# PRESELECTOR_REV_B.net
KiCad netlist of a schematic drawn in EAGLE
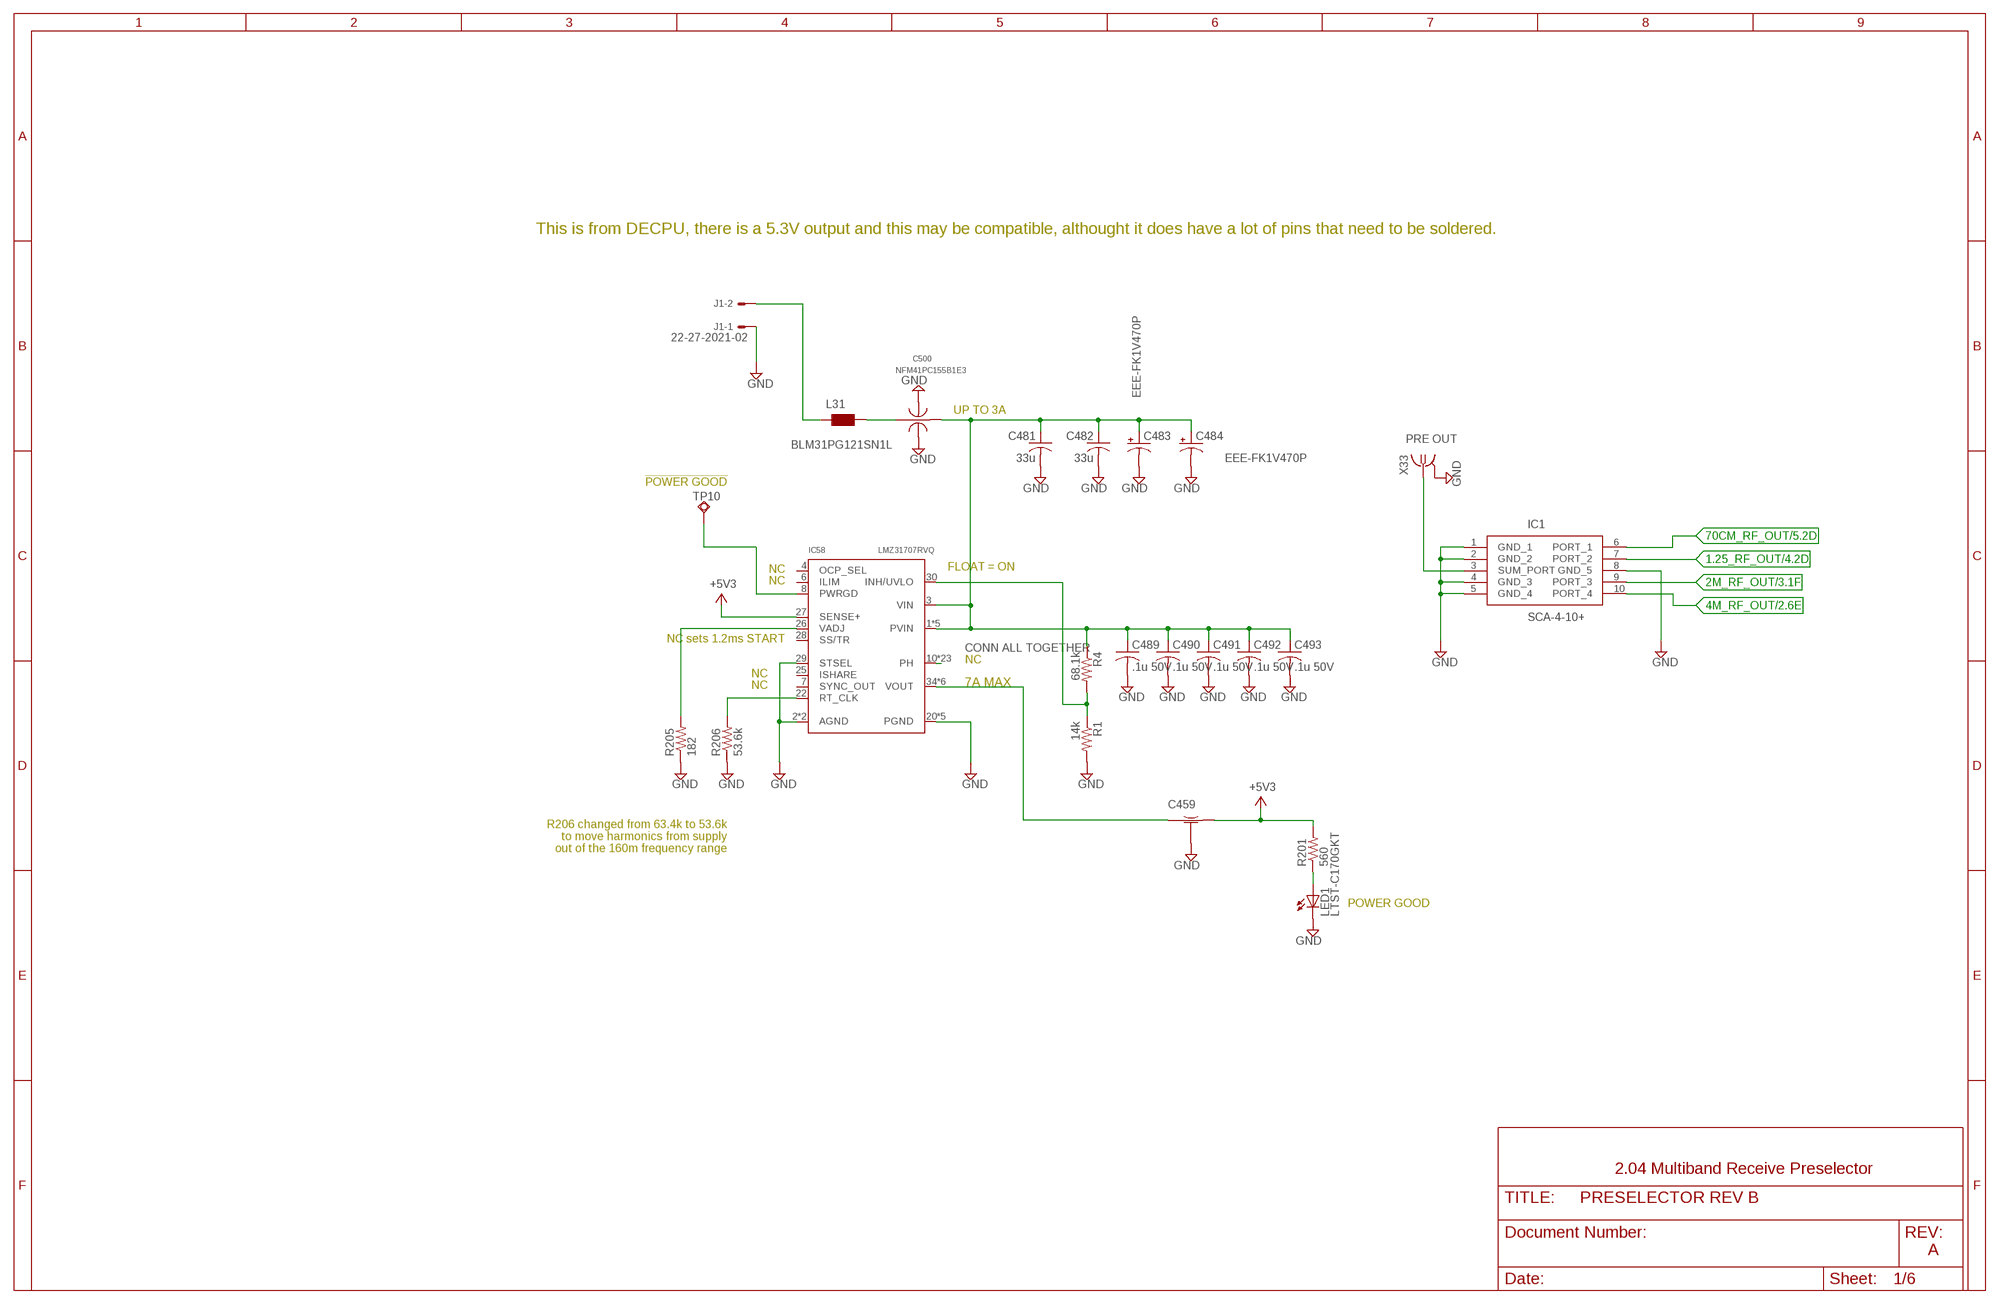
[diagram p0: schematic, sheet 1]
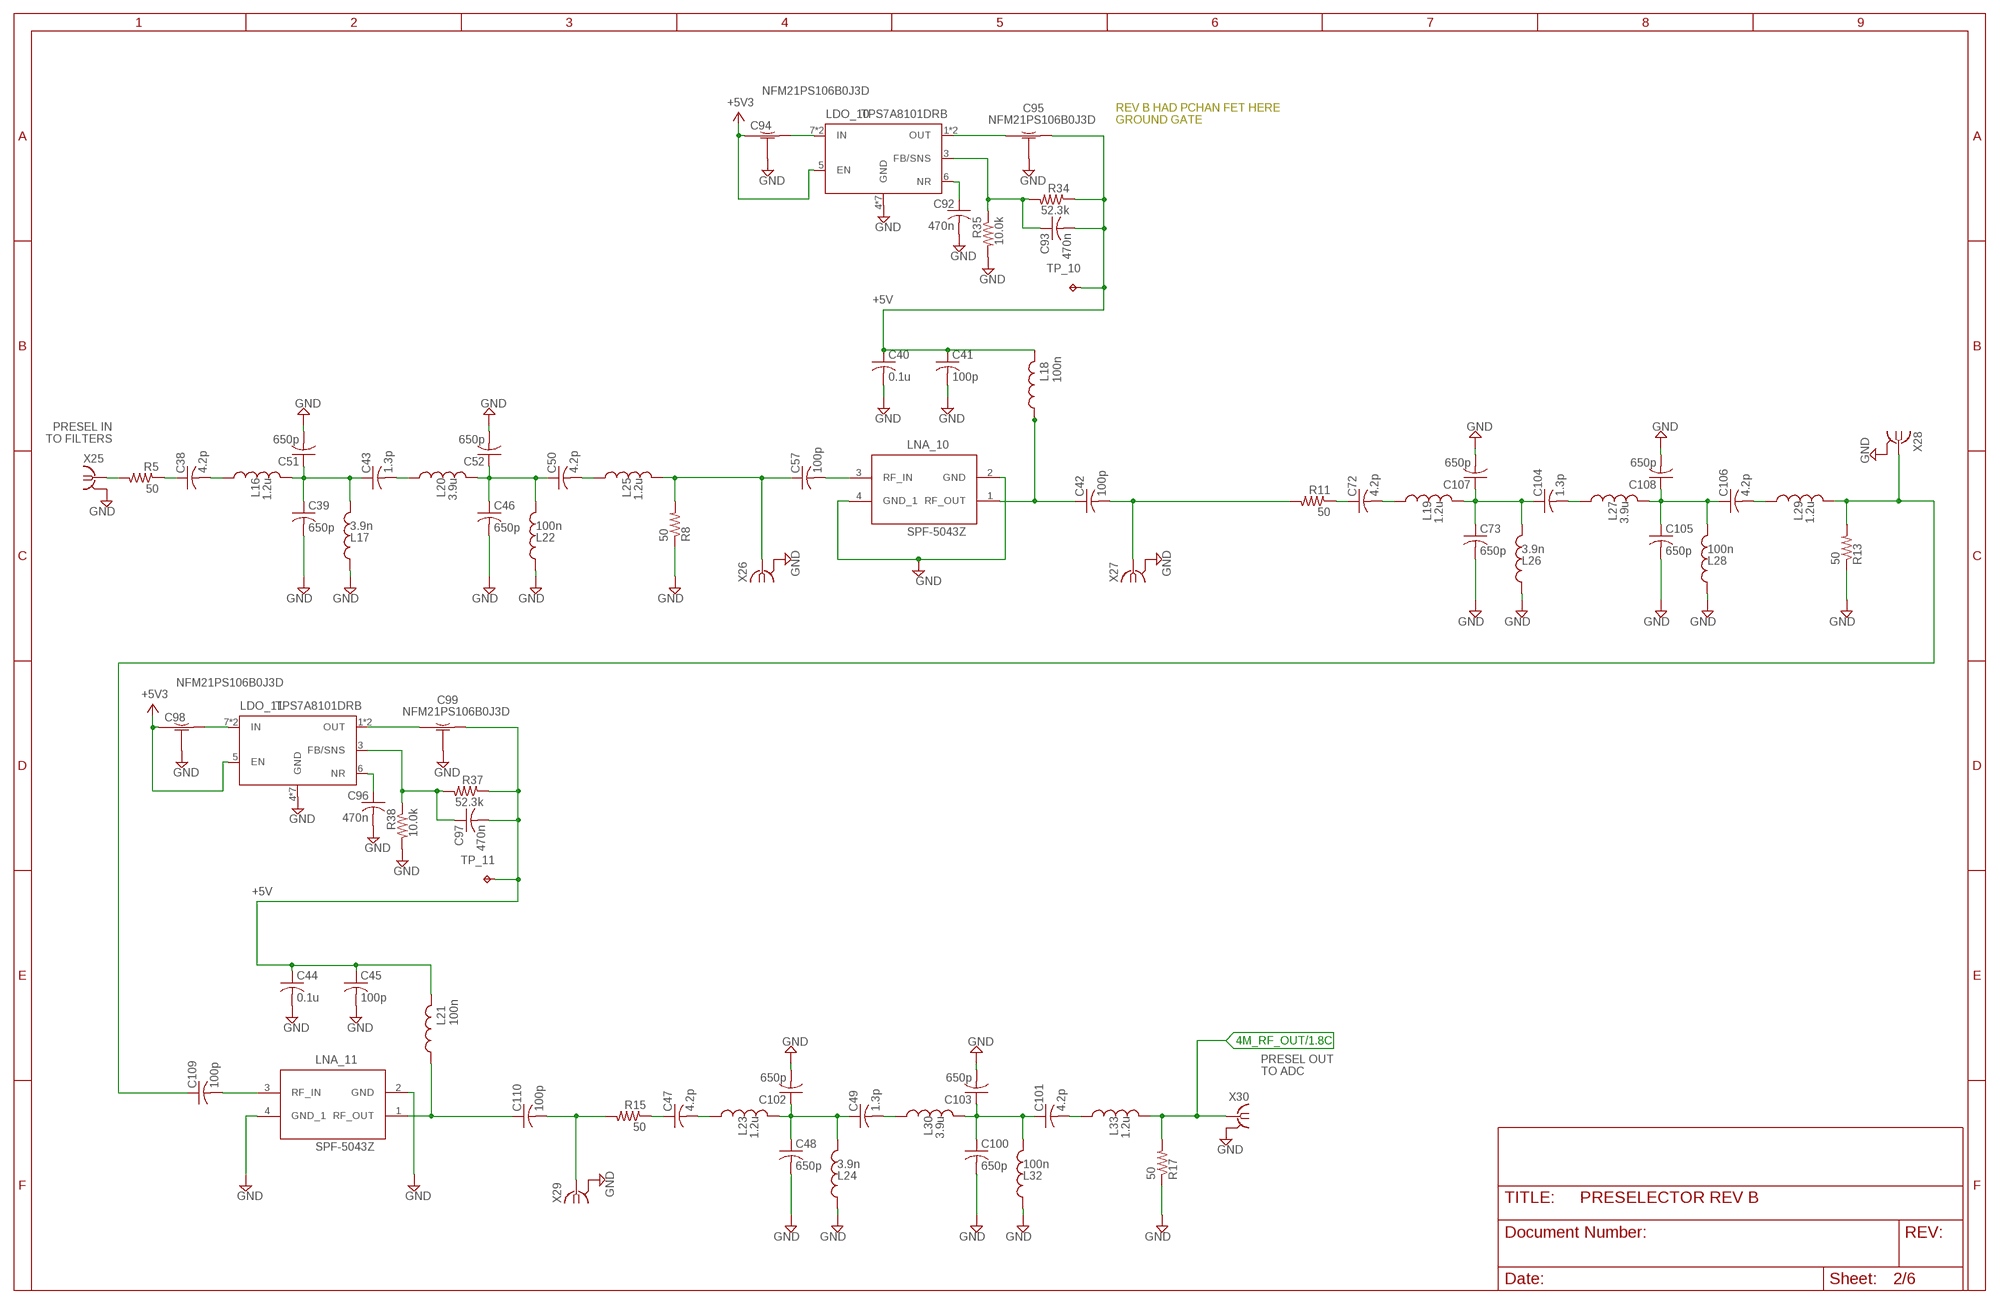
[diagram p1: schematic, sheet 2]
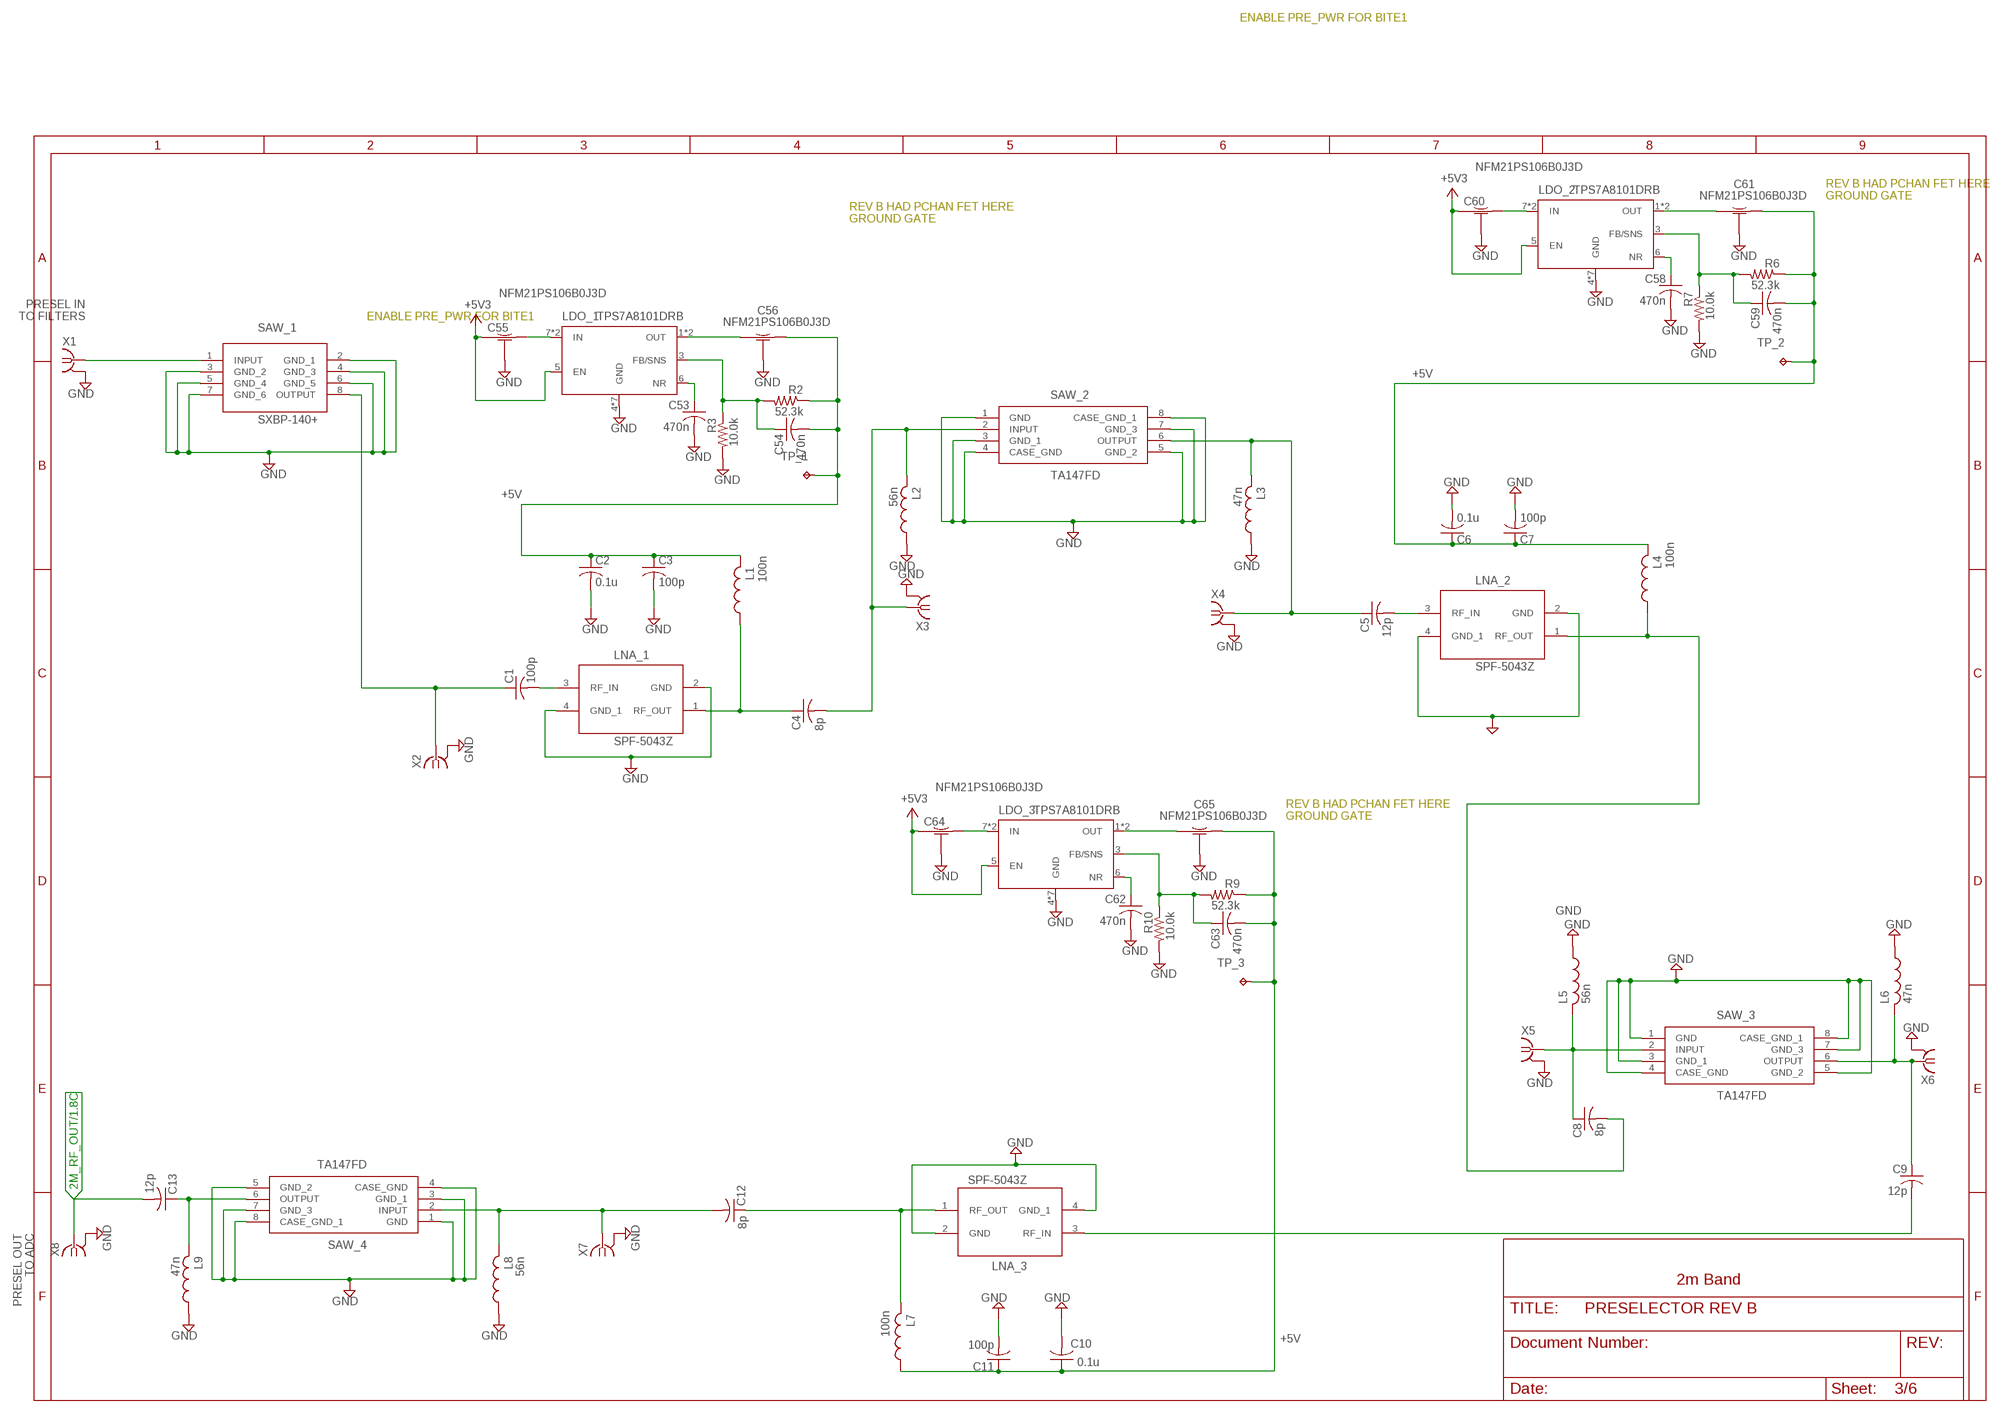
[diagram p2: schematic, sheet 3]
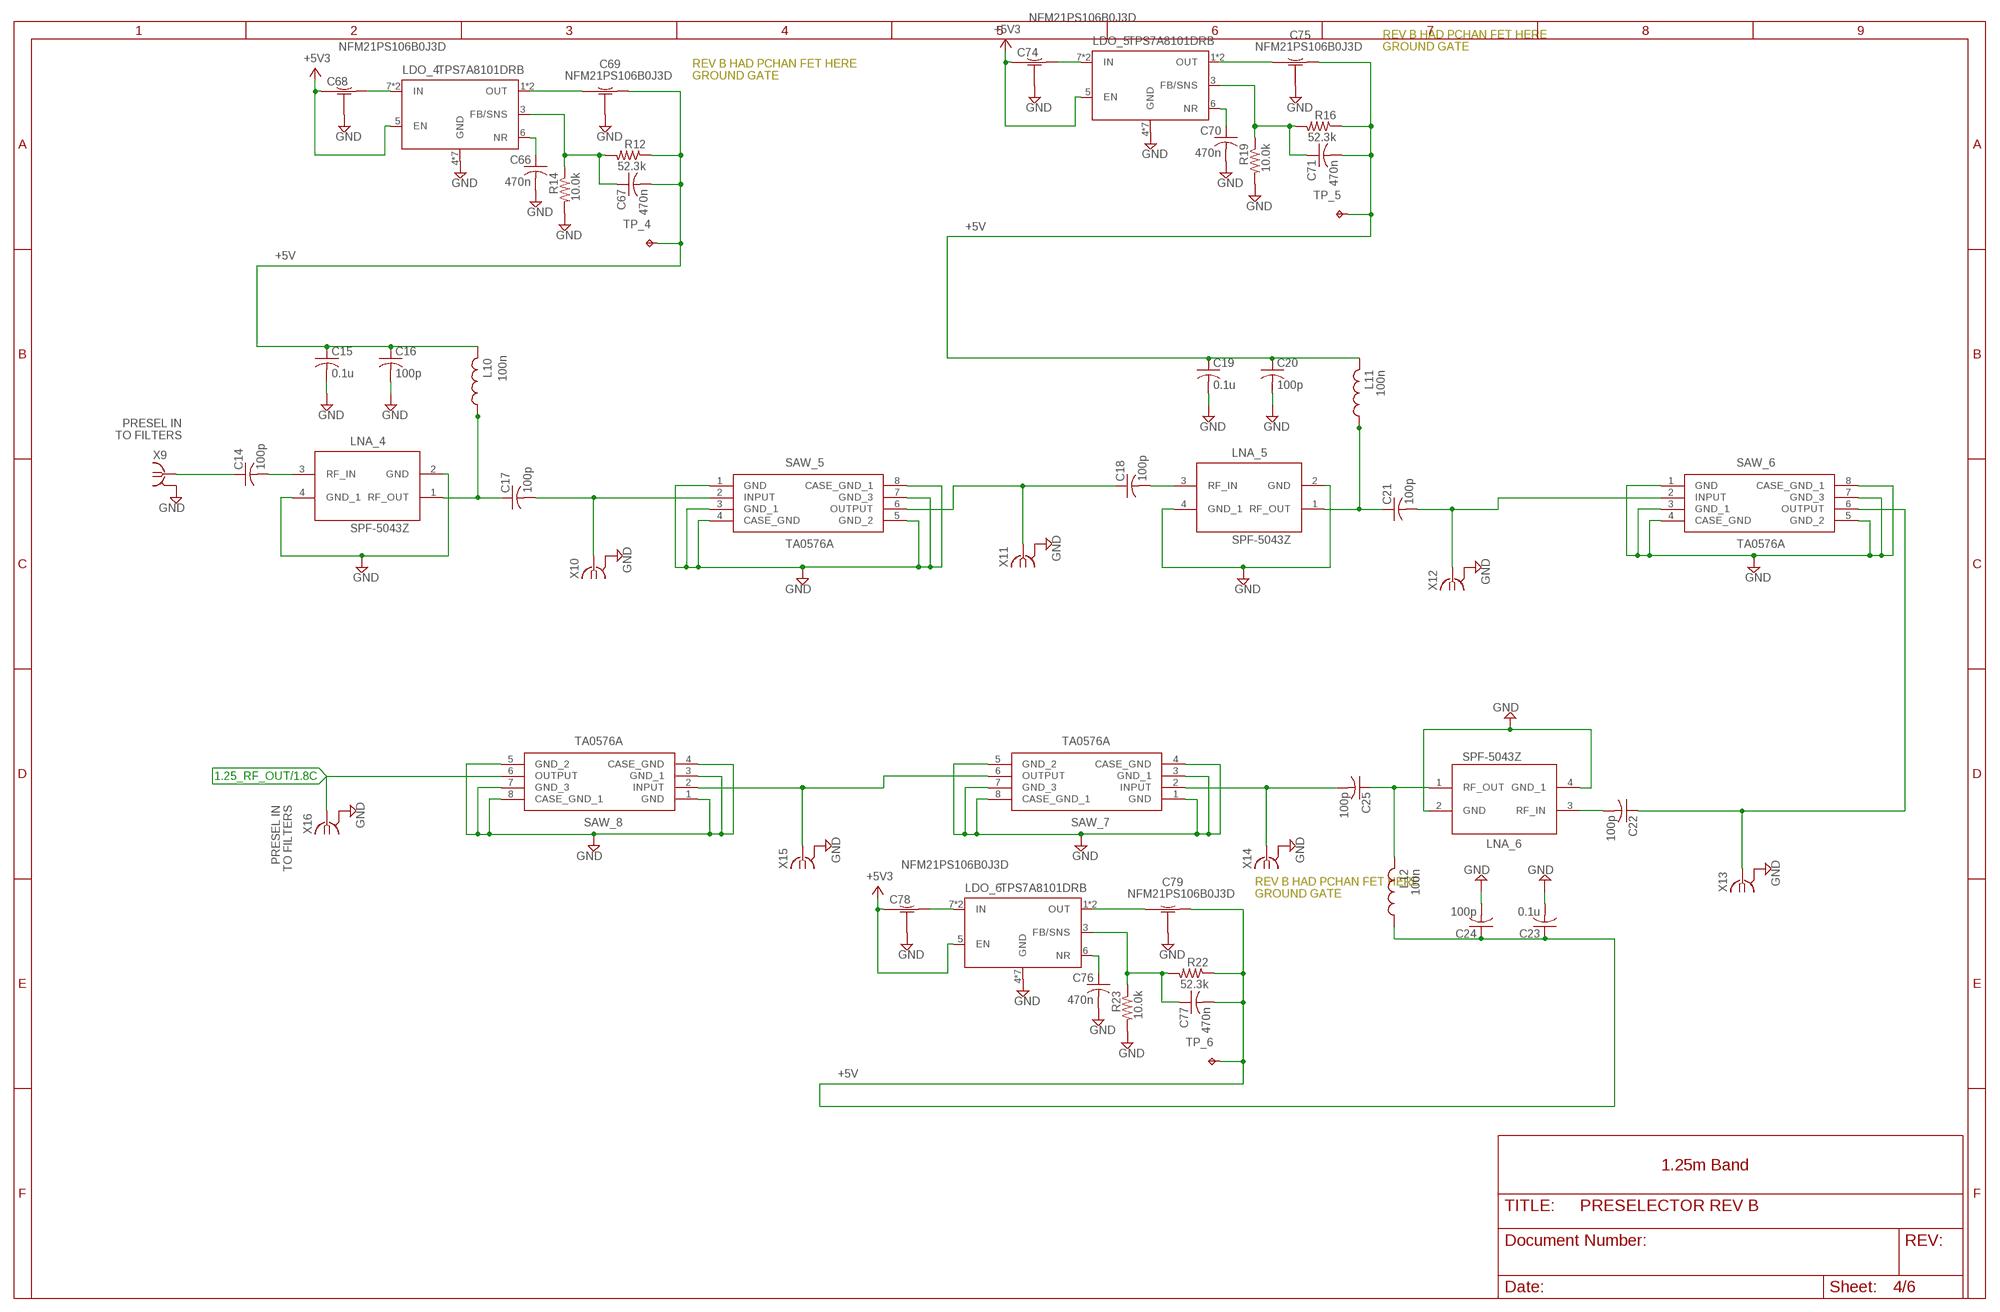
[diagram p3: schematic, sheet 4]
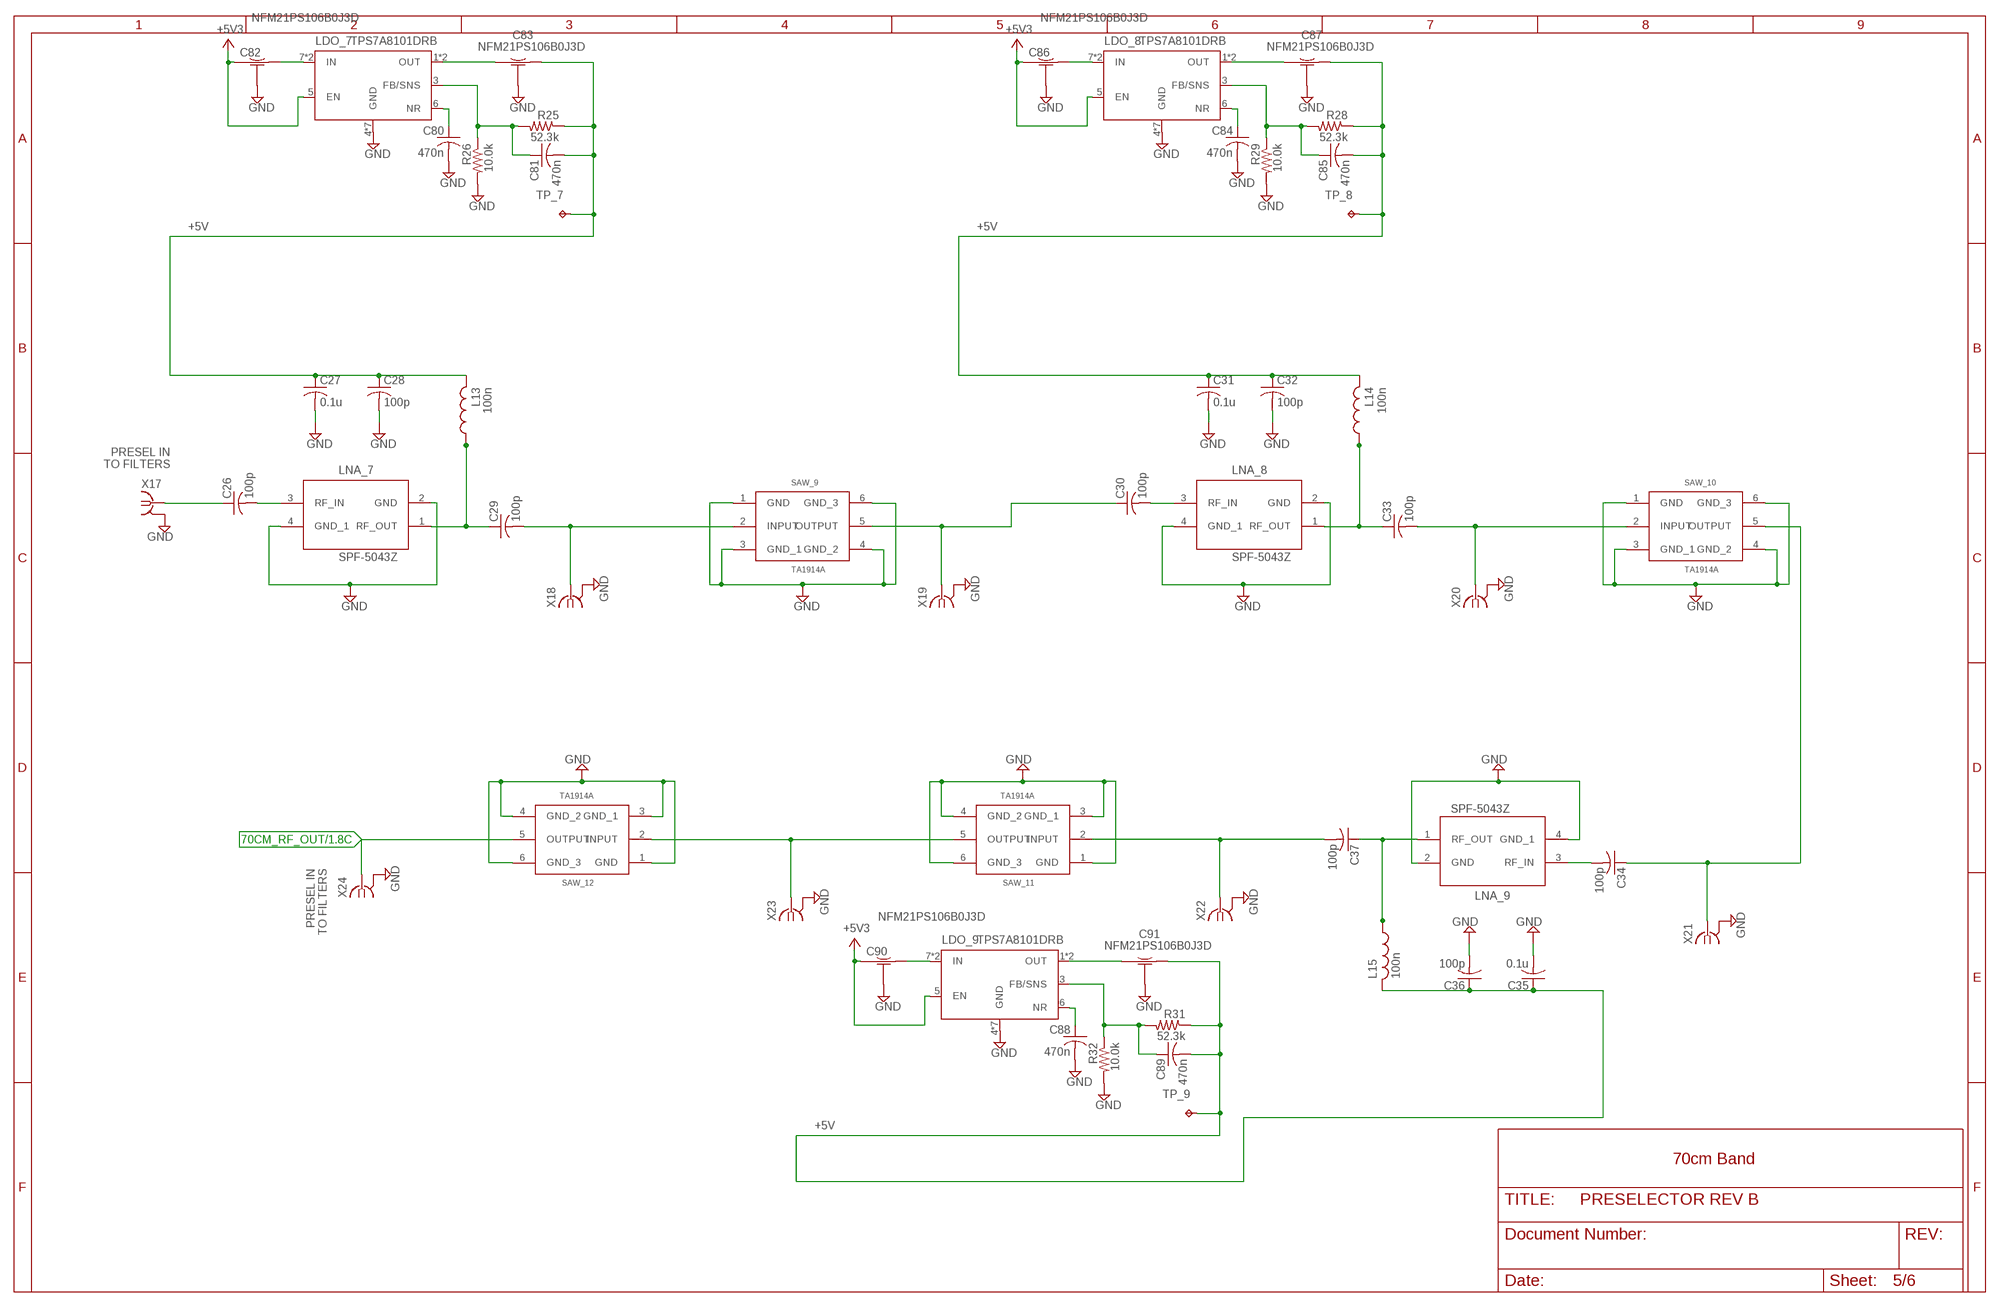
[diagram p4: schematic, sheet 5]
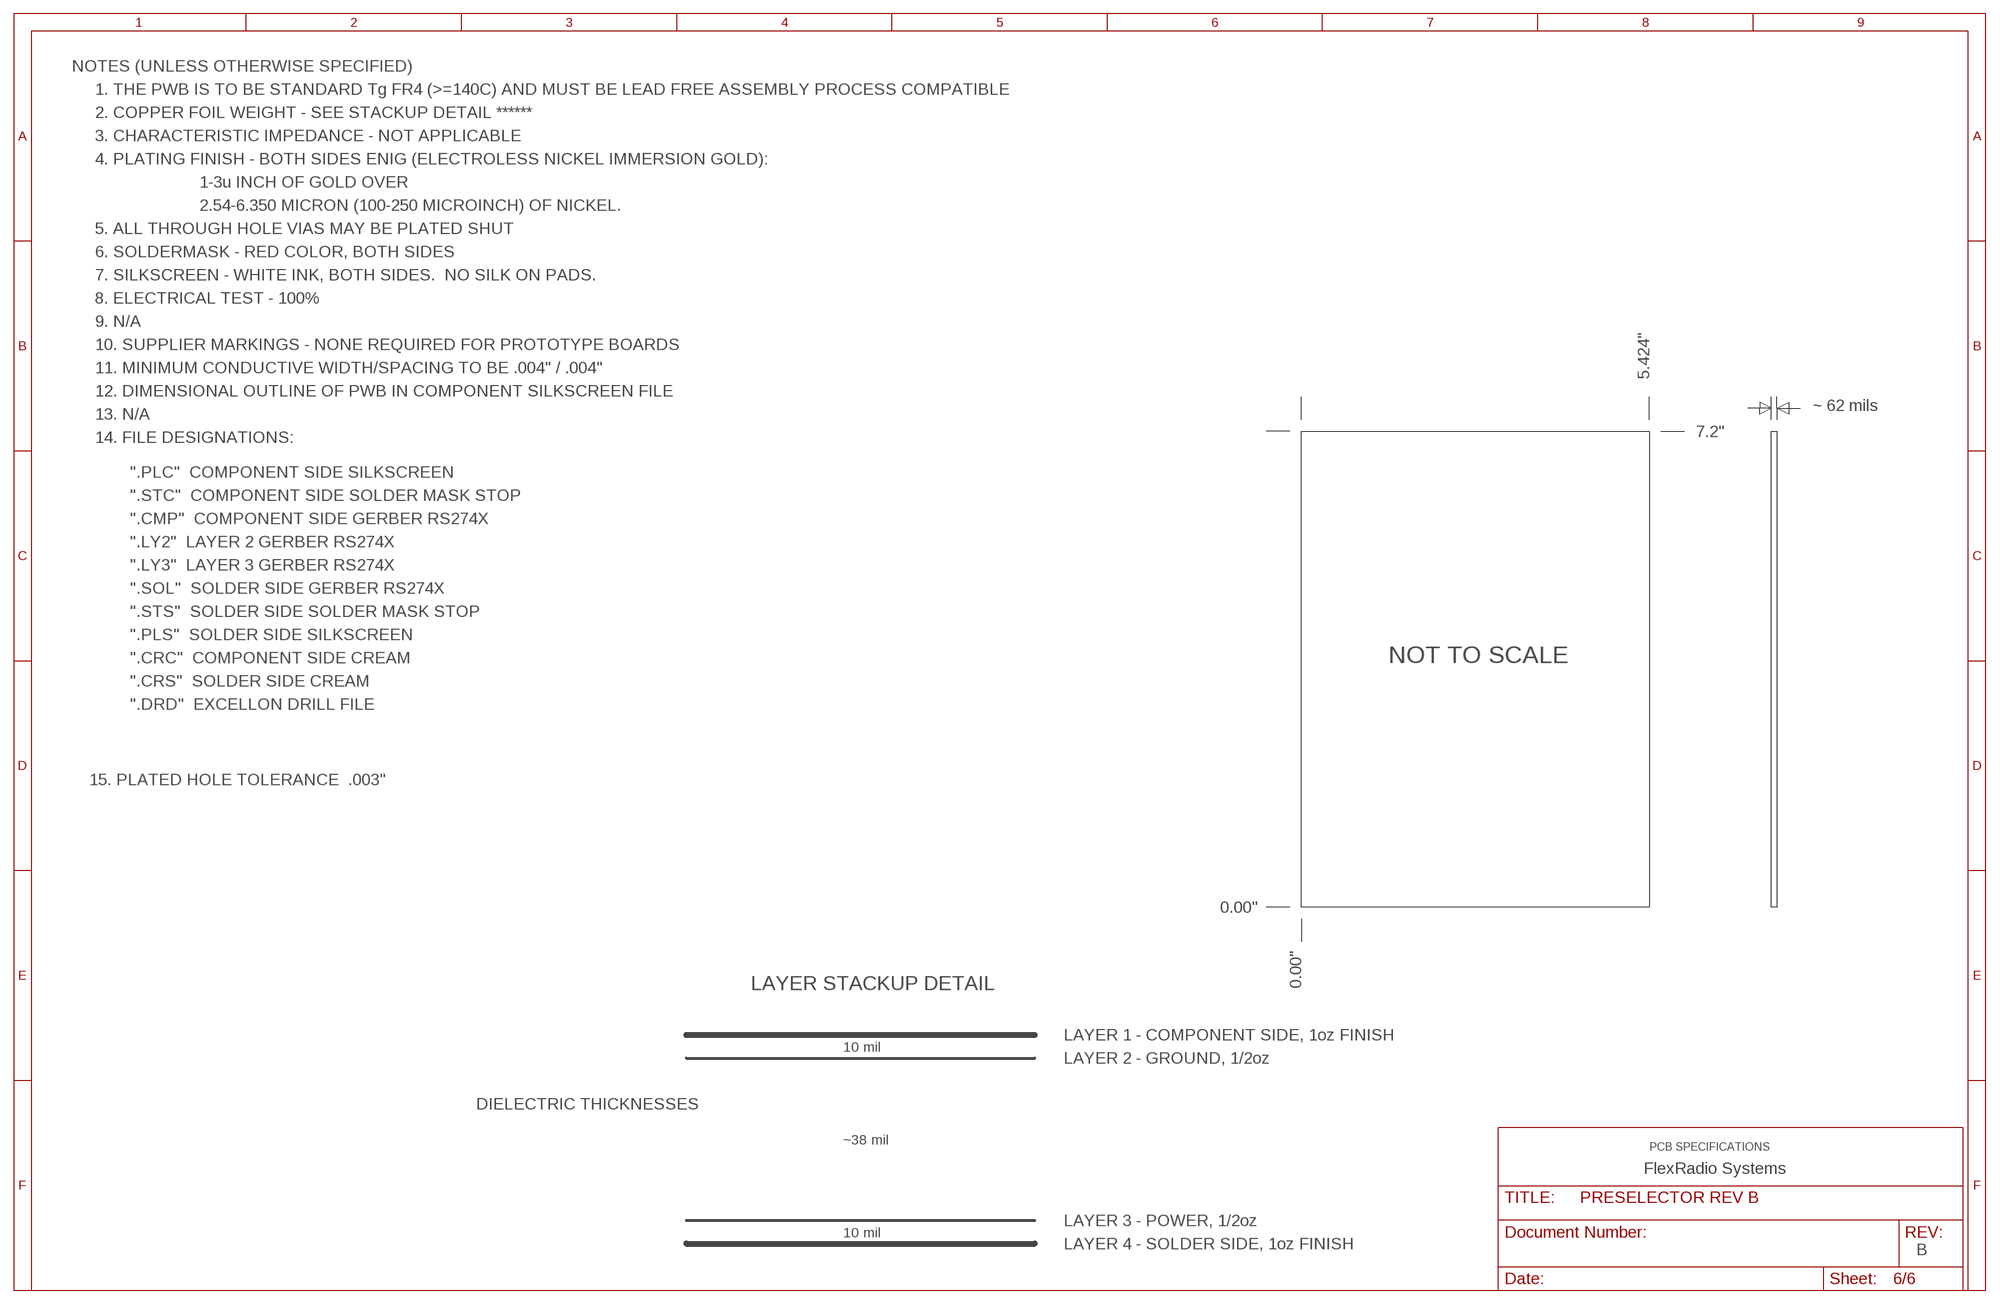
[diagram p5: schematic, sheet 6]

(export (version "E")
  (design (tool "Eeschema 10.0.6"))
  (components
    (comp (ref "C459")
      (value "NFM31PC276B0J3L")
      (footprint "eagle-import:NFM31PC276")
      (libsource (lib "eagle-import") (part "NFM31PC276B0J3L"))
    )
    (comp (ref "C481")
      (value "33u")
      (footprint "eagle-import:C1206K")
      (libsource (lib "eagle-import") (part "C-USC1206K"))
    )
    (comp (ref "C482")
      (value "33u")
      (footprint "eagle-import:C1206K")
      (libsource (lib "eagle-import") (part "C-USC1206K"))
    )
    (comp (ref "C483")
      (value "EEE-FK1V470P")
      (footprint "eagle-import:PANASONIC_D")
      (fields (field (name "PN") "EEE-FK1V470P"))
      (libsource (lib "eagle-import") (part "CPOL-USD"))
    )
    (comp (ref "C484")
      (value "EEE-FK1V470P")
      (footprint "eagle-import:PANASONIC_D")
      (fields (field (name "PN") "EEE-FK1V470P"))
      (libsource (lib "eagle-import") (part "CPOL-USD"))
    )
    (comp (ref "C489")
      (value ".1u 50V")
      (footprint "eagle-import:C0603K")
      (libsource (lib "eagle-import") (part "C-USC0603K"))
    )
    (comp (ref "C490")
      (value ".1u 50V")
      (footprint "eagle-import:C0603K")
      (libsource (lib "eagle-import") (part "C-USC0603K"))
    )
    (comp (ref "C491")
      (value ".1u 50V")
      (footprint "eagle-import:C0603K")
      (libsource (lib "eagle-import") (part "C-USC0603K"))
    )
    (comp (ref "C492")
      (value ".1u 50V")
      (footprint "eagle-import:C0603K")
      (libsource (lib "eagle-import") (part "C-USC0603K"))
    )
    (comp (ref "C493")
      (value ".1u 50V")
      (footprint "eagle-import:C0603K")
      (libsource (lib "eagle-import") (part "C-USC0603K"))
    )
    (comp (ref "C500")
      (value "NFM41PC155B1E3")
      (footprint "eagle-import:NFM1806")
      (libsource (lib "eagle-import") (part "NFM41PC155B1E3"))
    )
    (comp (ref "IC1")
      (value "SCA-4-10+")
      (footprint "eagle-import:SCA-4-10+")
      (libsource (lib "eagle-import") (part "SCA-4-10+"))
    )
    (comp (ref "IC58")
      (value "LMZ31707RVQ")
      (footprint "eagle-import:RVQ")
      (libsource (lib "eagle-import") (part "LMZ31707RVQ"))
    )
    (comp (ref "J1")
      (value "22-27-2021-02")
      (footprint "eagle-import:6410-02")
      (libsource (lib "eagle-import") (part "22-?-0227-2021"))
    )
    (comp (ref "L31")
      (value "BLM31PG121SN1L")
      (footprint "eagle-import:1206")
      (libsource (lib "eagle-import") (part "WE-CBF_1206"))
    )
    (comp (ref "LED1")
      (value "LTST-C170GKT")
      (footprint "eagle-import:CHIPLED_0805")
      (libsource (lib "eagle-import") (part "LEDCHIPLED_0805"))
    )
    (comp (ref "R1")
      (value "14k")
      (footprint "eagle-import:R0603")
      (libsource (lib "eagle-import") (part "R-US_R0603"))
    )
    (comp (ref "R4")
      (value "68.1k")
      (footprint "eagle-import:R0603")
      (libsource (lib "eagle-import") (part "R-US_R0603"))
    )
    (comp (ref "R201")
      (value "560")
      (footprint "eagle-import:R0603")
      (libsource (lib "eagle-import") (part "R-US_R0603"))
    )
    (comp (ref "R205")
      (value "182")
      (footprint "eagle-import:R0603")
      (libsource (lib "eagle-import") (part "R-US_R0603"))
    )
    (comp (ref "R206")
      (value "53.6k")
      (footprint "eagle-import:R0603")
      (libsource (lib "eagle-import") (part "R-US_R0603"))
    )
    (comp (ref "TP10")
      (value "TPSQB1,27")
      (footprint "eagle-import:B1,27")
      (libsource (lib "eagle-import") (part "TPSQB1,27"))
    )
    (comp (ref "X33")
      (value "0733660061")
      (footprint "eagle-import:BU-SMA-V")
      (libsource (lib "eagle-import") (part "BU-SMA-V"))
    )
    (comp (ref "C26")
      (value "100p")
      (footprint "eagle-import:C0603K")
      (libsource (lib "eagle-import") (part "C-USC0603K"))
    )
    (comp (ref "C27")
      (value "0.1u")
      (footprint "eagle-import:C0603K")
      (libsource (lib "eagle-import") (part "C-USC0603K"))
    )
    (comp (ref "C28")
      (value "100p")
      (footprint "eagle-import:C0603K")
      (libsource (lib "eagle-import") (part "C-USC0603K"))
    )
    (comp (ref "C29")
      (value "100p")
      (footprint "eagle-import:C0603K")
      (libsource (lib "eagle-import") (part "C-USC0603K"))
    )
    (comp (ref "C30")
      (value "100p")
      (footprint "eagle-import:C0603K")
      (libsource (lib "eagle-import") (part "C-USC0603K"))
    )
    (comp (ref "C31")
      (value "0.1u")
      (footprint "eagle-import:C0603K")
      (libsource (lib "eagle-import") (part "C-USC0603K"))
    )
    (comp (ref "C32")
      (value "100p")
      (footprint "eagle-import:C0603K")
      (libsource (lib "eagle-import") (part "C-USC0603K"))
    )
    (comp (ref "C33")
      (value "100p")
      (footprint "eagle-import:C0603K")
      (libsource (lib "eagle-import") (part "C-USC0603K"))
    )
    (comp (ref "C34")
      (value "100p")
      (footprint "eagle-import:C0603K")
      (libsource (lib "eagle-import") (part "C-USC0603K"))
    )
    (comp (ref "C35")
      (value "0.1u")
      (footprint "eagle-import:C0603K")
      (libsource (lib "eagle-import") (part "C-USC0603K"))
    )
    (comp (ref "C36")
      (value "100p")
      (footprint "eagle-import:C0603K")
      (libsource (lib "eagle-import") (part "C-USC0603K"))
    )
    (comp (ref "C37")
      (value "100p")
      (footprint "eagle-import:C0603K")
      (libsource (lib "eagle-import") (part "C-USC0603K"))
    )
    (comp (ref "C80")
      (value "470n")
      (footprint "eagle-import:C0603K")
      (libsource (lib "eagle-import") (part "C-USC0603K"))
    )
    (comp (ref "C81")
      (value "470n")
      (footprint "eagle-import:C0603K")
      (libsource (lib "eagle-import") (part "C-USC0603K"))
    )
    (comp (ref "C82")
      (value "NFM21PS106B0J3D")
      (footprint "eagle-import:NFM21PS")
      (libsource (lib "eagle-import") (part "NFM21PS"))
    )
    (comp (ref "C83")
      (value "NFM21PS106B0J3D")
      (footprint "eagle-import:NFM21PS")
      (libsource (lib "eagle-import") (part "NFM21PS"))
    )
    (comp (ref "C84")
      (value "470n")
      (footprint "eagle-import:C0603K")
      (libsource (lib "eagle-import") (part "C-USC0603K"))
    )
    (comp (ref "C85")
      (value "470n")
      (footprint "eagle-import:C0603K")
      (libsource (lib "eagle-import") (part "C-USC0603K"))
    )
    (comp (ref "C86")
      (value "NFM21PS106B0J3D")
      (footprint "eagle-import:NFM21PS")
      (libsource (lib "eagle-import") (part "NFM21PS"))
    )
    (comp (ref "C87")
      (value "NFM21PS106B0J3D")
      (footprint "eagle-import:NFM21PS")
      (libsource (lib "eagle-import") (part "NFM21PS"))
    )
    (comp (ref "C88")
      (value "470n")
      (footprint "eagle-import:C0603K")
      (libsource (lib "eagle-import") (part "C-USC0603K"))
    )
    (comp (ref "C89")
      (value "470n")
      (footprint "eagle-import:C0603K")
      (libsource (lib "eagle-import") (part "C-USC0603K"))
    )
    (comp (ref "C90")
      (value "NFM21PS106B0J3D")
      (footprint "eagle-import:NFM21PS")
      (libsource (lib "eagle-import") (part "NFM21PS"))
    )
    (comp (ref "C91")
      (value "NFM21PS106B0J3D")
      (footprint "eagle-import:NFM21PS")
      (libsource (lib "eagle-import") (part "NFM21PS"))
    )
    (comp (ref "L13")
      (value "100n")
      (footprint "eagle-import:C1206")
      (libsource (lib "eagle-import") (part "L-US1206"))
    )
    (comp (ref "L14")
      (value "100n")
      (footprint "eagle-import:C1206")
      (libsource (lib "eagle-import") (part "L-US1206"))
    )
    (comp (ref "L15")
      (value "100n")
      (footprint "eagle-import:C1206")
      (libsource (lib "eagle-import") (part "L-US1206"))
    )
    (comp (ref "LDO_7")
      (value "TPS7A8101DRB")
      (footprint "eagle-import:DRB")
      (libsource (lib "eagle-import") (part "TPS7A8101DRB"))
    )
    (comp (ref "LDO_8")
      (value "TPS7A8101DRB")
      (footprint "eagle-import:DRB")
      (libsource (lib "eagle-import") (part "TPS7A8101DRB"))
    )
    (comp (ref "LDO_9")
      (value "TPS7A8101DRB")
      (footprint "eagle-import:DRB")
      (libsource (lib "eagle-import") (part "TPS7A8101DRB"))
    )
    (comp (ref "LNA_7")
      (value "SPF-5043Z")
      (footprint "eagle-import:SPF-5043Z")
      (libsource (lib "eagle-import") (part "SPF-5043Z"))
    )
    (comp (ref "LNA_8")
      (value "SPF-5043Z")
      (footprint "eagle-import:SPF-5043Z")
      (libsource (lib "eagle-import") (part "SPF-5043Z"))
    )
    (comp (ref "LNA_9")
      (value "SPF-5043Z")
      (footprint "eagle-import:SPF-5043Z")
      (libsource (lib "eagle-import") (part "SPF-5043Z"))
    )
    (comp (ref "R25")
      (value "52.3k")
      (footprint "eagle-import:R0603")
      (libsource (lib "eagle-import") (part "R-US_R0603"))
    )
    (comp (ref "R26")
      (value "10.0k")
      (footprint "eagle-import:R0603")
      (libsource (lib "eagle-import") (part "R-US_R0603"))
    )
    (comp (ref "R28")
      (value "52.3k")
      (footprint "eagle-import:R0603")
      (libsource (lib "eagle-import") (part "R-US_R0603"))
    )
    (comp (ref "R29")
      (value "10.0k")
      (footprint "eagle-import:R0603")
      (libsource (lib "eagle-import") (part "R-US_R0603"))
    )
    (comp (ref "R31")
      (value "52.3k")
      (footprint "eagle-import:R0603")
      (libsource (lib "eagle-import") (part "R-US_R0603"))
    )
    (comp (ref "R32")
      (value "10.0k")
      (footprint "eagle-import:R0603")
      (libsource (lib "eagle-import") (part "R-US_R0603"))
    )
    (comp (ref "SAW_9")
      (value "TA1914A")
      (footprint "eagle-import:TA1914A")
      (libsource (lib "eagle-import") (part "TA1914A"))
    )
    (comp (ref "SAW_10")
      (value "TA1914A")
      (footprint "eagle-import:TA1914A")
      (libsource (lib "eagle-import") (part "TA1914A"))
    )
    (comp (ref "SAW_11")
      (value "TA1914A")
      (footprint "eagle-import:TA1914A")
      (libsource (lib "eagle-import") (part "TA1914A"))
    )
    (comp (ref "SAW_12")
      (value "TA1914A")
      (footprint "eagle-import:TA1914A")
      (libsource (lib "eagle-import") (part "TA1914A"))
    )
    (comp (ref "TP_7")
      (value "TPTP20SQ")
      (footprint "eagle-import:TP20SQ")
      (libsource (lib "eagle-import") (part "TPTP20SQ"))
    )
    (comp (ref "TP_8")
      (value "TPTP20SQ")
      (footprint "eagle-import:TP20SQ")
      (libsource (lib "eagle-import") (part "TPTP20SQ"))
    )
    (comp (ref "TP_9")
      (value "TPTP20SQ")
      (footprint "eagle-import:TP20SQ")
      (libsource (lib "eagle-import") (part "TPTP20SQ"))
    )
    (comp (ref "X17")
      (value "0733660061")
      (footprint "eagle-import:BU-SMA-V")
      (libsource (lib "eagle-import") (part "BU-SMA-V"))
    )
    (comp (ref "X18")
      (value "0733660061")
      (footprint "eagle-import:BU-SMA-V")
      (libsource (lib "eagle-import") (part "BU-SMA-V"))
    )
    (comp (ref "X19")
      (value "0733660061")
      (footprint "eagle-import:BU-SMA-V")
      (libsource (lib "eagle-import") (part "BU-SMA-V"))
    )
    (comp (ref "X20")
      (value "0733660061")
      (footprint "eagle-import:BU-SMA-V")
      (libsource (lib "eagle-import") (part "BU-SMA-V"))
    )
    (comp (ref "X21")
      (value "0733660061")
      (footprint "eagle-import:BU-SMA-V")
      (libsource (lib "eagle-import") (part "BU-SMA-V"))
    )
    (comp (ref "X22")
      (value "0733660061")
      (footprint "eagle-import:BU-SMA-V")
      (libsource (lib "eagle-import") (part "BU-SMA-V"))
    )
    (comp (ref "X23")
      (value "0733660061")
      (footprint "eagle-import:BU-SMA-V")
      (libsource (lib "eagle-import") (part "BU-SMA-V"))
    )
    (comp (ref "X24")
      (value "0733660061")
      (footprint "eagle-import:BU-SMA-V")
      (libsource (lib "eagle-import") (part "BU-SMA-V"))
    )
    (comp (ref "C1")
      (value "100p")
      (footprint "eagle-import:C0603K")
      (libsource (lib "eagle-import") (part "C-USC0603K"))
    )
    (comp (ref "C2")
      (value "0.1u")
      (footprint "eagle-import:C0603K")
      (libsource (lib "eagle-import") (part "C-USC0603K"))
    )
    (comp (ref "C3")
      (value "100p")
      (footprint "eagle-import:C0603K")
      (libsource (lib "eagle-import") (part "C-USC0603K"))
    )
    (comp (ref "C4")
      (value "8p")
      (footprint "eagle-import:C0603K")
      (libsource (lib "eagle-import") (part "C-USC0603K"))
    )
    (comp (ref "C5")
      (value "12p")
      (footprint "eagle-import:C0603K")
      (libsource (lib "eagle-import") (part "C-USC0603K"))
    )
    (comp (ref "C6")
      (value "0.1u")
      (footprint "eagle-import:C0603K")
      (libsource (lib "eagle-import") (part "C-USC0603K"))
    )
    (comp (ref "C7")
      (value "100p")
      (footprint "eagle-import:C0603K")
      (libsource (lib "eagle-import") (part "C-USC0603K"))
    )
    (comp (ref "C8")
      (value "8p")
      (footprint "eagle-import:C0603K")
      (libsource (lib "eagle-import") (part "C-USC0603K"))
    )
    (comp (ref "C9")
      (value "12p")
      (footprint "eagle-import:C0603K")
      (libsource (lib "eagle-import") (part "C-USC0603K"))
    )
    (comp (ref "C10")
      (value "0.1u")
      (footprint "eagle-import:C0603K")
      (libsource (lib "eagle-import") (part "C-USC0603K"))
    )
    (comp (ref "C11")
      (value "100p")
      (footprint "eagle-import:C0603K")
      (libsource (lib "eagle-import") (part "C-USC0603K"))
    )
    (comp (ref "C12")
      (value "8p")
      (footprint "eagle-import:C0603K")
      (libsource (lib "eagle-import") (part "C-USC0603K"))
    )
    (comp (ref "C13")
      (value "12p")
      (footprint "eagle-import:C0603K")
      (libsource (lib "eagle-import") (part "C-USC0603K"))
    )
    (comp (ref "C53")
      (value "470n")
      (footprint "eagle-import:C0603K")
      (libsource (lib "eagle-import") (part "C-USC0603K"))
    )
    (comp (ref "C54")
      (value "470n")
      (footprint "eagle-import:C0603K")
      (libsource (lib "eagle-import") (part "C-USC0603K"))
    )
    (comp (ref "C55")
      (value "NFM21PS106B0J3D")
      (footprint "eagle-import:NFM21PS")
      (libsource (lib "eagle-import") (part "NFM21PS"))
    )
    (comp (ref "C56")
      (value "NFM21PS106B0J3D")
      (footprint "eagle-import:NFM21PS")
      (libsource (lib "eagle-import") (part "NFM21PS"))
    )
    (comp (ref "C58")
      (value "470n")
      (footprint "eagle-import:C0603K")
      (libsource (lib "eagle-import") (part "C-USC0603K"))
    )
    (comp (ref "C59")
      (value "470n")
      (footprint "eagle-import:C0603K")
      (libsource (lib "eagle-import") (part "C-USC0603K"))
    )
    (comp (ref "C60")
      (value "NFM21PS106B0J3D")
      (footprint "eagle-import:NFM21PS")
      (libsource (lib "eagle-import") (part "NFM21PS"))
    )
    (comp (ref "C61")
      (value "NFM21PS106B0J3D")
      (footprint "eagle-import:NFM21PS")
      (libsource (lib "eagle-import") (part "NFM21PS"))
    )
    (comp (ref "C62")
      (value "470n")
      (footprint "eagle-import:C0603K")
      (libsource (lib "eagle-import") (part "C-USC0603K"))
    )
    (comp (ref "C63")
      (value "470n")
      (footprint "eagle-import:C0603K")
      (libsource (lib "eagle-import") (part "C-USC0603K"))
    )
    (comp (ref "C64")
      (value "NFM21PS106B0J3D")
      (footprint "eagle-import:NFM21PS")
      (libsource (lib "eagle-import") (part "NFM21PS"))
    )
    (comp (ref "C65")
      (value "NFM21PS106B0J3D")
      (footprint "eagle-import:NFM21PS")
      (libsource (lib "eagle-import") (part "NFM21PS"))
    )
    (comp (ref "L1")
      (value "100n")
      (footprint "eagle-import:C1206")
      (libsource (lib "eagle-import") (part "L-US1206"))
    )
    (comp (ref "L2")
      (value "56n")
      (footprint "eagle-import:C1206")
      (libsource (lib "eagle-import") (part "L-US1206"))
    )
    (comp (ref "L3")
      (value "47n")
      (footprint "eagle-import:C1206")
      (libsource (lib "eagle-import") (part "L-US1206"))
    )
    (comp (ref "L4")
      (value "100n")
      (footprint "eagle-import:C1206")
      (libsource (lib "eagle-import") (part "L-US1206"))
    )
    (comp (ref "L5")
      (value "56n")
      (footprint "eagle-import:C1206")
      (libsource (lib "eagle-import") (part "L-US1206"))
    )
    (comp (ref "L6")
      (value "47n")
      (footprint "eagle-import:C1206")
      (libsource (lib "eagle-import") (part "L-US1206"))
    )
    (comp (ref "L7")
      (value "100n")
      (footprint "eagle-import:C1206")
      (libsource (lib "eagle-import") (part "L-US1206"))
    )
    (comp (ref "L8")
      (value "56n")
      (footprint "eagle-import:C1206")
      (libsource (lib "eagle-import") (part "L-US1206"))
    )
    (comp (ref "L9")
      (value "47n")
      (footprint "eagle-import:C1206")
      (libsource (lib "eagle-import") (part "L-US1206"))
    )
    (comp (ref "LDO_1")
      (value "TPS7A8101DRB")
      (footprint "eagle-import:DRB")
      (libsource (lib "eagle-import") (part "TPS7A8101DRB"))
    )
    (comp (ref "LDO_2")
      (value "TPS7A8101DRB")
      (footprint "eagle-import:DRB")
      (libsource (lib "eagle-import") (part "TPS7A8101DRB"))
    )
    (comp (ref "LDO_3")
      (value "TPS7A8101DRB")
      (footprint "eagle-import:DRB")
      (libsource (lib "eagle-import") (part "TPS7A8101DRB"))
    )
    (comp (ref "LNA_1")
      (value "SPF-5043Z")
      (footprint "eagle-import:SPF-5043Z")
      (libsource (lib "eagle-import") (part "SPF-5043Z"))
    )
    (comp (ref "LNA_2")
      (value "SPF-5043Z")
      (footprint "eagle-import:SPF-5043Z")
      (libsource (lib "eagle-import") (part "SPF-5043Z"))
    )
    (comp (ref "LNA_3")
      (value "SPF-5043Z")
      (footprint "eagle-import:SPF-5043Z")
      (libsource (lib "eagle-import") (part "SPF-5043Z"))
    )
    (comp (ref "R2")
      (value "52.3k")
      (footprint "eagle-import:R0603")
      (libsource (lib "eagle-import") (part "R-US_R0603"))
    )
    (comp (ref "R3")
      (value "10.0k")
      (footprint "eagle-import:R0603")
      (libsource (lib "eagle-import") (part "R-US_R0603"))
    )
    (comp (ref "R6")
      (value "52.3k")
      (footprint "eagle-import:R0603")
      (libsource (lib "eagle-import") (part "R-US_R0603"))
    )
    (comp (ref "R7")
      (value "10.0k")
      (footprint "eagle-import:R0603")
      (libsource (lib "eagle-import") (part "R-US_R0603"))
    )
    (comp (ref "R9")
      (value "52.3k")
      (footprint "eagle-import:R0603")
      (libsource (lib "eagle-import") (part "R-US_R0603"))
    )
    (comp (ref "R10")
      (value "10.0k")
      (footprint "eagle-import:R0603")
      (libsource (lib "eagle-import") (part "R-US_R0603"))
    )
    (comp (ref "SAW_1")
      (value "SXBP-140+")
      (footprint "eagle-import:SXBP-140+")
      (libsource (lib "eagle-import") (part "SXBP-140+"))
    )
    (comp (ref "SAW_2")
      (value "TA147FD")
      (footprint "eagle-import:TA147FD")
      (libsource (lib "eagle-import") (part "TA147FD"))
    )
    (comp (ref "SAW_3")
      (value "TA147FD")
      (footprint "eagle-import:TA147FD")
      (libsource (lib "eagle-import") (part "TA147FD"))
    )
    (comp (ref "SAW_4")
      (value "TA147FD")
      (footprint "eagle-import:TA147FD")
      (libsource (lib "eagle-import") (part "TA147FD"))
    )
    (comp (ref "TP_1")
      (value "TPTP20SQ")
      (footprint "eagle-import:TP20SQ")
      (libsource (lib "eagle-import") (part "TPTP20SQ"))
    )
    (comp (ref "TP_2")
      (value "TPTP20SQ")
      (footprint "eagle-import:TP20SQ")
      (libsource (lib "eagle-import") (part "TPTP20SQ"))
    )
    (comp (ref "TP_3")
      (value "TPTP20SQ")
      (footprint "eagle-import:TP20SQ")
      (libsource (lib "eagle-import") (part "TPTP20SQ"))
    )
    (comp (ref "X1")
      (value "0733660061")
      (footprint "eagle-import:BU-SMA-V")
      (libsource (lib "eagle-import") (part "BU-SMA-V"))
    )
    (comp (ref "X2")
      (value "0733660061")
      (footprint "eagle-import:BU-SMA-V")
      (libsource (lib "eagle-import") (part "BU-SMA-V"))
    )
    (comp (ref "X3")
      (value "0733660061")
      (footprint "eagle-import:BU-SMA-V")
      (libsource (lib "eagle-import") (part "BU-SMA-V"))
    )
    (comp (ref "X4")
      (value "0733660061")
      (footprint "eagle-import:BU-SMA-V")
      (libsource (lib "eagle-import") (part "BU-SMA-V"))
    )
    (comp (ref "X5")
      (value "0733660061")
      (footprint "eagle-import:BU-SMA-V")
      (libsource (lib "eagle-import") (part "BU-SMA-V"))
    )
    (comp (ref "X6")
      (value "0733660061")
      (footprint "eagle-import:BU-SMA-V")
      (libsource (lib "eagle-import") (part "BU-SMA-V"))
    )
    (comp (ref "X7")
      (value "0733660061")
      (footprint "eagle-import:BU-SMA-V")
      (libsource (lib "eagle-import") (part "BU-SMA-V"))
    )
    (comp (ref "X8")
      (value "0733660061")
      (footprint "eagle-import:BU-SMA-V")
      (libsource (lib "eagle-import") (part "BU-SMA-V"))
    )
    (comp (ref "C14")
      (value "100p")
      (footprint "eagle-import:C0603K")
      (libsource (lib "eagle-import") (part "C-USC0603K"))
    )
    (comp (ref "C15")
      (value "0.1u")
      (footprint "eagle-import:C0603K")
      (libsource (lib "eagle-import") (part "C-USC0603K"))
    )
    (comp (ref "C16")
      (value "100p")
      (footprint "eagle-import:C0603K")
      (libsource (lib "eagle-import") (part "C-USC0603K"))
    )
    (comp (ref "C17")
      (value "100p")
      (footprint "eagle-import:C0603K")
      (libsource (lib "eagle-import") (part "C-USC0603K"))
    )
    (comp (ref "C18")
      (value "100p")
      (footprint "eagle-import:C0603K")
      (libsource (lib "eagle-import") (part "C-USC0603K"))
    )
    (comp (ref "C19")
      (value "0.1u")
      (footprint "eagle-import:C0603K")
      (libsource (lib "eagle-import") (part "C-USC0603K"))
    )
    (comp (ref "C20")
      (value "100p")
      (footprint "eagle-import:C0603K")
      (libsource (lib "eagle-import") (part "C-USC0603K"))
    )
    (comp (ref "C21")
      (value "100p")
      (footprint "eagle-import:C0603K")
      (libsource (lib "eagle-import") (part "C-USC0603K"))
    )
    (comp (ref "C22")
      (value "100p")
      (footprint "eagle-import:C0603K")
      (libsource (lib "eagle-import") (part "C-USC0603K"))
    )
    (comp (ref "C23")
      (value "0.1u")
      (footprint "eagle-import:C0603K")
      (libsource (lib "eagle-import") (part "C-USC0603K"))
    )
    (comp (ref "C24")
      (value "100p")
      (footprint "eagle-import:C0603K")
      (libsource (lib "eagle-import") (part "C-USC0603K"))
    )
    (comp (ref "C25")
      (value "100p")
      (footprint "eagle-import:C0603K")
      (libsource (lib "eagle-import") (part "C-USC0603K"))
    )
    (comp (ref "C66")
      (value "470n")
      (footprint "eagle-import:C0603K")
      (libsource (lib "eagle-import") (part "C-USC0603K"))
    )
    (comp (ref "C67")
      (value "470n")
      (footprint "eagle-import:C0603K")
      (libsource (lib "eagle-import") (part "C-USC0603K"))
    )
    (comp (ref "C68")
      (value "NFM21PS106B0J3D")
      (footprint "eagle-import:NFM21PS")
      (libsource (lib "eagle-import") (part "NFM21PS"))
    )
    (comp (ref "C69")
      (value "NFM21PS106B0J3D")
      (footprint "eagle-import:NFM21PS")
      (libsource (lib "eagle-import") (part "NFM21PS"))
    )
    (comp (ref "C70")
      (value "470n")
      (footprint "eagle-import:C0603K")
      (libsource (lib "eagle-import") (part "C-USC0603K"))
    )
    (comp (ref "C71")
      (value "470n")
      (footprint "eagle-import:C0603K")
      (libsource (lib "eagle-import") (part "C-USC0603K"))
    )
    (comp (ref "C74")
      (value "NFM21PS106B0J3D")
      (footprint "eagle-import:NFM21PS")
      (libsource (lib "eagle-import") (part "NFM21PS"))
    )
    (comp (ref "C75")
      (value "NFM21PS106B0J3D")
      (footprint "eagle-import:NFM21PS")
      (libsource (lib "eagle-import") (part "NFM21PS"))
    )
    (comp (ref "C76")
      (value "470n")
      (footprint "eagle-import:C0603K")
      (libsource (lib "eagle-import") (part "C-USC0603K"))
    )
    (comp (ref "C77")
      (value "470n")
      (footprint "eagle-import:C0603K")
      (libsource (lib "eagle-import") (part "C-USC0603K"))
    )
    (comp (ref "C78")
      (value "NFM21PS106B0J3D")
      (footprint "eagle-import:NFM21PS")
      (libsource (lib "eagle-import") (part "NFM21PS"))
    )
    (comp (ref "C79")
      (value "NFM21PS106B0J3D")
      (footprint "eagle-import:NFM21PS")
      (libsource (lib "eagle-import") (part "NFM21PS"))
    )
    (comp (ref "L10")
      (value "100n")
      (footprint "eagle-import:C1206")
      (libsource (lib "eagle-import") (part "L-US1206"))
    )
    (comp (ref "L11")
      (value "100n")
      (footprint "eagle-import:C1206")
      (libsource (lib "eagle-import") (part "L-US1206"))
    )
    (comp (ref "L12")
      (value "100n")
      (footprint "eagle-import:C1206")
      (libsource (lib "eagle-import") (part "L-US1206"))
    )
    (comp (ref "LDO_4")
      (value "TPS7A8101DRB")
      (footprint "eagle-import:DRB")
      (libsource (lib "eagle-import") (part "TPS7A8101DRB"))
    )
    (comp (ref "LDO_5")
      (value "TPS7A8101DRB")
      (footprint "eagle-import:DRB")
      (libsource (lib "eagle-import") (part "TPS7A8101DRB"))
    )
    (comp (ref "LDO_6")
      (value "TPS7A8101DRB")
      (footprint "eagle-import:DRB")
      (libsource (lib "eagle-import") (part "TPS7A8101DRB"))
    )
    (comp (ref "LNA_4")
      (value "SPF-5043Z")
      (footprint "eagle-import:SPF-5043Z")
      (libsource (lib "eagle-import") (part "SPF-5043Z"))
    )
    (comp (ref "LNA_5")
      (value "SPF-5043Z")
      (footprint "eagle-import:SPF-5043Z")
      (libsource (lib "eagle-import") (part "SPF-5043Z"))
    )
    (comp (ref "LNA_6")
      (value "SPF-5043Z")
      (footprint "eagle-import:SPF-5043Z")
      (libsource (lib "eagle-import") (part "SPF-5043Z"))
    )
    (comp (ref "R12")
      (value "52.3k")
      (footprint "eagle-import:R0603")
      (libsource (lib "eagle-import") (part "R-US_R0603"))
    )
    (comp (ref "R14")
      (value "10.0k")
      (footprint "eagle-import:R0603")
      (libsource (lib "eagle-import") (part "R-US_R0603"))
    )
    (comp (ref "R16")
      (value "52.3k")
      (footprint "eagle-import:R0603")
      (libsource (lib "eagle-import") (part "R-US_R0603"))
    )
    (comp (ref "R19")
      (value "10.0k")
      (footprint "eagle-import:R0603")
      (libsource (lib "eagle-import") (part "R-US_R0603"))
    )
    (comp (ref "R22")
      (value "52.3k")
      (footprint "eagle-import:R0603")
      (libsource (lib "eagle-import") (part "R-US_R0603"))
    )
    (comp (ref "R23")
      (value "10.0k")
      (footprint "eagle-import:R0603")
      (libsource (lib "eagle-import") (part "R-US_R0603"))
    )
    (comp (ref "SAW_5")
      (value "TA0576A")
      (footprint "eagle-import:TA0576A")
      (libsource (lib "eagle-import") (part "TA0576A"))
    )
    (comp (ref "SAW_6")
      (value "TA0576A")
      (footprint "eagle-import:TA0576A")
      (libsource (lib "eagle-import") (part "TA0576A"))
    )
    (comp (ref "SAW_7")
      (value "TA0576A")
      (footprint "eagle-import:TA0576A")
      (libsource (lib "eagle-import") (part "TA0576A"))
    )
    (comp (ref "SAW_8")
      (value "TA0576A")
      (footprint "eagle-import:TA0576A")
      (libsource (lib "eagle-import") (part "TA0576A"))
    )
    (comp (ref "TP_4")
      (value "TPTP20SQ")
      (footprint "eagle-import:TP20SQ")
      (libsource (lib "eagle-import") (part "TPTP20SQ"))
    )
    (comp (ref "TP_5")
      (value "TPTP20SQ")
      (footprint "eagle-import:TP20SQ")
      (libsource (lib "eagle-import") (part "TPTP20SQ"))
    )
    (comp (ref "TP_6")
      (value "TPTP20SQ")
      (footprint "eagle-import:TP20SQ")
      (libsource (lib "eagle-import") (part "TPTP20SQ"))
    )
    (comp (ref "X9")
      (value "0733660061")
      (footprint "eagle-import:BU-SMA-V")
      (libsource (lib "eagle-import") (part "BU-SMA-V"))
    )
    (comp (ref "X10")
      (value "0733660061")
      (footprint "eagle-import:BU-SMA-V")
      (libsource (lib "eagle-import") (part "BU-SMA-V"))
    )
    (comp (ref "X11")
      (value "0733660061")
      (footprint "eagle-import:BU-SMA-V")
      (libsource (lib "eagle-import") (part "BU-SMA-V"))
    )
    (comp (ref "X12")
      (value "0733660061")
      (footprint "eagle-import:BU-SMA-V")
      (libsource (lib "eagle-import") (part "BU-SMA-V"))
    )
    (comp (ref "X13")
      (value "0733660061")
      (footprint "eagle-import:BU-SMA-V")
      (libsource (lib "eagle-import") (part "BU-SMA-V"))
    )
    (comp (ref "X14")
      (value "0733660061")
      (footprint "eagle-import:BU-SMA-V")
      (libsource (lib "eagle-import") (part "BU-SMA-V"))
    )
    (comp (ref "X15")
      (value "0733660061")
      (footprint "eagle-import:BU-SMA-V")
      (libsource (lib "eagle-import") (part "BU-SMA-V"))
    )
    (comp (ref "X16")
      (value "0733660061")
      (footprint "eagle-import:BU-SMA-V")
      (libsource (lib "eagle-import") (part "BU-SMA-V"))
    )
    (comp (ref "C38")
      (value "4.2p")
      (footprint "eagle-import:C0603K")
      (libsource (lib "eagle-import") (part "C-USC0603K"))
    )
    (comp (ref "C39")
      (value "650p")
      (footprint "eagle-import:C0603K")
      (libsource (lib "eagle-import") (part "C-USC0603K"))
    )
    (comp (ref "C40")
      (value "0.1u")
      (footprint "eagle-import:C0603K")
      (libsource (lib "eagle-import") (part "C-USC0603K"))
    )
    (comp (ref "C41")
      (value "100p")
      (footprint "eagle-import:C0603K")
      (libsource (lib "eagle-import") (part "C-USC0603K"))
    )
    (comp (ref "C42")
      (value "100p")
      (footprint "eagle-import:C0603K")
      (libsource (lib "eagle-import") (part "C-USC0603K"))
    )
    (comp (ref "C43")
      (value "1.3p")
      (footprint "eagle-import:C0603K")
      (libsource (lib "eagle-import") (part "C-USC0603K"))
    )
    (comp (ref "C44")
      (value "0.1u")
      (footprint "eagle-import:C0603K")
      (libsource (lib "eagle-import") (part "C-USC0603K"))
    )
    (comp (ref "C45")
      (value "100p")
      (footprint "eagle-import:C0603K")
      (libsource (lib "eagle-import") (part "C-USC0603K"))
    )
    (comp (ref "C46")
      (value "650p")
      (footprint "eagle-import:C0603K")
      (libsource (lib "eagle-import") (part "C-USC0603K"))
    )
    (comp (ref "C47")
      (value "4.2p")
      (footprint "eagle-import:C0603K")
      (libsource (lib "eagle-import") (part "C-USC0603K"))
    )
    (comp (ref "C48")
      (value "650p")
      (footprint "eagle-import:C0603K")
      (libsource (lib "eagle-import") (part "C-USC0603K"))
    )
    (comp (ref "C49")
      (value "1.3p")
      (footprint "eagle-import:C0603K")
      (libsource (lib "eagle-import") (part "C-USC0603K"))
    )
    (comp (ref "C50")
      (value "4.2p")
      (footprint "eagle-import:C0603K")
      (libsource (lib "eagle-import") (part "C-USC0603K"))
    )
    (comp (ref "C51")
      (value "650p")
      (footprint "eagle-import:C0603K")
      (libsource (lib "eagle-import") (part "C-USC0603K"))
    )
    (comp (ref "C52")
      (value "650p")
      (footprint "eagle-import:C0603K")
      (libsource (lib "eagle-import") (part "C-USC0603K"))
    )
    (comp (ref "C57")
      (value "100p")
      (footprint "eagle-import:C0603K")
      (libsource (lib "eagle-import") (part "C-USC0603K"))
    )
    (comp (ref "C72")
      (value "4.2p")
      (footprint "eagle-import:C0603K")
      (libsource (lib "eagle-import") (part "C-USC0603K"))
    )
    (comp (ref "C73")
      (value "650p")
      (footprint "eagle-import:C0603K")
      (libsource (lib "eagle-import") (part "C-USC0603K"))
    )
    (comp (ref "C92")
      (value "470n")
      (footprint "eagle-import:C0603K")
      (libsource (lib "eagle-import") (part "C-USC0603K"))
    )
    (comp (ref "C93")
      (value "470n")
      (footprint "eagle-import:C0603K")
      (libsource (lib "eagle-import") (part "C-USC0603K"))
    )
    (comp (ref "C94")
      (value "NFM21PS106B0J3D")
      (footprint "eagle-import:NFM21PS")
      (libsource (lib "eagle-import") (part "NFM21PS"))
    )
    (comp (ref "C95")
      (value "NFM21PS106B0J3D")
      (footprint "eagle-import:NFM21PS")
      (libsource (lib "eagle-import") (part "NFM21PS"))
    )
    (comp (ref "C96")
      (value "470n")
      (footprint "eagle-import:C0603K")
      (libsource (lib "eagle-import") (part "C-USC0603K"))
    )
    (comp (ref "C97")
      (value "470n")
      (footprint "eagle-import:C0603K")
      (libsource (lib "eagle-import") (part "C-USC0603K"))
    )
    (comp (ref "C98")
      (value "NFM21PS106B0J3D")
      (footprint "eagle-import:NFM21PS")
      (libsource (lib "eagle-import") (part "NFM21PS"))
    )
    (comp (ref "C99")
      (value "NFM21PS106B0J3D")
      (footprint "eagle-import:NFM21PS")
      (libsource (lib "eagle-import") (part "NFM21PS"))
    )
    (comp (ref "C100")
      (value "650p")
      (footprint "eagle-import:C0603K")
      (libsource (lib "eagle-import") (part "C-USC0603K"))
    )
    (comp (ref "C101")
      (value "4.2p")
      (footprint "eagle-import:C0603K")
      (libsource (lib "eagle-import") (part "C-USC0603K"))
    )
    (comp (ref "C102")
      (value "650p")
      (footprint "eagle-import:C0603K")
      (libsource (lib "eagle-import") (part "C-USC0603K"))
    )
    (comp (ref "C103")
      (value "650p")
      (footprint "eagle-import:C0603K")
      (libsource (lib "eagle-import") (part "C-USC0603K"))
    )
    (comp (ref "C104")
      (value "1.3p")
      (footprint "eagle-import:C0603K")
      (libsource (lib "eagle-import") (part "C-USC0603K"))
    )
    (comp (ref "C105")
      (value "650p")
      (footprint "eagle-import:C0603K")
      (libsource (lib "eagle-import") (part "C-USC0603K"))
    )
    (comp (ref "C106")
      (value "4.2p")
      (footprint "eagle-import:C0603K")
      (libsource (lib "eagle-import") (part "C-USC0603K"))
    )
    (comp (ref "C107")
      (value "650p")
      (footprint "eagle-import:C0603K")
      (libsource (lib "eagle-import") (part "C-USC0603K"))
    )
    (comp (ref "C108")
      (value "650p")
      (footprint "eagle-import:C0603K")
      (libsource (lib "eagle-import") (part "C-USC0603K"))
    )
    (comp (ref "C109")
      (value "100p")
      (footprint "eagle-import:C0603K")
      (libsource (lib "eagle-import") (part "C-USC0603K"))
    )
    (comp (ref "C110")
      (value "100p")
      (footprint "eagle-import:C0603K")
      (libsource (lib "eagle-import") (part "C-USC0603K"))
    )
    (comp (ref "L16")
      (value "1.2u")
      (footprint "eagle-import:C0603K")
      (libsource (lib "eagle-import") (part "L-US0603"))
    )
    (comp (ref "L17")
      (value "3.9n")
      (footprint "eagle-import:C0603K")
      (libsource (lib "eagle-import") (part "L-US0603"))
    )
    (comp (ref "L18")
      (value "100n")
      (footprint "eagle-import:C1206")
      (libsource (lib "eagle-import") (part "L-US1206"))
    )
    (comp (ref "L19")
      (value "1.2u")
      (footprint "eagle-import:C0603K")
      (libsource (lib "eagle-import") (part "L-US0603"))
    )
    (comp (ref "L20")
      (value "3.9u")
      (footprint "eagle-import:C0603K")
      (libsource (lib "eagle-import") (part "L-US0603"))
    )
    (comp (ref "L21")
      (value "100n")
      (footprint "eagle-import:C1206")
      (libsource (lib "eagle-import") (part "L-US1206"))
    )
    (comp (ref "L22")
      (value "100n")
      (footprint "eagle-import:C0603K")
      (libsource (lib "eagle-import") (part "L-US0603"))
    )
    (comp (ref "L23")
      (value "1.2u")
      (footprint "eagle-import:C0603K")
      (libsource (lib "eagle-import") (part "L-US0603"))
    )
    (comp (ref "L24")
      (value "3.9n")
      (footprint "eagle-import:C0603K")
      (libsource (lib "eagle-import") (part "L-US0603"))
    )
    (comp (ref "L25")
      (value "1.2u")
      (footprint "eagle-import:C0603K")
      (libsource (lib "eagle-import") (part "L-US0603"))
    )
    (comp (ref "L26")
      (value "3.9n")
      (footprint "eagle-import:C0603K")
      (libsource (lib "eagle-import") (part "L-US0603"))
    )
    (comp (ref "L27")
      (value "3.9u")
      (footprint "eagle-import:C0603K")
      (libsource (lib "eagle-import") (part "L-US0603"))
    )
    (comp (ref "L28")
      (value "100n")
      (footprint "eagle-import:C0603K")
      (libsource (lib "eagle-import") (part "L-US0603"))
    )
    (comp (ref "L29")
      (value "1.2u")
      (footprint "eagle-import:C0603K")
      (libsource (lib "eagle-import") (part "L-US0603"))
    )
    (comp (ref "L30")
      (value "3.9u")
      (footprint "eagle-import:C0603K")
      (libsource (lib "eagle-import") (part "L-US0603"))
    )
    (comp (ref "L32")
      (value "100n")
      (footprint "eagle-import:C0603K")
      (libsource (lib "eagle-import") (part "L-US0603"))
    )
    (comp (ref "L33")
      (value "1.2u")
      (footprint "eagle-import:C0603K")
      (libsource (lib "eagle-import") (part "L-US0603"))
    )
    (comp (ref "LDO_10")
      (value "TPS7A8101DRB")
      (footprint "eagle-import:DRB")
      (libsource (lib "eagle-import") (part "TPS7A8101DRB"))
    )
    (comp (ref "LDO_11")
      (value "TPS7A8101DRB")
      (footprint "eagle-import:DRB")
      (libsource (lib "eagle-import") (part "TPS7A8101DRB"))
    )
    (comp (ref "LNA_10")
      (value "SPF-5043Z")
      (footprint "eagle-import:SPF-5043Z")
      (libsource (lib "eagle-import") (part "SPF-5043Z"))
    )
    (comp (ref "LNA_11")
      (value "SPF-5043Z")
      (footprint "eagle-import:SPF-5043Z")
      (libsource (lib "eagle-import") (part "SPF-5043Z"))
    )
    (comp (ref "R5")
      (value "50")
      (footprint "eagle-import:R0603")
      (libsource (lib "eagle-import") (part "R-US_R0603"))
    )
    (comp (ref "R8")
      (value "50")
      (footprint "eagle-import:R0603")
      (libsource (lib "eagle-import") (part "R-US_R0603"))
    )
    (comp (ref "R11")
      (value "50")
      (footprint "eagle-import:R0603")
      (libsource (lib "eagle-import") (part "R-US_R0603"))
    )
    (comp (ref "R13")
      (value "50")
      (footprint "eagle-import:R0603")
      (libsource (lib "eagle-import") (part "R-US_R0603"))
    )
    (comp (ref "R15")
      (value "50")
      (footprint "eagle-import:R0603")
      (libsource (lib "eagle-import") (part "R-US_R0603"))
    )
    (comp (ref "R17")
      (value "50")
      (footprint "eagle-import:R0603")
      (libsource (lib "eagle-import") (part "R-US_R0603"))
    )
    (comp (ref "R34")
      (value "52.3k")
      (footprint "eagle-import:R0603")
      (libsource (lib "eagle-import") (part "R-US_R0603"))
    )
    (comp (ref "R35")
      (value "10.0k")
      (footprint "eagle-import:R0603")
      (libsource (lib "eagle-import") (part "R-US_R0603"))
    )
    (comp (ref "R37")
      (value "52.3k")
      (footprint "eagle-import:R0603")
      (libsource (lib "eagle-import") (part "R-US_R0603"))
    )
    (comp (ref "R38")
      (value "10.0k")
      (footprint "eagle-import:R0603")
      (libsource (lib "eagle-import") (part "R-US_R0603"))
    )
    (comp (ref "TP_10")
      (value "TPTP20SQ")
      (footprint "eagle-import:TP20SQ")
      (libsource (lib "eagle-import") (part "TPTP20SQ"))
    )
    (comp (ref "TP_11")
      (value "TPTP20SQ")
      (footprint "eagle-import:TP20SQ")
      (libsource (lib "eagle-import") (part "TPTP20SQ"))
    )
    (comp (ref "X25")
      (value "0733660061")
      (footprint "eagle-import:BU-SMA-V")
      (libsource (lib "eagle-import") (part "BU-SMA-V"))
    )
    (comp (ref "X26")
      (value "0733660061")
      (footprint "eagle-import:BU-SMA-V")
      (libsource (lib "eagle-import") (part "BU-SMA-V"))
    )
    (comp (ref "X27")
      (value "0733660061")
      (footprint "eagle-import:BU-SMA-V")
      (libsource (lib "eagle-import") (part "BU-SMA-V"))
    )
    (comp (ref "X28")
      (value "0733660061")
      (footprint "eagle-import:BU-SMA-V")
      (libsource (lib "eagle-import") (part "BU-SMA-V"))
    )
    (comp (ref "X29")
      (value "0733660061")
      (footprint "eagle-import:BU-SMA-V")
      (libsource (lib "eagle-import") (part "BU-SMA-V"))
    )
    (comp (ref "X30")
      (value "0733660061")
      (footprint "eagle-import:BU-SMA-V")
      (libsource (lib "eagle-import") (part "BU-SMA-V"))
    )
  )
  (nets
    (net (code "1") (name "+5V3") (class "Default")
      (node (ref "C459") (pin "OUT") (pinfunction "OUT_OUT") (pintype "bidirectional"))
      (node (ref "C55") (pin "IN") (pinfunction "IN_IN") (pintype "bidirectional"))
      (node (ref "C60") (pin "IN") (pinfunction "IN_IN") (pintype "bidirectional"))
      (node (ref "C64") (pin "IN") (pinfunction "IN_IN") (pintype "bidirectional"))
      (node (ref "C68") (pin "IN") (pinfunction "IN_IN") (pintype "bidirectional"))
      (node (ref "C74") (pin "IN") (pinfunction "IN_IN") (pintype "bidirectional"))
      (node (ref "C78") (pin "IN") (pinfunction "IN_IN") (pintype "bidirectional"))
      (node (ref "C82") (pin "IN") (pinfunction "IN_IN") (pintype "bidirectional"))
      (node (ref "C86") (pin "IN") (pinfunction "IN_IN") (pintype "bidirectional"))
      (node (ref "C90") (pin "IN") (pinfunction "IN_IN") (pintype "bidirectional"))
      (node (ref "C94") (pin "IN") (pinfunction "IN_IN") (pintype "bidirectional"))
      (node (ref "C98") (pin "IN") (pinfunction "IN_IN") (pintype "bidirectional"))
      (node (ref "IC58") (pin "27") (pinfunction "SENSE+_27") (pintype "bidirectional"))
      (node (ref "LDO_1") (pin "5") (pinfunction "EN_5") (pintype "bidirectional"))
      (node (ref "LDO_10") (pin "5") (pinfunction "EN_5") (pintype "bidirectional"))
      (node (ref "LDO_11") (pin "5") (pinfunction "EN_5") (pintype "bidirectional"))
      (node (ref "LDO_2") (pin "5") (pinfunction "EN_5") (pintype "bidirectional"))
      (node (ref "LDO_3") (pin "5") (pinfunction "EN_5") (pintype "bidirectional"))
      (node (ref "LDO_4") (pin "5") (pinfunction "EN_5") (pintype "bidirectional"))
      (node (ref "LDO_5") (pin "5") (pinfunction "EN_5") (pintype "bidirectional"))
      (node (ref "LDO_6") (pin "5") (pinfunction "EN_5") (pintype "bidirectional"))
      (node (ref "LDO_7") (pin "5") (pinfunction "EN_5") (pintype "bidirectional"))
      (node (ref "LDO_8") (pin "5") (pinfunction "EN_5") (pintype "bidirectional"))
      (node (ref "LDO_9") (pin "5") (pinfunction "EN_5") (pintype "bidirectional"))
      (node (ref "R201") (pin "2") (pinfunction "2_2") (pintype "passive"))
    )
    (net (code "2") (name "1.25_RF_OUT") (class "Default")
      (node (ref "IC1") (pin "7") (pinfunction "PORT_2_7") (pintype "bidirectional"))
      (node (ref "SAW_8") (pin "6") (pinfunction "OUTPUT_6") (pintype "bidirectional"))
      (node (ref "X16") (pin "1") (pinfunction "1_1") (pintype "passive"))
    )
    (net (code "3") (name "2M_RF_OUT") (class "Default")
      (node (ref "C13") (pin "2") (pinfunction "2_2") (pintype "passive"))
      (node (ref "IC1") (pin "9") (pinfunction "PORT_3_9") (pintype "bidirectional"))
      (node (ref "X8") (pin "1") (pinfunction "1_1") (pintype "passive"))
    )
    (net (code "4") (name "4M_RF_OUT") (class "Default")
      (node (ref "IC1") (pin "10") (pinfunction "PORT_4_10") (pintype "bidirectional"))
      (node (ref "L33") (pin "2") (pinfunction "2_2") (pintype "passive"))
      (node (ref "R17") (pin "2") (pinfunction "2_2") (pintype "passive"))
      (node (ref "X30") (pin "1") (pinfunction "1_1") (pintype "passive"))
    )
    (net (code "5") (name "70CM_RF_OUT") (class "Default")
      (node (ref "IC1") (pin "6") (pinfunction "PORT_1_6") (pintype "bidirectional"))
      (node (ref "SAW_12") (pin "5") (pinfunction "OUTPUT_5") (pintype "bidirectional"))
      (node (ref "X24") (pin "1") (pinfunction "1_1") (pintype "passive"))
    )
    (net (code "6") (name "GND") (class "Default")
      (node (ref "C10") (pin "2") (pinfunction "2_2") (pintype "passive"))
      (node (ref "C100") (pin "2") (pinfunction "2_2") (pintype "passive"))
      (node (ref "C102") (pin "2") (pinfunction "2_2") (pintype "passive"))
      (node (ref "C103") (pin "2") (pinfunction "2_2") (pintype "passive"))
      (node (ref "C105") (pin "2") (pinfunction "2_2") (pintype "passive"))
      (node (ref "C107") (pin "2") (pinfunction "2_2") (pintype "passive"))
      (node (ref "C108") (pin "2") (pinfunction "2_2") (pintype "passive"))
      (node (ref "C11") (pin "2") (pinfunction "2_2") (pintype "passive"))
      (node (ref "C15") (pin "2") (pinfunction "2_2") (pintype "passive"))
      (node (ref "C16") (pin "2") (pinfunction "2_2") (pintype "passive"))
      (node (ref "C19") (pin "2") (pinfunction "2_2") (pintype "passive"))
      (node (ref "C2") (pin "2") (pinfunction "2_2") (pintype "passive"))
      (node (ref "C20") (pin "2") (pinfunction "2_2") (pintype "passive"))
      (node (ref "C23") (pin "2") (pinfunction "2_2") (pintype "passive"))
      (node (ref "C24") (pin "2") (pinfunction "2_2") (pintype "passive"))
      (node (ref "C27") (pin "2") (pinfunction "2_2") (pintype "passive"))
      (node (ref "C28") (pin "2") (pinfunction "2_2") (pintype "passive"))
      (node (ref "C3") (pin "2") (pinfunction "2_2") (pintype "passive"))
      (node (ref "C31") (pin "2") (pinfunction "2_2") (pintype "passive"))
      (node (ref "C32") (pin "2") (pinfunction "2_2") (pintype "passive"))
      (node (ref "C35") (pin "2") (pinfunction "2_2") (pintype "passive"))
      (node (ref "C36") (pin "2") (pinfunction "2_2") (pintype "passive"))
      (node (ref "C39") (pin "2") (pinfunction "2_2") (pintype "passive"))
      (node (ref "C40") (pin "2") (pinfunction "2_2") (pintype "passive"))
      (node (ref "C41") (pin "2") (pinfunction "2_2") (pintype "passive"))
      (node (ref "C44") (pin "2") (pinfunction "2_2") (pintype "passive"))
      (node (ref "C45") (pin "2") (pinfunction "2_2") (pintype "passive"))
      (node (ref "C459") (pin "GND1") (pinfunction "GND_GND1") (pintype "bidirectional"))
      (node (ref "C459") (pin "GND2") (pinfunction "GND_GND2") (pintype "bidirectional"))
      (node (ref "C459") (pin "GND3") (pinfunction "GND_GND3") (pintype "bidirectional"))
      (node (ref "C459") (pin "GND4") (pinfunction "GND_GND4") (pintype "bidirectional"))
      (node (ref "C459") (pin "GND5") (pinfunction "GND_GND5") (pintype "bidirectional"))
      (node (ref "C46") (pin "2") (pinfunction "2_2") (pintype "passive"))
      (node (ref "C48") (pin "2") (pinfunction "2_2") (pintype "passive"))
      (node (ref "C481") (pin "2") (pinfunction "2_2") (pintype "passive"))
      (node (ref "C482") (pin "2") (pinfunction "2_2") (pintype "passive"))
      (node (ref "C483") (pin "-") (pinfunction "-_-") (pintype "passive"))
      (node (ref "C484") (pin "-") (pinfunction "-_-") (pintype "passive"))
      (node (ref "C489") (pin "2") (pinfunction "2_2") (pintype "passive"))
      (node (ref "C490") (pin "2") (pinfunction "2_2") (pintype "passive"))
      (node (ref "C491") (pin "2") (pinfunction "2_2") (pintype "passive"))
      (node (ref "C492") (pin "2") (pinfunction "2_2") (pintype "passive"))
      (node (ref "C493") (pin "2") (pinfunction "2_2") (pintype "passive"))
      (node (ref "C500") (pin "GND@1") (pinfunction "GND_GND@1") (pintype "power_in"))
      (node (ref "C500") (pin "GND@2") (pinfunction "GND_GND@2") (pintype "power_in"))
      (node (ref "C51") (pin "2") (pinfunction "2_2") (pintype "passive"))
      (node (ref "C52") (pin "2") (pinfunction "2_2") (pintype "passive"))
      (node (ref "C53") (pin "2") (pinfunction "2_2") (pintype "passive"))
      (node (ref "C55") (pin "GND1") (pinfunction "GND_GND1") (pintype "bidirectional"))
      (node (ref "C55") (pin "GND2") (pinfunction "GND_GND2") (pintype "bidirectional"))
      (node (ref "C55") (pin "GND3") (pinfunction "GND_GND3") (pintype "bidirectional"))
      (node (ref "C55") (pin "GND4") (pinfunction "GND_GND4") (pintype "bidirectional"))
      (node (ref "C55") (pin "GND5") (pinfunction "GND_GND5") (pintype "bidirectional"))
      (node (ref "C55") (pin "GND6") (pinfunction "GND_GND6") (pintype "bidirectional"))
      (node (ref "C55") (pin "GND7") (pinfunction "GND_GND7") (pintype "bidirectional"))
      (node (ref "C55") (pin "GND8") (pinfunction "GND_GND8") (pintype "bidirectional"))
      (node (ref "C56") (pin "GND1") (pinfunction "GND_GND1") (pintype "bidirectional"))
      (node (ref "C56") (pin "GND2") (pinfunction "GND_GND2") (pintype "bidirectional"))
      (node (ref "C56") (pin "GND3") (pinfunction "GND_GND3") (pintype "bidirectional"))
      (node (ref "C56") (pin "GND4") (pinfunction "GND_GND4") (pintype "bidirectional"))
      (node (ref "C56") (pin "GND5") (pinfunction "GND_GND5") (pintype "bidirectional"))
      (node (ref "C56") (pin "GND6") (pinfunction "GND_GND6") (pintype "bidirectional"))
      (node (ref "C56") (pin "GND7") (pinfunction "GND_GND7") (pintype "bidirectional"))
      (node (ref "C56") (pin "GND8") (pinfunction "GND_GND8") (pintype "bidirectional"))
      (node (ref "C58") (pin "2") (pinfunction "2_2") (pintype "passive"))
      (node (ref "C6") (pin "2") (pinfunction "2_2") (pintype "passive"))
      (node (ref "C60") (pin "GND1") (pinfunction "GND_GND1") (pintype "bidirectional"))
      (node (ref "C60") (pin "GND2") (pinfunction "GND_GND2") (pintype "bidirectional"))
      (node (ref "C60") (pin "GND3") (pinfunction "GND_GND3") (pintype "bidirectional"))
      (node (ref "C60") (pin "GND4") (pinfunction "GND_GND4") (pintype "bidirectional"))
      (node (ref "C60") (pin "GND5") (pinfunction "GND_GND5") (pintype "bidirectional"))
      (node (ref "C60") (pin "GND6") (pinfunction "GND_GND6") (pintype "bidirectional"))
      (node (ref "C60") (pin "GND7") (pinfunction "GND_GND7") (pintype "bidirectional"))
      (node (ref "C60") (pin "GND8") (pinfunction "GND_GND8") (pintype "bidirectional"))
      (node (ref "C61") (pin "GND1") (pinfunction "GND_GND1") (pintype "bidirectional"))
      (node (ref "C61") (pin "GND2") (pinfunction "GND_GND2") (pintype "bidirectional"))
      (node (ref "C61") (pin "GND3") (pinfunction "GND_GND3") (pintype "bidirectional"))
      (node (ref "C61") (pin "GND4") (pinfunction "GND_GND4") (pintype "bidirectional"))
      (node (ref "C61") (pin "GND5") (pinfunction "GND_GND5") (pintype "bidirectional"))
      (node (ref "C61") (pin "GND6") (pinfunction "GND_GND6") (pintype "bidirectional"))
      (node (ref "C61") (pin "GND7") (pinfunction "GND_GND7") (pintype "bidirectional"))
      (node (ref "C61") (pin "GND8") (pinfunction "GND_GND8") (pintype "bidirectional"))
      (node (ref "C62") (pin "2") (pinfunction "2_2") (pintype "passive"))
      (node (ref "C64") (pin "GND1") (pinfunction "GND_GND1") (pintype "bidirectional"))
      (node (ref "C64") (pin "GND2") (pinfunction "GND_GND2") (pintype "bidirectional"))
      (node (ref "C64") (pin "GND3") (pinfunction "GND_GND3") (pintype "bidirectional"))
      (node (ref "C64") (pin "GND4") (pinfunction "GND_GND4") (pintype "bidirectional"))
      (node (ref "C64") (pin "GND5") (pinfunction "GND_GND5") (pintype "bidirectional"))
      (node (ref "C64") (pin "GND6") (pinfunction "GND_GND6") (pintype "bidirectional"))
      (node (ref "C64") (pin "GND7") (pinfunction "GND_GND7") (pintype "bidirectional"))
      (node (ref "C64") (pin "GND8") (pinfunction "GND_GND8") (pintype "bidirectional"))
      (node (ref "C65") (pin "GND1") (pinfunction "GND_GND1") (pintype "bidirectional"))
      (node (ref "C65") (pin "GND2") (pinfunction "GND_GND2") (pintype "bidirectional"))
      (node (ref "C65") (pin "GND3") (pinfunction "GND_GND3") (pintype "bidirectional"))
      (node (ref "C65") (pin "GND4") (pinfunction "GND_GND4") (pintype "bidirectional"))
      (node (ref "C65") (pin "GND5") (pinfunction "GND_GND5") (pintype "bidirectional"))
      (node (ref "C65") (pin "GND6") (pinfunction "GND_GND6") (pintype "bidirectional"))
      (node (ref "C65") (pin "GND7") (pinfunction "GND_GND7") (pintype "bidirectional"))
      (node (ref "C65") (pin "GND8") (pinfunction "GND_GND8") (pintype "bidirectional"))
      (node (ref "C66") (pin "2") (pinfunction "2_2") (pintype "passive"))
      (node (ref "C68") (pin "GND1") (pinfunction "GND_GND1") (pintype "bidirectional"))
      (node (ref "C68") (pin "GND2") (pinfunction "GND_GND2") (pintype "bidirectional"))
      (node (ref "C68") (pin "GND3") (pinfunction "GND_GND3") (pintype "bidirectional"))
      (node (ref "C68") (pin "GND4") (pinfunction "GND_GND4") (pintype "bidirectional"))
      (node (ref "C68") (pin "GND5") (pinfunction "GND_GND5") (pintype "bidirectional"))
      (node (ref "C68") (pin "GND6") (pinfunction "GND_GND6") (pintype "bidirectional"))
      (node (ref "C68") (pin "GND7") (pinfunction "GND_GND7") (pintype "bidirectional"))
      (node (ref "C68") (pin "GND8") (pinfunction "GND_GND8") (pintype "bidirectional"))
      (node (ref "C69") (pin "GND1") (pinfunction "GND_GND1") (pintype "bidirectional"))
      (node (ref "C69") (pin "GND2") (pinfunction "GND_GND2") (pintype "bidirectional"))
      (node (ref "C69") (pin "GND3") (pinfunction "GND_GND3") (pintype "bidirectional"))
      (node (ref "C69") (pin "GND4") (pinfunction "GND_GND4") (pintype "bidirectional"))
      (node (ref "C69") (pin "GND5") (pinfunction "GND_GND5") (pintype "bidirectional"))
      (node (ref "C69") (pin "GND6") (pinfunction "GND_GND6") (pintype "bidirectional"))
      (node (ref "C69") (pin "GND7") (pinfunction "GND_GND7") (pintype "bidirectional"))
      (node (ref "C69") (pin "GND8") (pinfunction "GND_GND8") (pintype "bidirectional"))
      (node (ref "C7") (pin "2") (pinfunction "2_2") (pintype "passive"))
      (node (ref "C70") (pin "2") (pinfunction "2_2") (pintype "passive"))
      (node (ref "C73") (pin "2") (pinfunction "2_2") (pintype "passive"))
      (node (ref "C74") (pin "GND1") (pinfunction "GND_GND1") (pintype "bidirectional"))
      (node (ref "C74") (pin "GND2") (pinfunction "GND_GND2") (pintype "bidirectional"))
      (node (ref "C74") (pin "GND3") (pinfunction "GND_GND3") (pintype "bidirectional"))
      (node (ref "C74") (pin "GND4") (pinfunction "GND_GND4") (pintype "bidirectional"))
      (node (ref "C74") (pin "GND5") (pinfunction "GND_GND5") (pintype "bidirectional"))
      (node (ref "C74") (pin "GND6") (pinfunction "GND_GND6") (pintype "bidirectional"))
      (node (ref "C74") (pin "GND7") (pinfunction "GND_GND7") (pintype "bidirectional"))
      (node (ref "C74") (pin "GND8") (pinfunction "GND_GND8") (pintype "bidirectional"))
      (node (ref "C75") (pin "GND1") (pinfunction "GND_GND1") (pintype "bidirectional"))
      (node (ref "C75") (pin "GND2") (pinfunction "GND_GND2") (pintype "bidirectional"))
      (node (ref "C75") (pin "GND3") (pinfunction "GND_GND3") (pintype "bidirectional"))
      (node (ref "C75") (pin "GND4") (pinfunction "GND_GND4") (pintype "bidirectional"))
      (node (ref "C75") (pin "GND5") (pinfunction "GND_GND5") (pintype "bidirectional"))
      (node (ref "C75") (pin "GND6") (pinfunction "GND_GND6") (pintype "bidirectional"))
      (node (ref "C75") (pin "GND7") (pinfunction "GND_GND7") (pintype "bidirectional"))
      (node (ref "C75") (pin "GND8") (pinfunction "GND_GND8") (pintype "bidirectional"))
      (node (ref "C76") (pin "2") (pinfunction "2_2") (pintype "passive"))
      (node (ref "C78") (pin "GND1") (pinfunction "GND_GND1") (pintype "bidirectional"))
      (node (ref "C78") (pin "GND2") (pinfunction "GND_GND2") (pintype "bidirectional"))
      (node (ref "C78") (pin "GND3") (pinfunction "GND_GND3") (pintype "bidirectional"))
      (node (ref "C78") (pin "GND4") (pinfunction "GND_GND4") (pintype "bidirectional"))
      (node (ref "C78") (pin "GND5") (pinfunction "GND_GND5") (pintype "bidirectional"))
      (node (ref "C78") (pin "GND6") (pinfunction "GND_GND6") (pintype "bidirectional"))
      (node (ref "C78") (pin "GND7") (pinfunction "GND_GND7") (pintype "bidirectional"))
      (node (ref "C78") (pin "GND8") (pinfunction "GND_GND8") (pintype "bidirectional"))
      (node (ref "C79") (pin "GND1") (pinfunction "GND_GND1") (pintype "bidirectional"))
      (node (ref "C79") (pin "GND2") (pinfunction "GND_GND2") (pintype "bidirectional"))
      (node (ref "C79") (pin "GND3") (pinfunction "GND_GND3") (pintype "bidirectional"))
      (node (ref "C79") (pin "GND4") (pinfunction "GND_GND4") (pintype "bidirectional"))
      (node (ref "C79") (pin "GND5") (pinfunction "GND_GND5") (pintype "bidirectional"))
      (node (ref "C79") (pin "GND6") (pinfunction "GND_GND6") (pintype "bidirectional"))
      (node (ref "C79") (pin "GND7") (pinfunction "GND_GND7") (pintype "bidirectional"))
      (node (ref "C79") (pin "GND8") (pinfunction "GND_GND8") (pintype "bidirectional"))
      (node (ref "C80") (pin "2") (pinfunction "2_2") (pintype "passive"))
      (node (ref "C82") (pin "GND1") (pinfunction "GND_GND1") (pintype "bidirectional"))
      (node (ref "C82") (pin "GND2") (pinfunction "GND_GND2") (pintype "bidirectional"))
      (node (ref "C82") (pin "GND3") (pinfunction "GND_GND3") (pintype "bidirectional"))
      (node (ref "C82") (pin "GND4") (pinfunction "GND_GND4") (pintype "bidirectional"))
      (node (ref "C82") (pin "GND5") (pinfunction "GND_GND5") (pintype "bidirectional"))
      (node (ref "C82") (pin "GND6") (pinfunction "GND_GND6") (pintype "bidirectional"))
      (node (ref "C82") (pin "GND7") (pinfunction "GND_GND7") (pintype "bidirectional"))
      (node (ref "C82") (pin "GND8") (pinfunction "GND_GND8") (pintype "bidirectional"))
      (node (ref "C83") (pin "GND1") (pinfunction "GND_GND1") (pintype "bidirectional"))
      (node (ref "C83") (pin "GND2") (pinfunction "GND_GND2") (pintype "bidirectional"))
      (node (ref "C83") (pin "GND3") (pinfunction "GND_GND3") (pintype "bidirectional"))
      (node (ref "C83") (pin "GND4") (pinfunction "GND_GND4") (pintype "bidirectional"))
      (node (ref "C83") (pin "GND5") (pinfunction "GND_GND5") (pintype "bidirectional"))
      (node (ref "C83") (pin "GND6") (pinfunction "GND_GND6") (pintype "bidirectional"))
      (node (ref "C83") (pin "GND7") (pinfunction "GND_GND7") (pintype "bidirectional"))
      (node (ref "C83") (pin "GND8") (pinfunction "GND_GND8") (pintype "bidirectional"))
      (node (ref "C84") (pin "2") (pinfunction "2_2") (pintype "passive"))
      (node (ref "C86") (pin "GND1") (pinfunction "GND_GND1") (pintype "bidirectional"))
      (node (ref "C86") (pin "GND2") (pinfunction "GND_GND2") (pintype "bidirectional"))
      (node (ref "C86") (pin "GND3") (pinfunction "GND_GND3") (pintype "bidirectional"))
      (node (ref "C86") (pin "GND4") (pinfunction "GND_GND4") (pintype "bidirectional"))
      (node (ref "C86") (pin "GND5") (pinfunction "GND_GND5") (pintype "bidirectional"))
      (node (ref "C86") (pin "GND6") (pinfunction "GND_GND6") (pintype "bidirectional"))
      (node (ref "C86") (pin "GND7") (pinfunction "GND_GND7") (pintype "bidirectional"))
      (node (ref "C86") (pin "GND8") (pinfunction "GND_GND8") (pintype "bidirectional"))
      (node (ref "C87") (pin "GND1") (pinfunction "GND_GND1") (pintype "bidirectional"))
      (node (ref "C87") (pin "GND2") (pinfunction "GND_GND2") (pintype "bidirectional"))
      (node (ref "C87") (pin "GND3") (pinfunction "GND_GND3") (pintype "bidirectional"))
      (node (ref "C87") (pin "GND4") (pinfunction "GND_GND4") (pintype "bidirectional"))
      (node (ref "C87") (pin "GND5") (pinfunction "GND_GND5") (pintype "bidirectional"))
      (node (ref "C87") (pin "GND6") (pinfunction "GND_GND6") (pintype "bidirectional"))
      (node (ref "C87") (pin "GND7") (pinfunction "GND_GND7") (pintype "bidirectional"))
      (node (ref "C87") (pin "GND8") (pinfunction "GND_GND8") (pintype "bidirectional"))
      (node (ref "C88") (pin "2") (pinfunction "2_2") (pintype "passive"))
      (node (ref "C90") (pin "GND1") (pinfunction "GND_GND1") (pintype "bidirectional"))
      (node (ref "C90") (pin "GND2") (pinfunction "GND_GND2") (pintype "bidirectional"))
      (node (ref "C90") (pin "GND3") (pinfunction "GND_GND3") (pintype "bidirectional"))
      (node (ref "C90") (pin "GND4") (pinfunction "GND_GND4") (pintype "bidirectional"))
      (node (ref "C90") (pin "GND5") (pinfunction "GND_GND5") (pintype "bidirectional"))
      (node (ref "C90") (pin "GND6") (pinfunction "GND_GND6") (pintype "bidirectional"))
      (node (ref "C90") (pin "GND7") (pinfunction "GND_GND7") (pintype "bidirectional"))
      (node (ref "C90") (pin "GND8") (pinfunction "GND_GND8") (pintype "bidirectional"))
      (node (ref "C91") (pin "GND1") (pinfunction "GND_GND1") (pintype "bidirectional"))
      (node (ref "C91") (pin "GND2") (pinfunction "GND_GND2") (pintype "bidirectional"))
      (node (ref "C91") (pin "GND3") (pinfunction "GND_GND3") (pintype "bidirectional"))
      (node (ref "C91") (pin "GND4") (pinfunction "GND_GND4") (pintype "bidirectional"))
      (node (ref "C91") (pin "GND5") (pinfunction "GND_GND5") (pintype "bidirectional"))
      (node (ref "C91") (pin "GND6") (pinfunction "GND_GND6") (pintype "bidirectional"))
      (node (ref "C91") (pin "GND7") (pinfunction "GND_GND7") (pintype "bidirectional"))
      (node (ref "C91") (pin "GND8") (pinfunction "GND_GND8") (pintype "bidirectional"))
      (node (ref "C92") (pin "2") (pinfunction "2_2") (pintype "passive"))
      (node (ref "C94") (pin "GND1") (pinfunction "GND_GND1") (pintype "bidirectional"))
      (node (ref "C94") (pin "GND2") (pinfunction "GND_GND2") (pintype "bidirectional"))
      (node (ref "C94") (pin "GND3") (pinfunction "GND_GND3") (pintype "bidirectional"))
      (node (ref "C94") (pin "GND4") (pinfunction "GND_GND4") (pintype "bidirectional"))
      (node (ref "C94") (pin "GND5") (pinfunction "GND_GND5") (pintype "bidirectional"))
      (node (ref "C94") (pin "GND6") (pinfunction "GND_GND6") (pintype "bidirectional"))
      (node (ref "C94") (pin "GND7") (pinfunction "GND_GND7") (pintype "bidirectional"))
      (node (ref "C94") (pin "GND8") (pinfunction "GND_GND8") (pintype "bidirectional"))
      (node (ref "C95") (pin "GND1") (pinfunction "GND_GND1") (pintype "bidirectional"))
      (node (ref "C95") (pin "GND2") (pinfunction "GND_GND2") (pintype "bidirectional"))
      (node (ref "C95") (pin "GND3") (pinfunction "GND_GND3") (pintype "bidirectional"))
      (node (ref "C95") (pin "GND4") (pinfunction "GND_GND4") (pintype "bidirectional"))
      (node (ref "C95") (pin "GND5") (pinfunction "GND_GND5") (pintype "bidirectional"))
      (node (ref "C95") (pin "GND6") (pinfunction "GND_GND6") (pintype "bidirectional"))
      (node (ref "C95") (pin "GND7") (pinfunction "GND_GND7") (pintype "bidirectional"))
      (node (ref "C95") (pin "GND8") (pinfunction "GND_GND8") (pintype "bidirectional"))
      (node (ref "C96") (pin "2") (pinfunction "2_2") (pintype "passive"))
      (node (ref "C98") (pin "GND1") (pinfunction "GND_GND1") (pintype "bidirectional"))
      (node (ref "C98") (pin "GND2") (pinfunction "GND_GND2") (pintype "bidirectional"))
      (node (ref "C98") (pin "GND3") (pinfunction "GND_GND3") (pintype "bidirectional"))
      (node (ref "C98") (pin "GND4") (pinfunction "GND_GND4") (pintype "bidirectional"))
      (node (ref "C98") (pin "GND5") (pinfunction "GND_GND5") (pintype "bidirectional"))
      (node (ref "C98") (pin "GND6") (pinfunction "GND_GND6") (pintype "bidirectional"))
      (node (ref "C98") (pin "GND7") (pinfunction "GND_GND7") (pintype "bidirectional"))
      (node (ref "C98") (pin "GND8") (pinfunction "GND_GND8") (pintype "bidirectional"))
      (node (ref "C99") (pin "GND1") (pinfunction "GND_GND1") (pintype "bidirectional"))
      (node (ref "C99") (pin "GND2") (pinfunction "GND_GND2") (pintype "bidirectional"))
      (node (ref "C99") (pin "GND3") (pinfunction "GND_GND3") (pintype "bidirectional"))
      (node (ref "C99") (pin "GND4") (pinfunction "GND_GND4") (pintype "bidirectional"))
      (node (ref "C99") (pin "GND5") (pinfunction "GND_GND5") (pintype "bidirectional"))
      (node (ref "C99") (pin "GND6") (pinfunction "GND_GND6") (pintype "bidirectional"))
      (node (ref "C99") (pin "GND7") (pinfunction "GND_GND7") (pintype "bidirectional"))
      (node (ref "C99") (pin "GND8") (pinfunction "GND_GND8") (pintype "bidirectional"))
      (node (ref "IC1") (pin "1") (pinfunction "GND_1_1") (pintype "bidirectional"))
      (node (ref "IC1") (pin "2") (pinfunction "GND_2_2") (pintype "bidirectional"))
      (node (ref "IC1") (pin "4") (pinfunction "GND_3_4") (pintype "bidirectional"))
      (node (ref "IC1") (pin "5") (pinfunction "GND_4_5") (pintype "bidirectional"))
      (node (ref "IC1") (pin "8") (pinfunction "GND_5_8") (pintype "bidirectional"))
      (node (ref "IC58") (pin "2") (pinfunction "AGND_2") (pintype "bidirectional"))
      (node (ref "IC58") (pin "20") (pinfunction "PGND_20") (pintype "bidirectional"))
      (node (ref "IC58") (pin "21") (pinfunction "PGND_21") (pintype "bidirectional"))
      (node (ref "IC58") (pin "23") (pinfunction "AGND_23") (pintype "bidirectional"))
      (node (ref "IC58") (pin "29") (pinfunction "STSEL_29") (pintype "bidirectional"))
      (node (ref "IC58") (pin "31") (pinfunction "PGND_31") (pintype "bidirectional"))
      (node (ref "IC58") (pin "32") (pinfunction "PGND_32") (pintype "bidirectional"))
      (node (ref "IC58") (pin "33") (pinfunction "PGND_33") (pintype "bidirectional"))
      (node (ref "J1") (pin "1") (pinfunction "S_1") (pintype "passive"))
      (node (ref "L17") (pin "1") (pinfunction "1_1") (pintype "passive"))
      (node (ref "L2") (pin "1") (pinfunction "1_1") (pintype "passive"))
      (node (ref "L22") (pin "1") (pinfunction "1_1") (pintype "passive"))
      (node (ref "L24") (pin "1") (pinfunction "1_1") (pintype "passive"))
      (node (ref "L26") (pin "1") (pinfunction "1_1") (pintype "passive"))
      (node (ref "L28") (pin "1") (pinfunction "1_1") (pintype "passive"))
      (node (ref "L3") (pin "1") (pinfunction "1_1") (pintype "passive"))
      (node (ref "L32") (pin "1") (pinfunction "1_1") (pintype "passive"))
      (node (ref "L5") (pin "1") (pinfunction "1_1") (pintype "passive"))
      (node (ref "L6") (pin "1") (pinfunction "1_1") (pintype "passive"))
      (node (ref "L8") (pin "1") (pinfunction "1_1") (pintype "passive"))
      (node (ref "L9") (pin "1") (pinfunction "1_1") (pintype "passive"))
      (node (ref "LDO_1") (pin "4") (pinfunction "GND_4") (pintype "bidirectional"))
      (node (ref "LDO_1") (pin "P1") (pinfunction "GND_P1") (pintype "bidirectional"))
      (node (ref "LDO_1") (pin "P2") (pinfunction "GND_P2") (pintype "bidirectional"))
      (node (ref "LDO_1") (pin "P3") (pinfunction "GND_P3") (pintype "bidirectional"))
      (node (ref "LDO_1") (pin "P4") (pinfunction "GND_P4") (pintype "bidirectional"))
      (node (ref "LDO_1") (pin "P5") (pinfunction "GND_P5") (pintype "bidirectional"))
      (node (ref "LDO_1") (pin "PAD") (pinfunction "GND_PAD") (pintype "bidirectional"))
      (node (ref "LDO_10") (pin "4") (pinfunction "GND_4") (pintype "bidirectional"))
      (node (ref "LDO_10") (pin "P1") (pinfunction "GND_P1") (pintype "bidirectional"))
      (node (ref "LDO_10") (pin "P2") (pinfunction "GND_P2") (pintype "bidirectional"))
      (node (ref "LDO_10") (pin "P3") (pinfunction "GND_P3") (pintype "bidirectional"))
      (node (ref "LDO_10") (pin "P4") (pinfunction "GND_P4") (pintype "bidirectional"))
      (node (ref "LDO_10") (pin "P5") (pinfunction "GND_P5") (pintype "bidirectional"))
      (node (ref "LDO_10") (pin "PAD") (pinfunction "GND_PAD") (pintype "bidirectional"))
      (node (ref "LDO_11") (pin "4") (pinfunction "GND_4") (pintype "bidirectional"))
      (node (ref "LDO_11") (pin "P1") (pinfunction "GND_P1") (pintype "bidirectional"))
      (node (ref "LDO_11") (pin "P2") (pinfunction "GND_P2") (pintype "bidirectional"))
      (node (ref "LDO_11") (pin "P3") (pinfunction "GND_P3") (pintype "bidirectional"))
      (node (ref "LDO_11") (pin "P4") (pinfunction "GND_P4") (pintype "bidirectional"))
      (node (ref "LDO_11") (pin "P5") (pinfunction "GND_P5") (pintype "bidirectional"))
      (node (ref "LDO_11") (pin "PAD") (pinfunction "GND_PAD") (pintype "bidirectional"))
      (node (ref "LDO_2") (pin "4") (pinfunction "GND_4") (pintype "bidirectional"))
      (node (ref "LDO_2") (pin "P1") (pinfunction "GND_P1") (pintype "bidirectional"))
      (node (ref "LDO_2") (pin "P2") (pinfunction "GND_P2") (pintype "bidirectional"))
      (node (ref "LDO_2") (pin "P3") (pinfunction "GND_P3") (pintype "bidirectional"))
      (node (ref "LDO_2") (pin "P4") (pinfunction "GND_P4") (pintype "bidirectional"))
      (node (ref "LDO_2") (pin "P5") (pinfunction "GND_P5") (pintype "bidirectional"))
      (node (ref "LDO_2") (pin "PAD") (pinfunction "GND_PAD") (pintype "bidirectional"))
      (node (ref "LDO_3") (pin "4") (pinfunction "GND_4") (pintype "bidirectional"))
      (node (ref "LDO_3") (pin "P1") (pinfunction "GND_P1") (pintype "bidirectional"))
      (node (ref "LDO_3") (pin "P2") (pinfunction "GND_P2") (pintype "bidirectional"))
      (node (ref "LDO_3") (pin "P3") (pinfunction "GND_P3") (pintype "bidirectional"))
      (node (ref "LDO_3") (pin "P4") (pinfunction "GND_P4") (pintype "bidirectional"))
      (node (ref "LDO_3") (pin "P5") (pinfunction "GND_P5") (pintype "bidirectional"))
      (node (ref "LDO_3") (pin "PAD") (pinfunction "GND_PAD") (pintype "bidirectional"))
      (node (ref "LDO_4") (pin "4") (pinfunction "GND_4") (pintype "bidirectional"))
      (node (ref "LDO_4") (pin "P1") (pinfunction "GND_P1") (pintype "bidirectional"))
      (node (ref "LDO_4") (pin "P2") (pinfunction "GND_P2") (pintype "bidirectional"))
      (node (ref "LDO_4") (pin "P3") (pinfunction "GND_P3") (pintype "bidirectional"))
      (node (ref "LDO_4") (pin "P4") (pinfunction "GND_P4") (pintype "bidirectional"))
      (node (ref "LDO_4") (pin "P5") (pinfunction "GND_P5") (pintype "bidirectional"))
      (node (ref "LDO_4") (pin "PAD") (pinfunction "GND_PAD") (pintype "bidirectional"))
      (node (ref "LDO_5") (pin "4") (pinfunction "GND_4") (pintype "bidirectional"))
      (node (ref "LDO_5") (pin "P1") (pinfunction "GND_P1") (pintype "bidirectional"))
      (node (ref "LDO_5") (pin "P2") (pinfunction "GND_P2") (pintype "bidirectional"))
      (node (ref "LDO_5") (pin "P3") (pinfunction "GND_P3") (pintype "bidirectional"))
      (node (ref "LDO_5") (pin "P4") (pinfunction "GND_P4") (pintype "bidirectional"))
      (node (ref "LDO_5") (pin "P5") (pinfunction "GND_P5") (pintype "bidirectional"))
      (node (ref "LDO_5") (pin "PAD") (pinfunction "GND_PAD") (pintype "bidirectional"))
      (node (ref "LDO_6") (pin "4") (pinfunction "GND_4") (pintype "bidirectional"))
      (node (ref "LDO_6") (pin "P1") (pinfunction "GND_P1") (pintype "bidirectional"))
      (node (ref "LDO_6") (pin "P2") (pinfunction "GND_P2") (pintype "bidirectional"))
      (node (ref "LDO_6") (pin "P3") (pinfunction "GND_P3") (pintype "bidirectional"))
      (node (ref "LDO_6") (pin "P4") (pinfunction "GND_P4") (pintype "bidirectional"))
      (node (ref "LDO_6") (pin "P5") (pinfunction "GND_P5") (pintype "bidirectional"))
      (node (ref "LDO_6") (pin "PAD") (pinfunction "GND_PAD") (pintype "bidirectional"))
      (node (ref "LDO_7") (pin "4") (pinfunction "GND_4") (pintype "bidirectional"))
      (node (ref "LDO_7") (pin "P1") (pinfunction "GND_P1") (pintype "bidirectional"))
      (node (ref "LDO_7") (pin "P2") (pinfunction "GND_P2") (pintype "bidirectional"))
      (node (ref "LDO_7") (pin "P3") (pinfunction "GND_P3") (pintype "bidirectional"))
      (node (ref "LDO_7") (pin "P4") (pinfunction "GND_P4") (pintype "bidirectional"))
      (node (ref "LDO_7") (pin "P5") (pinfunction "GND_P5") (pintype "bidirectional"))
      (node (ref "LDO_7") (pin "PAD") (pinfunction "GND_PAD") (pintype "bidirectional"))
      (node (ref "LDO_8") (pin "4") (pinfunction "GND_4") (pintype "bidirectional"))
      (node (ref "LDO_8") (pin "P1") (pinfunction "GND_P1") (pintype "bidirectional"))
      (node (ref "LDO_8") (pin "P2") (pinfunction "GND_P2") (pintype "bidirectional"))
      (node (ref "LDO_8") (pin "P3") (pinfunction "GND_P3") (pintype "bidirectional"))
      (node (ref "LDO_8") (pin "P4") (pinfunction "GND_P4") (pintype "bidirectional"))
      (node (ref "LDO_8") (pin "P5") (pinfunction "GND_P5") (pintype "bidirectional"))
      (node (ref "LDO_8") (pin "PAD") (pinfunction "GND_PAD") (pintype "bidirectional"))
      (node (ref "LDO_9") (pin "4") (pinfunction "GND_4") (pintype "bidirectional"))
      (node (ref "LDO_9") (pin "P1") (pinfunction "GND_P1") (pintype "bidirectional"))
      (node (ref "LDO_9") (pin "P2") (pinfunction "GND_P2") (pintype "bidirectional"))
      (node (ref "LDO_9") (pin "P3") (pinfunction "GND_P3") (pintype "bidirectional"))
      (node (ref "LDO_9") (pin "P4") (pinfunction "GND_P4") (pintype "bidirectional"))
      (node (ref "LDO_9") (pin "P5") (pinfunction "GND_P5") (pintype "bidirectional"))
      (node (ref "LDO_9") (pin "PAD") (pinfunction "GND_PAD") (pintype "bidirectional"))
      (node (ref "LED1") (pin "C") (pinfunction "C_C") (pintype "passive"))
      (node (ref "LNA_1") (pin "2") (pinfunction "GND_2") (pintype "bidirectional"))
      (node (ref "LNA_1") (pin "4") (pinfunction "GND_1_4") (pintype "bidirectional"))
      (node (ref "LNA_10") (pin "2") (pinfunction "GND_2") (pintype "bidirectional"))
      (node (ref "LNA_10") (pin "4") (pinfunction "GND_1_4") (pintype "bidirectional"))
      (node (ref "LNA_11") (pin "2") (pinfunction "GND_2") (pintype "bidirectional"))
      (node (ref "LNA_11") (pin "4") (pinfunction "GND_1_4") (pintype "bidirectional"))
      (node (ref "LNA_2") (pin "2") (pinfunction "GND_2") (pintype "bidirectional"))
      (node (ref "LNA_2") (pin "4") (pinfunction "GND_1_4") (pintype "bidirectional"))
      (node (ref "LNA_3") (pin "2") (pinfunction "GND_2") (pintype "bidirectional"))
      (node (ref "LNA_3") (pin "4") (pinfunction "GND_1_4") (pintype "bidirectional"))
      (node (ref "LNA_4") (pin "2") (pinfunction "GND_2") (pintype "bidirectional"))
      (node (ref "LNA_4") (pin "4") (pinfunction "GND_1_4") (pintype "bidirectional"))
      (node (ref "LNA_5") (pin "2") (pinfunction "GND_2") (pintype "bidirectional"))
      (node (ref "LNA_5") (pin "4") (pinfunction "GND_1_4") (pintype "bidirectional"))
      (node (ref "LNA_6") (pin "2") (pinfunction "GND_2") (pintype "bidirectional"))
      (node (ref "LNA_6") (pin "4") (pinfunction "GND_1_4") (pintype "bidirectional"))
      (node (ref "LNA_7") (pin "2") (pinfunction "GND_2") (pintype "bidirectional"))
      (node (ref "LNA_7") (pin "4") (pinfunction "GND_1_4") (pintype "bidirectional"))
      (node (ref "LNA_8") (pin "2") (pinfunction "GND_2") (pintype "bidirectional"))
      (node (ref "LNA_8") (pin "4") (pinfunction "GND_1_4") (pintype "bidirectional"))
      (node (ref "LNA_9") (pin "2") (pinfunction "GND_2") (pintype "bidirectional"))
      (node (ref "LNA_9") (pin "4") (pinfunction "GND_1_4") (pintype "bidirectional"))
      (node (ref "R1") (pin "2") (pinfunction "2_2") (pintype "passive"))
      (node (ref "R10") (pin "2") (pinfunction "2_2") (pintype "passive"))
      (node (ref "R13") (pin "1") (pinfunction "1_1") (pintype "passive"))
      (node (ref "R14") (pin "2") (pinfunction "2_2") (pintype "passive"))
      (node (ref "R17") (pin "1") (pinfunction "1_1") (pintype "passive"))
      (node (ref "R19") (pin "2") (pinfunction "2_2") (pintype "passive"))
      (node (ref "R205") (pin "1") (pinfunction "1_1") (pintype "passive"))
      (node (ref "R206") (pin "1") (pinfunction "1_1") (pintype "passive"))
      (node (ref "R23") (pin "2") (pinfunction "2_2") (pintype "passive"))
      (node (ref "R26") (pin "2") (pinfunction "2_2") (pintype "passive"))
      (node (ref "R29") (pin "2") (pinfunction "2_2") (pintype "passive"))
      (node (ref "R3") (pin "2") (pinfunction "2_2") (pintype "passive"))
      (node (ref "R32") (pin "2") (pinfunction "2_2") (pintype "passive"))
      (node (ref "R35") (pin "2") (pinfunction "2_2") (pintype "passive"))
      (node (ref "R38") (pin "2") (pinfunction "2_2") (pintype "passive"))
      (node (ref "R7") (pin "2") (pinfunction "2_2") (pintype "passive"))
      (node (ref "R8") (pin "1") (pinfunction "1_1") (pintype "passive"))
      (node (ref "SAW_1") (pin "2") (pinfunction "GND_1_2") (pintype "bidirectional"))
      (node (ref "SAW_1") (pin "3") (pinfunction "GND_2_3") (pintype "bidirectional"))
      (node (ref "SAW_1") (pin "4") (pinfunction "GND_3_4") (pintype "bidirectional"))
      (node (ref "SAW_1") (pin "5") (pinfunction "GND_4_5") (pintype "bidirectional"))
      (node (ref "SAW_1") (pin "6") (pinfunction "GND_5_6") (pintype "bidirectional"))
      (node (ref "SAW_1") (pin "7") (pinfunction "GND_6_7") (pintype "bidirectional"))
      (node (ref "SAW_10") (pin "1") (pinfunction "GND_1") (pintype "bidirectional"))
      (node (ref "SAW_10") (pin "3") (pinfunction "GND_1_3") (pintype "bidirectional"))
      (node (ref "SAW_10") (pin "4") (pinfunction "GND_2_4") (pintype "bidirectional"))
      (node (ref "SAW_10") (pin "6") (pinfunction "GND_3_6") (pintype "bidirectional"))
      (node (ref "SAW_11") (pin "1") (pinfunction "GND_1") (pintype "bidirectional"))
      (node (ref "SAW_11") (pin "3") (pinfunction "GND_1_3") (pintype "bidirectional"))
      (node (ref "SAW_11") (pin "4") (pinfunction "GND_2_4") (pintype "bidirectional"))
      (node (ref "SAW_11") (pin "6") (pinfunction "GND_3_6") (pintype "bidirectional"))
      (node (ref "SAW_12") (pin "1") (pinfunction "GND_1") (pintype "bidirectional"))
      (node (ref "SAW_12") (pin "3") (pinfunction "GND_1_3") (pintype "bidirectional"))
      (node (ref "SAW_12") (pin "4") (pinfunction "GND_2_4") (pintype "bidirectional"))
      (node (ref "SAW_12") (pin "6") (pinfunction "GND_3_6") (pintype "bidirectional"))
      (node (ref "SAW_2") (pin "1") (pinfunction "GND_1") (pintype "bidirectional"))
      (node (ref "SAW_2") (pin "3") (pinfunction "GND_1_3") (pintype "bidirectional"))
      (node (ref "SAW_2") (pin "4") (pinfunction "CASE_GND_4") (pintype "bidirectional"))
      (node (ref "SAW_2") (pin "5") (pinfunction "GND_2_5") (pintype "bidirectional"))
      (node (ref "SAW_2") (pin "7") (pinfunction "GND_3_7") (pintype "bidirectional"))
      (node (ref "SAW_2") (pin "8") (pinfunction "CASE_GND_1_8") (pintype "bidirectional"))
      (node (ref "SAW_3") (pin "1") (pinfunction "GND_1") (pintype "bidirectional"))
      (node (ref "SAW_3") (pin "3") (pinfunction "GND_1_3") (pintype "bidirectional"))
      (node (ref "SAW_3") (pin "4") (pinfunction "CASE_GND_4") (pintype "bidirectional"))
      (node (ref "SAW_3") (pin "5") (pinfunction "GND_2_5") (pintype "bidirectional"))
      (node (ref "SAW_3") (pin "7") (pinfunction "GND_3_7") (pintype "bidirectional"))
      (node (ref "SAW_3") (pin "8") (pinfunction "CASE_GND_1_8") (pintype "bidirectional"))
      (node (ref "SAW_4") (pin "1") (pinfunction "GND_1") (pintype "bidirectional"))
      (node (ref "SAW_4") (pin "3") (pinfunction "GND_1_3") (pintype "bidirectional"))
      (node (ref "SAW_4") (pin "4") (pinfunction "CASE_GND_4") (pintype "bidirectional"))
      (node (ref "SAW_4") (pin "5") (pinfunction "GND_2_5") (pintype "bidirectional"))
      (node (ref "SAW_4") (pin "7") (pinfunction "GND_3_7") (pintype "bidirectional"))
      (node (ref "SAW_4") (pin "8") (pinfunction "CASE_GND_1_8") (pintype "bidirectional"))
      (node (ref "SAW_5") (pin "1") (pinfunction "GND_1") (pintype "bidirectional"))
      (node (ref "SAW_5") (pin "3") (pinfunction "GND_1_3") (pintype "bidirectional"))
      (node (ref "SAW_5") (pin "4") (pinfunction "CASE_GND_4") (pintype "bidirectional"))
      (node (ref "SAW_5") (pin "5") (pinfunction "GND_2_5") (pintype "bidirectional"))
      (node (ref "SAW_5") (pin "7") (pinfunction "GND_3_7") (pintype "bidirectional"))
      (node (ref "SAW_5") (pin "8") (pinfunction "CASE_GND_1_8") (pintype "bidirectional"))
      (node (ref "SAW_6") (pin "1") (pinfunction "GND_1") (pintype "bidirectional"))
      (node (ref "SAW_6") (pin "3") (pinfunction "GND_1_3") (pintype "bidirectional"))
      (node (ref "SAW_6") (pin "4") (pinfunction "CASE_GND_4") (pintype "bidirectional"))
      (node (ref "SAW_6") (pin "5") (pinfunction "GND_2_5") (pintype "bidirectional"))
      (node (ref "SAW_6") (pin "7") (pinfunction "GND_3_7") (pintype "bidirectional"))
      (node (ref "SAW_6") (pin "8") (pinfunction "CASE_GND_1_8") (pintype "bidirectional"))
      (node (ref "SAW_7") (pin "1") (pinfunction "GND_1") (pintype "bidirectional"))
      (node (ref "SAW_7") (pin "3") (pinfunction "GND_1_3") (pintype "bidirectional"))
      (node (ref "SAW_7") (pin "4") (pinfunction "CASE_GND_4") (pintype "bidirectional"))
      (node (ref "SAW_7") (pin "5") (pinfunction "GND_2_5") (pintype "bidirectional"))
      (node (ref "SAW_7") (pin "7") (pinfunction "GND_3_7") (pintype "bidirectional"))
      (node (ref "SAW_7") (pin "8") (pinfunction "CASE_GND_1_8") (pintype "bidirectional"))
      (node (ref "SAW_8") (pin "1") (pinfunction "GND_1") (pintype "bidirectional"))
      (node (ref "SAW_8") (pin "3") (pinfunction "GND_1_3") (pintype "bidirectional"))
      (node (ref "SAW_8") (pin "4") (pinfunction "CASE_GND_4") (pintype "bidirectional"))
      (node (ref "SAW_8") (pin "5") (pinfunction "GND_2_5") (pintype "bidirectional"))
      (node (ref "SAW_8") (pin "7") (pinfunction "GND_3_7") (pintype "bidirectional"))
      (node (ref "SAW_8") (pin "8") (pinfunction "CASE_GND_1_8") (pintype "bidirectional"))
      (node (ref "SAW_9") (pin "1") (pinfunction "GND_1") (pintype "bidirectional"))
      (node (ref "SAW_9") (pin "3") (pinfunction "GND_1_3") (pintype "bidirectional"))
      (node (ref "SAW_9") (pin "4") (pinfunction "GND_2_4") (pintype "bidirectional"))
      (node (ref "SAW_9") (pin "6") (pinfunction "GND_3_6") (pintype "bidirectional"))
      (node (ref "X1") (pin "2") (pinfunction "GND_2") (pintype "power_in"))
      (node (ref "X10") (pin "2") (pinfunction "GND_2") (pintype "power_in"))
      (node (ref "X11") (pin "2") (pinfunction "GND_2") (pintype "power_in"))
      (node (ref "X12") (pin "2") (pinfunction "GND_2") (pintype "power_in"))
      (node (ref "X13") (pin "2") (pinfunction "GND_2") (pintype "power_in"))
      (node (ref "X14") (pin "2") (pinfunction "GND_2") (pintype "power_in"))
      (node (ref "X15") (pin "2") (pinfunction "GND_2") (pintype "power_in"))
      (node (ref "X16") (pin "2") (pinfunction "GND_2") (pintype "power_in"))
      (node (ref "X17") (pin "2") (pinfunction "GND_2") (pintype "power_in"))
      (node (ref "X18") (pin "2") (pinfunction "GND_2") (pintype "power_in"))
      (node (ref "X19") (pin "2") (pinfunction "GND_2") (pintype "power_in"))
      (node (ref "X2") (pin "2") (pinfunction "GND_2") (pintype "power_in"))
      (node (ref "X20") (pin "2") (pinfunction "GND_2") (pintype "power_in"))
      (node (ref "X21") (pin "2") (pinfunction "GND_2") (pintype "power_in"))
      (node (ref "X22") (pin "2") (pinfunction "GND_2") (pintype "power_in"))
      (node (ref "X23") (pin "2") (pinfunction "GND_2") (pintype "power_in"))
      (node (ref "X24") (pin "2") (pinfunction "GND_2") (pintype "power_in"))
      (node (ref "X25") (pin "2") (pinfunction "GND_2") (pintype "power_in"))
      (node (ref "X26") (pin "2") (pinfunction "GND_2") (pintype "power_in"))
      (node (ref "X27") (pin "2") (pinfunction "GND_2") (pintype "power_in"))
      (node (ref "X28") (pin "2") (pinfunction "GND_2") (pintype "power_in"))
      (node (ref "X29") (pin "2") (pinfunction "GND_2") (pintype "power_in"))
      (node (ref "X3") (pin "2") (pinfunction "GND_2") (pintype "power_in"))
      (node (ref "X30") (pin "2") (pinfunction "GND_2") (pintype "power_in"))
      (node (ref "X33") (pin "2") (pinfunction "GND_2") (pintype "power_in"))
      (node (ref "X4") (pin "2") (pinfunction "GND_2") (pintype "power_in"))
      (node (ref "X5") (pin "2") (pinfunction "GND_2") (pintype "power_in"))
      (node (ref "X6") (pin "2") (pinfunction "GND_2") (pintype "power_in"))
      (node (ref "X7") (pin "2") (pinfunction "GND_2") (pintype "power_in"))
      (node (ref "X8") (pin "2") (pinfunction "GND_2") (pintype "power_in"))
      (node (ref "X9") (pin "2") (pinfunction "GND_2") (pintype "power_in"))
    )
    (net (code "7") (name "Net-(C2-Pad1)") (class "Default")
      (node (ref "C2") (pin "1") (pinfunction "1_1") (pintype "passive"))
      (node (ref "C3") (pin "1") (pinfunction "1_1") (pintype "passive"))
      (node (ref "C54") (pin "2") (pinfunction "2_2") (pintype "passive"))
      (node (ref "C56") (pin "OUT") (pinfunction "OUT_OUT") (pintype "bidirectional"))
      (node (ref "L1") (pin "2") (pinfunction "2_2") (pintype "passive"))
      (node (ref "R2") (pin "1") (pinfunction "1_1") (pintype "passive"))
      (node (ref "TP_1") (pin "TP") (pinfunction "TP_TP") (pintype "input"))
    )
    (net (code "8") (name "Net-(C10-Pad1)") (class "Default")
      (node (ref "C10") (pin "1") (pinfunction "1_1") (pintype "passive"))
      (node (ref "C11") (pin "1") (pinfunction "1_1") (pintype "passive"))
      (node (ref "C63") (pin "2") (pinfunction "2_2") (pintype "passive"))
      (node (ref "C65") (pin "OUT") (pinfunction "OUT_OUT") (pintype "bidirectional"))
      (node (ref "L7") (pin "1") (pinfunction "1_1") (pintype "passive"))
      (node (ref "R9") (pin "1") (pinfunction "1_1") (pintype "passive"))
      (node (ref "TP_3") (pin "TP") (pinfunction "TP_TP") (pintype "input"))
    )
    (net (code "9") (name "Net-(C14-Pad1)") (class "Default")
      (node (ref "C14") (pin "1") (pinfunction "1_1") (pintype "passive"))
      (node (ref "X9") (pin "1") (pinfunction "1_1") (pintype "passive"))
    )
    (net (code "10") (name "Net-(C15-Pad1)") (class "Default")
      (node (ref "C15") (pin "1") (pinfunction "1_1") (pintype "passive"))
      (node (ref "C16") (pin "1") (pinfunction "1_1") (pintype "passive"))
      (node (ref "C67") (pin "2") (pinfunction "2_2") (pintype "passive"))
      (node (ref "C69") (pin "OUT") (pinfunction "OUT_OUT") (pintype "bidirectional"))
      (node (ref "L10") (pin "2") (pinfunction "2_2") (pintype "passive"))
      (node (ref "R12") (pin "1") (pinfunction "1_1") (pintype "passive"))
      (node (ref "TP_4") (pin "TP") (pinfunction "TP_TP") (pintype "input"))
    )
    (net (code "11") (name "Net-(C19-Pad1)") (class "Default")
      (node (ref "C19") (pin "1") (pinfunction "1_1") (pintype "passive"))
      (node (ref "C20") (pin "1") (pinfunction "1_1") (pintype "passive"))
      (node (ref "C71") (pin "2") (pinfunction "2_2") (pintype "passive"))
      (node (ref "C75") (pin "OUT") (pinfunction "OUT_OUT") (pintype "bidirectional"))
      (node (ref "L11") (pin "2") (pinfunction "2_2") (pintype "passive"))
      (node (ref "R16") (pin "1") (pinfunction "1_1") (pintype "passive"))
      (node (ref "TP_5") (pin "TP") (pinfunction "TP_TP") (pintype "input"))
    )
    (net (code "12") (name "Net-(C23-Pad1)") (class "Default")
      (node (ref "C23") (pin "1") (pinfunction "1_1") (pintype "passive"))
      (node (ref "C24") (pin "1") (pinfunction "1_1") (pintype "passive"))
      (node (ref "C77") (pin "2") (pinfunction "2_2") (pintype "passive"))
      (node (ref "C79") (pin "OUT") (pinfunction "OUT_OUT") (pintype "bidirectional"))
      (node (ref "L12") (pin "1") (pinfunction "1_1") (pintype "passive"))
      (node (ref "R22") (pin "1") (pinfunction "1_1") (pintype "passive"))
      (node (ref "TP_6") (pin "TP") (pinfunction "TP_TP") (pintype "input"))
    )
    (net (code "13") (name "Net-(C26-Pad1)") (class "Default")
      (node (ref "C26") (pin "1") (pinfunction "1_1") (pintype "passive"))
      (node (ref "X17") (pin "1") (pinfunction "1_1") (pintype "passive"))
    )
    (net (code "14") (name "Net-(C27-Pad1)") (class "Default")
      (node (ref "C27") (pin "1") (pinfunction "1_1") (pintype "passive"))
      (node (ref "C28") (pin "1") (pinfunction "1_1") (pintype "passive"))
      (node (ref "C81") (pin "2") (pinfunction "2_2") (pintype "passive"))
      (node (ref "C83") (pin "OUT") (pinfunction "OUT_OUT") (pintype "bidirectional"))
      (node (ref "L13") (pin "2") (pinfunction "2_2") (pintype "passive"))
      (node (ref "R25") (pin "1") (pinfunction "1_1") (pintype "passive"))
      (node (ref "TP_7") (pin "TP") (pinfunction "TP_TP") (pintype "input"))
    )
    (net (code "15") (name "Net-(C31-Pad1)") (class "Default")
      (node (ref "C31") (pin "1") (pinfunction "1_1") (pintype "passive"))
      (node (ref "C32") (pin "1") (pinfunction "1_1") (pintype "passive"))
      (node (ref "C85") (pin "2") (pinfunction "2_2") (pintype "passive"))
      (node (ref "C87") (pin "OUT") (pinfunction "OUT_OUT") (pintype "bidirectional"))
      (node (ref "L14") (pin "2") (pinfunction "2_2") (pintype "passive"))
      (node (ref "R28") (pin "1") (pinfunction "1_1") (pintype "passive"))
      (node (ref "TP_8") (pin "TP") (pinfunction "TP_TP") (pintype "input"))
    )
    (net (code "16") (name "Net-(C35-Pad1)") (class "Default")
      (node (ref "C35") (pin "1") (pinfunction "1_1") (pintype "passive"))
      (node (ref "C36") (pin "1") (pinfunction "1_1") (pintype "passive"))
      (node (ref "C89") (pin "2") (pinfunction "2_2") (pintype "passive"))
      (node (ref "C91") (pin "OUT") (pinfunction "OUT_OUT") (pintype "bidirectional"))
      (node (ref "L15") (pin "2") (pinfunction "2_2") (pintype "passive"))
      (node (ref "R31") (pin "1") (pinfunction "1_1") (pintype "passive"))
      (node (ref "TP_9") (pin "TP") (pinfunction "TP_TP") (pintype "input"))
    )
    (net (code "17") (name "Net-(C38-Pad1)") (class "Default")
      (node (ref "C38") (pin "1") (pinfunction "1_1") (pintype "passive"))
      (node (ref "R5") (pin "1") (pinfunction "1_1") (pintype "passive"))
    )
    (net (code "18") (name "Net-(C38-Pad2)") (class "Default")
      (node (ref "C38") (pin "2") (pinfunction "2_2") (pintype "passive"))
      (node (ref "L16") (pin "1") (pinfunction "1_1") (pintype "passive"))
    )
    (net (code "19") (name "Net-(C39-Pad1)") (class "Default")
      (node (ref "C39") (pin "1") (pinfunction "1_1") (pintype "passive"))
      (node (ref "C43") (pin "1") (pinfunction "1_1") (pintype "passive"))
      (node (ref "C51") (pin "1") (pinfunction "1_1") (pintype "passive"))
      (node (ref "L16") (pin "2") (pinfunction "2_2") (pintype "passive"))
      (node (ref "L17") (pin "2") (pinfunction "2_2") (pintype "passive"))
    )
    (net (code "20") (name "Net-(C40-Pad1)") (class "Default")
      (node (ref "C40") (pin "1") (pinfunction "1_1") (pintype "passive"))
      (node (ref "C41") (pin "1") (pinfunction "1_1") (pintype "passive"))
      (node (ref "C93") (pin "2") (pinfunction "2_2") (pintype "passive"))
      (node (ref "C95") (pin "OUT") (pinfunction "OUT_OUT") (pintype "bidirectional"))
      (node (ref "L18") (pin "2") (pinfunction "2_2") (pintype "passive"))
      (node (ref "R34") (pin "1") (pinfunction "1_1") (pintype "passive"))
      (node (ref "TP_10") (pin "TP") (pinfunction "TP_TP") (pintype "input"))
    )
    (net (code "21") (name "Net-(C42-Pad2)") (class "Default")
      (node (ref "C42") (pin "2") (pinfunction "2_2") (pintype "passive"))
      (node (ref "R11") (pin "2") (pinfunction "2_2") (pintype "passive"))
      (node (ref "X27") (pin "1") (pinfunction "1_1") (pintype "passive"))
    )
    (net (code "22") (name "Net-(C43-Pad2)") (class "Default")
      (node (ref "C43") (pin "2") (pinfunction "2_2") (pintype "passive"))
      (node (ref "L20") (pin "1") (pinfunction "1_1") (pintype "passive"))
    )
    (net (code "23") (name "Net-(C44-Pad1)") (class "Default")
      (node (ref "C44") (pin "1") (pinfunction "1_1") (pintype "passive"))
      (node (ref "C45") (pin "1") (pinfunction "1_1") (pintype "passive"))
      (node (ref "C97") (pin "2") (pinfunction "2_2") (pintype "passive"))
      (node (ref "C99") (pin "OUT") (pinfunction "OUT_OUT") (pintype "bidirectional"))
      (node (ref "L21") (pin "2") (pinfunction "2_2") (pintype "passive"))
      (node (ref "R37") (pin "1") (pinfunction "1_1") (pintype "passive"))
      (node (ref "TP_11") (pin "TP") (pinfunction "TP_TP") (pintype "input"))
    )
    (net (code "24") (name "Net-(C46-Pad1)") (class "Default")
      (node (ref "C46") (pin "1") (pinfunction "1_1") (pintype "passive"))
      (node (ref "C50") (pin "1") (pinfunction "1_1") (pintype "passive"))
      (node (ref "C52") (pin "1") (pinfunction "1_1") (pintype "passive"))
      (node (ref "L20") (pin "2") (pinfunction "2_2") (pintype "passive"))
      (node (ref "L22") (pin "2") (pinfunction "2_2") (pintype "passive"))
    )
    (net (code "25") (name "Net-(C47-Pad1)") (class "Default")
      (node (ref "C47") (pin "1") (pinfunction "1_1") (pintype "passive"))
      (node (ref "R15") (pin "1") (pinfunction "1_1") (pintype "passive"))
    )
    (net (code "26") (name "Net-(C47-Pad2)") (class "Default")
      (node (ref "C47") (pin "2") (pinfunction "2_2") (pintype "passive"))
      (node (ref "L23") (pin "1") (pinfunction "1_1") (pintype "passive"))
    )
    (net (code "27") (name "Net-(C49-Pad2)") (class "Default")
      (node (ref "C49") (pin "2") (pinfunction "2_2") (pintype "passive"))
      (node (ref "L30") (pin "1") (pinfunction "1_1") (pintype "passive"))
    )
    (net (code "28") (name "Net-(C50-Pad2)") (class "Default")
      (node (ref "C50") (pin "2") (pinfunction "2_2") (pintype "passive"))
      (node (ref "L25") (pin "1") (pinfunction "1_1") (pintype "passive"))
    )
    (net (code "29") (name "Net-(C55-PadOUT)") (class "Default")
      (node (ref "C55") (pin "OUT") (pinfunction "OUT_OUT") (pintype "bidirectional"))
      (node (ref "LDO_1") (pin "7") (pinfunction "IN_7") (pintype "bidirectional"))
      (node (ref "LDO_1") (pin "8") (pinfunction "IN_8") (pintype "bidirectional"))
    )
    (net (code "30") (name "Net-(C56-PadIN)") (class "Default")
      (node (ref "C56") (pin "IN") (pinfunction "IN_IN") (pintype "bidirectional"))
      (node (ref "LDO_1") (pin "1") (pinfunction "OUT_1") (pintype "bidirectional"))
      (node (ref "LDO_1") (pin "2") (pinfunction "OUT_2") (pintype "bidirectional"))
    )
    (net (code "31") (name "Net-(C57-Pad1)") (class "Default")
      (node (ref "C57") (pin "1") (pinfunction "1_1") (pintype "passive"))
      (node (ref "L25") (pin "2") (pinfunction "2_2") (pintype "passive"))
      (node (ref "R8") (pin "2") (pinfunction "2_2") (pintype "passive"))
      (node (ref "X26") (pin "1") (pinfunction "1_1") (pintype "passive"))
    )
    (net (code "32") (name "Net-(C59-Pad2)") (class "Default")
      (node (ref "C59") (pin "2") (pinfunction "2_2") (pintype "passive"))
      (node (ref "C6") (pin "1") (pinfunction "1_1") (pintype "passive"))
      (node (ref "C61") (pin "OUT") (pinfunction "OUT_OUT") (pintype "bidirectional"))
      (node (ref "C7") (pin "1") (pinfunction "1_1") (pintype "passive"))
      (node (ref "L4") (pin "2") (pinfunction "2_2") (pintype "passive"))
      (node (ref "R6") (pin "1") (pinfunction "1_1") (pintype "passive"))
      (node (ref "TP_2") (pin "TP") (pinfunction "TP_TP") (pintype "input"))
    )
    (net (code "33") (name "Net-(C60-PadOUT)") (class "Default")
      (node (ref "C60") (pin "OUT") (pinfunction "OUT_OUT") (pintype "bidirectional"))
      (node (ref "LDO_2") (pin "7") (pinfunction "IN_7") (pintype "bidirectional"))
      (node (ref "LDO_2") (pin "8") (pinfunction "IN_8") (pintype "bidirectional"))
    )
    (net (code "34") (name "Net-(C61-PadIN)") (class "Default")
      (node (ref "C61") (pin "IN") (pinfunction "IN_IN") (pintype "bidirectional"))
      (node (ref "LDO_2") (pin "1") (pinfunction "OUT_1") (pintype "bidirectional"))
      (node (ref "LDO_2") (pin "2") (pinfunction "OUT_2") (pintype "bidirectional"))
    )
    (net (code "35") (name "Net-(C64-PadOUT)") (class "Default")
      (node (ref "C64") (pin "OUT") (pinfunction "OUT_OUT") (pintype "bidirectional"))
      (node (ref "LDO_3") (pin "7") (pinfunction "IN_7") (pintype "bidirectional"))
      (node (ref "LDO_3") (pin "8") (pinfunction "IN_8") (pintype "bidirectional"))
    )
    (net (code "36") (name "Net-(C65-PadIN)") (class "Default")
      (node (ref "C65") (pin "IN") (pinfunction "IN_IN") (pintype "bidirectional"))
      (node (ref "LDO_3") (pin "1") (pinfunction "OUT_1") (pintype "bidirectional"))
      (node (ref "LDO_3") (pin "2") (pinfunction "OUT_2") (pintype "bidirectional"))
    )
    (net (code "37") (name "Net-(C68-PadOUT)") (class "Default")
      (node (ref "C68") (pin "OUT") (pinfunction "OUT_OUT") (pintype "bidirectional"))
      (node (ref "LDO_4") (pin "7") (pinfunction "IN_7") (pintype "bidirectional"))
      (node (ref "LDO_4") (pin "8") (pinfunction "IN_8") (pintype "bidirectional"))
    )
    (net (code "38") (name "Net-(C69-PadIN)") (class "Default")
      (node (ref "C69") (pin "IN") (pinfunction "IN_IN") (pintype "bidirectional"))
      (node (ref "LDO_4") (pin "1") (pinfunction "OUT_1") (pintype "bidirectional"))
      (node (ref "LDO_4") (pin "2") (pinfunction "OUT_2") (pintype "bidirectional"))
    )
    (net (code "39") (name "Net-(C72-Pad1)") (class "Default")
      (node (ref "C72") (pin "1") (pinfunction "1_1") (pintype "passive"))
      (node (ref "R11") (pin "1") (pinfunction "1_1") (pintype "passive"))
    )
    (net (code "40") (name "Net-(C72-Pad2)") (class "Default")
      (node (ref "C72") (pin "2") (pinfunction "2_2") (pintype "passive"))
      (node (ref "L19") (pin "1") (pinfunction "1_1") (pintype "passive"))
    )
    (net (code "41") (name "Net-(C74-PadOUT)") (class "Default")
      (node (ref "C74") (pin "OUT") (pinfunction "OUT_OUT") (pintype "bidirectional"))
      (node (ref "LDO_5") (pin "7") (pinfunction "IN_7") (pintype "bidirectional"))
      (node (ref "LDO_5") (pin "8") (pinfunction "IN_8") (pintype "bidirectional"))
    )
    (net (code "42") (name "Net-(C75-PadIN)") (class "Default")
      (node (ref "C75") (pin "IN") (pinfunction "IN_IN") (pintype "bidirectional"))
      (node (ref "LDO_5") (pin "1") (pinfunction "OUT_1") (pintype "bidirectional"))
      (node (ref "LDO_5") (pin "2") (pinfunction "OUT_2") (pintype "bidirectional"))
    )
    (net (code "43") (name "Net-(C78-PadOUT)") (class "Default")
      (node (ref "C78") (pin "OUT") (pinfunction "OUT_OUT") (pintype "bidirectional"))
      (node (ref "LDO_6") (pin "7") (pinfunction "IN_7") (pintype "bidirectional"))
      (node (ref "LDO_6") (pin "8") (pinfunction "IN_8") (pintype "bidirectional"))
    )
    (net (code "44") (name "Net-(C79-PadIN)") (class "Default")
      (node (ref "C79") (pin "IN") (pinfunction "IN_IN") (pintype "bidirectional"))
      (node (ref "LDO_6") (pin "1") (pinfunction "OUT_1") (pintype "bidirectional"))
      (node (ref "LDO_6") (pin "2") (pinfunction "OUT_2") (pintype "bidirectional"))
    )
    (net (code "45") (name "Net-(C82-PadOUT)") (class "Default")
      (node (ref "C82") (pin "OUT") (pinfunction "OUT_OUT") (pintype "bidirectional"))
      (node (ref "LDO_7") (pin "7") (pinfunction "IN_7") (pintype "bidirectional"))
      (node (ref "LDO_7") (pin "8") (pinfunction "IN_8") (pintype "bidirectional"))
    )
    (net (code "46") (name "Net-(C83-PadIN)") (class "Default")
      (node (ref "C83") (pin "IN") (pinfunction "IN_IN") (pintype "bidirectional"))
      (node (ref "LDO_7") (pin "1") (pinfunction "OUT_1") (pintype "bidirectional"))
      (node (ref "LDO_7") (pin "2") (pinfunction "OUT_2") (pintype "bidirectional"))
    )
    (net (code "47") (name "Net-(C86-PadOUT)") (class "Default")
      (node (ref "C86") (pin "OUT") (pinfunction "OUT_OUT") (pintype "bidirectional"))
      (node (ref "LDO_8") (pin "7") (pinfunction "IN_7") (pintype "bidirectional"))
      (node (ref "LDO_8") (pin "8") (pinfunction "IN_8") (pintype "bidirectional"))
    )
    (net (code "48") (name "Net-(C87-PadIN)") (class "Default")
      (node (ref "C87") (pin "IN") (pinfunction "IN_IN") (pintype "bidirectional"))
      (node (ref "LDO_8") (pin "1") (pinfunction "OUT_1") (pintype "bidirectional"))
      (node (ref "LDO_8") (pin "2") (pinfunction "OUT_2") (pintype "bidirectional"))
    )
    (net (code "49") (name "Net-(C90-PadOUT)") (class "Default")
      (node (ref "C90") (pin "OUT") (pinfunction "OUT_OUT") (pintype "bidirectional"))
      (node (ref "LDO_9") (pin "7") (pinfunction "IN_7") (pintype "bidirectional"))
      (node (ref "LDO_9") (pin "8") (pinfunction "IN_8") (pintype "bidirectional"))
    )
    (net (code "50") (name "Net-(C91-PadIN)") (class "Default")
      (node (ref "C91") (pin "IN") (pinfunction "IN_IN") (pintype "bidirectional"))
      (node (ref "LDO_9") (pin "1") (pinfunction "OUT_1") (pintype "bidirectional"))
      (node (ref "LDO_9") (pin "2") (pinfunction "OUT_2") (pintype "bidirectional"))
    )
    (net (code "51") (name "Net-(C94-PadOUT)") (class "Default")
      (node (ref "C94") (pin "OUT") (pinfunction "OUT_OUT") (pintype "bidirectional"))
      (node (ref "LDO_10") (pin "7") (pinfunction "IN_7") (pintype "bidirectional"))
      (node (ref "LDO_10") (pin "8") (pinfunction "IN_8") (pintype "bidirectional"))
    )
    (net (code "52") (name "Net-(C95-PadIN)") (class "Default")
      (node (ref "C95") (pin "IN") (pinfunction "IN_IN") (pintype "bidirectional"))
      (node (ref "LDO_10") (pin "1") (pinfunction "OUT_1") (pintype "bidirectional"))
      (node (ref "LDO_10") (pin "2") (pinfunction "OUT_2") (pintype "bidirectional"))
    )
    (net (code "53") (name "Net-(C98-PadOUT)") (class "Default")
      (node (ref "C98") (pin "OUT") (pinfunction "OUT_OUT") (pintype "bidirectional"))
      (node (ref "LDO_11") (pin "7") (pinfunction "IN_7") (pintype "bidirectional"))
      (node (ref "LDO_11") (pin "8") (pinfunction "IN_8") (pintype "bidirectional"))
    )
    (net (code "54") (name "Net-(C99-PadIN)") (class "Default")
      (node (ref "C99") (pin "IN") (pinfunction "IN_IN") (pintype "bidirectional"))
      (node (ref "LDO_11") (pin "1") (pinfunction "OUT_1") (pintype "bidirectional"))
      (node (ref "LDO_11") (pin "2") (pinfunction "OUT_2") (pintype "bidirectional"))
    )
    (net (code "55") (name "Net-(C100-Pad1)") (class "Default")
      (node (ref "C100") (pin "1") (pinfunction "1_1") (pintype "passive"))
      (node (ref "C101") (pin "1") (pinfunction "1_1") (pintype "passive"))
      (node (ref "C103") (pin "1") (pinfunction "1_1") (pintype "passive"))
      (node (ref "L30") (pin "2") (pinfunction "2_2") (pintype "passive"))
      (node (ref "L32") (pin "2") (pinfunction "2_2") (pintype "passive"))
    )
    (net (code "56") (name "Net-(C101-Pad2)") (class "Default")
      (node (ref "C101") (pin "2") (pinfunction "2_2") (pintype "passive"))
      (node (ref "L33") (pin "1") (pinfunction "1_1") (pintype "passive"))
    )
    (net (code "57") (name "Net-(C102-Pad1)") (class "Default")
      (node (ref "C102") (pin "1") (pinfunction "1_1") (pintype "passive"))
      (node (ref "C48") (pin "1") (pinfunction "1_1") (pintype "passive"))
      (node (ref "C49") (pin "1") (pinfunction "1_1") (pintype "passive"))
      (node (ref "L23") (pin "2") (pinfunction "2_2") (pintype "passive"))
      (node (ref "L24") (pin "2") (pinfunction "2_2") (pintype "passive"))
    )
    (net (code "58") (name "Net-(C104-Pad1)") (class "Default")
      (node (ref "C104") (pin "1") (pinfunction "1_1") (pintype "passive"))
      (node (ref "C107") (pin "1") (pinfunction "1_1") (pintype "passive"))
      (node (ref "C73") (pin "1") (pinfunction "1_1") (pintype "passive"))
      (node (ref "L19") (pin "2") (pinfunction "2_2") (pintype "passive"))
      (node (ref "L26") (pin "2") (pinfunction "2_2") (pintype "passive"))
    )
    (net (code "59") (name "Net-(C104-Pad2)") (class "Default")
      (node (ref "C104") (pin "2") (pinfunction "2_2") (pintype "passive"))
      (node (ref "L27") (pin "1") (pinfunction "1_1") (pintype "passive"))
    )
    (net (code "60") (name "Net-(C105-Pad1)") (class "Default")
      (node (ref "C105") (pin "1") (pinfunction "1_1") (pintype "passive"))
      (node (ref "C106") (pin "1") (pinfunction "1_1") (pintype "passive"))
      (node (ref "C108") (pin "1") (pinfunction "1_1") (pintype "passive"))
      (node (ref "L27") (pin "2") (pinfunction "2_2") (pintype "passive"))
      (node (ref "L28") (pin "2") (pinfunction "2_2") (pintype "passive"))
    )
    (net (code "61") (name "Net-(C106-Pad2)") (class "Default")
      (node (ref "C106") (pin "2") (pinfunction "2_2") (pintype "passive"))
      (node (ref "L29") (pin "1") (pinfunction "1_1") (pintype "passive"))
    )
    (net (code "62") (name "Net-(C109-Pad1)") (class "Default")
      (node (ref "C109") (pin "1") (pinfunction "1_1") (pintype "passive"))
      (node (ref "L29") (pin "2") (pinfunction "2_2") (pintype "passive"))
      (node (ref "R13") (pin "2") (pinfunction "2_2") (pintype "passive"))
      (node (ref "X28") (pin "1") (pinfunction "1_1") (pintype "passive"))
    )
    (net (code "63") (name "Net-(C110-Pad2)") (class "Default")
      (node (ref "C110") (pin "2") (pinfunction "2_2") (pintype "passive"))
      (node (ref "R15") (pin "2") (pinfunction "2_2") (pintype "passive"))
      (node (ref "X29") (pin "1") (pinfunction "1_1") (pintype "passive"))
    )
    (net (code "64") (name "Net-(C459-PadIN)") (class "Default")
      (node (ref "C459") (pin "IN") (pinfunction "IN_IN") (pintype "bidirectional"))
      (node (ref "IC58") (pin "34") (pinfunction "VOUT_34") (pintype "bidirectional"))
      (node (ref "IC58") (pin "35") (pinfunction "VOUT_35") (pintype "bidirectional"))
      (node (ref "IC58") (pin "36") (pinfunction "VOUT_36") (pintype "bidirectional"))
      (node (ref "IC58") (pin "37") (pinfunction "VOUT_37") (pintype "bidirectional"))
      (node (ref "IC58") (pin "38") (pinfunction "VOUT_38") (pintype "bidirectional"))
      (node (ref "IC58") (pin "41") (pinfunction "VOUT_41") (pintype "bidirectional"))
    )
    (net (code "65") (name "Net-(C500-IN)") (class "Default")
      (node (ref "C500") (pin "1") (pinfunction "IN_1") (pintype "passive"))
      (node (ref "L31") (pin "2") (pinfunction "2_2") (pintype "passive"))
    )
    (net (code "66") (name "Net-(C500-OUT)") (class "Default")
      (node (ref "C481") (pin "1") (pinfunction "1_1") (pintype "passive"))
      (node (ref "C482") (pin "1") (pinfunction "1_1") (pintype "passive"))
      (node (ref "C483") (pin "+") (pinfunction "+_+") (pintype "passive"))
      (node (ref "C484") (pin "+") (pinfunction "+_+") (pintype "passive"))
      (node (ref "C489") (pin "1") (pinfunction "1_1") (pintype "passive"))
      (node (ref "C490") (pin "1") (pinfunction "1_1") (pintype "passive"))
      (node (ref "C491") (pin "1") (pinfunction "1_1") (pintype "passive"))
      (node (ref "C492") (pin "1") (pinfunction "1_1") (pintype "passive"))
      (node (ref "C493") (pin "1") (pinfunction "1_1") (pintype "passive"))
      (node (ref "C500") (pin "2") (pinfunction "OUT_2") (pintype "passive"))
      (node (ref "IC58") (pin "1") (pinfunction "PVIN_1") (pintype "bidirectional"))
      (node (ref "IC58") (pin "11") (pinfunction "PVIN_11") (pintype "bidirectional"))
      (node (ref "IC58") (pin "12") (pinfunction "PVIN_12") (pintype "bidirectional"))
      (node (ref "IC58") (pin "3") (pinfunction "VIN_3") (pintype "bidirectional"))
      (node (ref "IC58") (pin "39") (pinfunction "PVIN_39") (pintype "bidirectional"))
      (node (ref "IC58") (pin "40") (pinfunction "PVIN_40") (pintype "bidirectional"))
      (node (ref "R4") (pin "1") (pinfunction "1_1") (pintype "passive"))
    )
    (net (code "67") (name "Net-(IC1-SUM_PORT)") (class "Default")
      (node (ref "IC1") (pin "3") (pinfunction "SUM_PORT_3") (pintype "bidirectional"))
      (node (ref "X33") (pin "1") (pinfunction "1_1") (pintype "passive"))
    )
    (net (code "68") (name "Net-(IC58-INH{slash}UVLO)") (class "Default")
      (node (ref "IC58") (pin "30") (pinfunction "INH/UVLO_30") (pintype "bidirectional"))
      (node (ref "R1") (pin "1") (pinfunction "1_1") (pintype "passive"))
      (node (ref "R4") (pin "2") (pinfunction "2_2") (pintype "passive"))
    )
    (net (code "69") (name "Net-(IC58-PH-Pad10)") (class "Default")
      (node (ref "IC58") (pin "10") (pinfunction "PH_10") (pintype "bidirectional"))
      (node (ref "IC58") (pin "13") (pinfunction "PH_13") (pintype "bidirectional"))
      (node (ref "IC58") (pin "14") (pinfunction "PH_14") (pintype "bidirectional"))
      (node (ref "IC58") (pin "15") (pinfunction "PH_15") (pintype "bidirectional"))
      (node (ref "IC58") (pin "16") (pinfunction "PH_16") (pintype "bidirectional"))
      (node (ref "IC58") (pin "17") (pinfunction "PH_17") (pintype "bidirectional"))
      (node (ref "IC58") (pin "18") (pinfunction "PH_18") (pintype "bidirectional"))
      (node (ref "IC58") (pin "19") (pinfunction "PH_19") (pintype "bidirectional"))
      (node (ref "IC58") (pin "42") (pinfunction "PH_42") (pintype "bidirectional"))
      (node (ref "IC58") (pin "42A") (pinfunction "PH_42A") (pintype "bidirectional"))
      (node (ref "IC58") (pin "42B") (pinfunction "PH_42B") (pintype "bidirectional"))
      (node (ref "IC58") (pin "42C") (pinfunction "PH_42C") (pintype "bidirectional"))
      (node (ref "IC58") (pin "42D") (pinfunction "PH_42D") (pintype "bidirectional"))
      (node (ref "IC58") (pin "42E") (pinfunction "PH_42E") (pintype "bidirectional"))
      (node (ref "IC58") (pin "42F") (pinfunction "PH_42F") (pintype "bidirectional"))
      (node (ref "IC58") (pin "42G") (pinfunction "PH_42G") (pintype "bidirectional"))
      (node (ref "IC58") (pin "42H") (pinfunction "PH_42H") (pintype "bidirectional"))
      (node (ref "IC58") (pin "42J") (pinfunction "PH_42J") (pintype "bidirectional"))
      (node (ref "IC58") (pin "42K") (pinfunction "PH_42K") (pintype "bidirectional"))
      (node (ref "IC58") (pin "42L") (pinfunction "PH_42L") (pintype "bidirectional"))
      (node (ref "IC58") (pin "42M") (pinfunction "PH_42M") (pintype "bidirectional"))
      (node (ref "IC58") (pin "42N") (pinfunction "PH_42N") (pintype "bidirectional"))
      (node (ref "IC58") (pin "42P") (pinfunction "PH_42P") (pintype "bidirectional"))
    )
    (net (code "70") (name "Net-(IC58-PWRGD)") (class "Default")
      (node (ref "IC58") (pin "8") (pinfunction "PWRGD_8") (pintype "bidirectional"))
      (node (ref "TP10") (pin "TP") (pinfunction "TP_TP") (pintype "input"))
    )
    (net (code "71") (name "Net-(IC58-RT_CLK)") (class "Default")
      (node (ref "IC58") (pin "22") (pinfunction "RT_CLK_22") (pintype "bidirectional"))
      (node (ref "R206") (pin "2") (pinfunction "2_2") (pintype "passive"))
    )
    (net (code "72") (name "Net-(IC58-VADJ)") (class "Default")
      (node (ref "IC58") (pin "26") (pinfunction "VADJ_26") (pintype "bidirectional"))
      (node (ref "R205") (pin "2") (pinfunction "2_2") (pintype "passive"))
    )
    (net (code "73") (name "Net-(J1B-S)") (class "Default")
      (node (ref "J1") (pin "2") (pinfunction "S_2") (pintype "passive"))
      (node (ref "L31") (pin "1") (pinfunction "1_1") (pintype "passive"))
    )
    (net (code "74") (name "Net-(LDO_1-FB{slash}SNS)") (class "Default")
      (node (ref "C54") (pin "1") (pinfunction "1_1") (pintype "passive"))
      (node (ref "LDO_1") (pin "3") (pinfunction "FB/SNS_3") (pintype "bidirectional"))
      (node (ref "R2") (pin "2") (pinfunction "2_2") (pintype "passive"))
      (node (ref "R3") (pin "1") (pinfunction "1_1") (pintype "passive"))
    )
    (net (code "75") (name "Net-(LDO_1-NR)") (class "Default")
      (node (ref "C53") (pin "1") (pinfunction "1_1") (pintype "passive"))
      (node (ref "LDO_1") (pin "6") (pinfunction "NR_6") (pintype "bidirectional"))
    )
    (net (code "76") (name "Net-(LDO_2-FB{slash}SNS)") (class "Default")
      (node (ref "C59") (pin "1") (pinfunction "1_1") (pintype "passive"))
      (node (ref "LDO_2") (pin "3") (pinfunction "FB/SNS_3") (pintype "bidirectional"))
      (node (ref "R6") (pin "2") (pinfunction "2_2") (pintype "passive"))
      (node (ref "R7") (pin "1") (pinfunction "1_1") (pintype "passive"))
    )
    (net (code "77") (name "Net-(LDO_2-NR)") (class "Default")
      (node (ref "C58") (pin "1") (pinfunction "1_1") (pintype "passive"))
      (node (ref "LDO_2") (pin "6") (pinfunction "NR_6") (pintype "bidirectional"))
    )
    (net (code "78") (name "Net-(LDO_3-FB{slash}SNS)") (class "Default")
      (node (ref "C63") (pin "1") (pinfunction "1_1") (pintype "passive"))
      (node (ref "LDO_3") (pin "3") (pinfunction "FB/SNS_3") (pintype "bidirectional"))
      (node (ref "R10") (pin "1") (pinfunction "1_1") (pintype "passive"))
      (node (ref "R9") (pin "2") (pinfunction "2_2") (pintype "passive"))
    )
    (net (code "79") (name "Net-(LDO_3-NR)") (class "Default")
      (node (ref "C62") (pin "1") (pinfunction "1_1") (pintype "passive"))
      (node (ref "LDO_3") (pin "6") (pinfunction "NR_6") (pintype "bidirectional"))
    )
    (net (code "80") (name "Net-(LDO_4-FB{slash}SNS)") (class "Default")
      (node (ref "C67") (pin "1") (pinfunction "1_1") (pintype "passive"))
      (node (ref "LDO_4") (pin "3") (pinfunction "FB/SNS_3") (pintype "bidirectional"))
      (node (ref "R12") (pin "2") (pinfunction "2_2") (pintype "passive"))
      (node (ref "R14") (pin "1") (pinfunction "1_1") (pintype "passive"))
    )
    (net (code "81") (name "Net-(LDO_4-NR)") (class "Default")
      (node (ref "C66") (pin "1") (pinfunction "1_1") (pintype "passive"))
      (node (ref "LDO_4") (pin "6") (pinfunction "NR_6") (pintype "bidirectional"))
    )
    (net (code "82") (name "Net-(LDO_5-FB{slash}SNS)") (class "Default")
      (node (ref "C71") (pin "1") (pinfunction "1_1") (pintype "passive"))
      (node (ref "LDO_5") (pin "3") (pinfunction "FB/SNS_3") (pintype "bidirectional"))
      (node (ref "R16") (pin "2") (pinfunction "2_2") (pintype "passive"))
      (node (ref "R19") (pin "1") (pinfunction "1_1") (pintype "passive"))
    )
    (net (code "83") (name "Net-(LDO_5-NR)") (class "Default")
      (node (ref "C70") (pin "1") (pinfunction "1_1") (pintype "passive"))
      (node (ref "LDO_5") (pin "6") (pinfunction "NR_6") (pintype "bidirectional"))
    )
    (net (code "84") (name "Net-(LDO_6-FB{slash}SNS)") (class "Default")
      (node (ref "C77") (pin "1") (pinfunction "1_1") (pintype "passive"))
      (node (ref "LDO_6") (pin "3") (pinfunction "FB/SNS_3") (pintype "bidirectional"))
      (node (ref "R22") (pin "2") (pinfunction "2_2") (pintype "passive"))
      (node (ref "R23") (pin "1") (pinfunction "1_1") (pintype "passive"))
    )
    (net (code "85") (name "Net-(LDO_6-NR)") (class "Default")
      (node (ref "C76") (pin "1") (pinfunction "1_1") (pintype "passive"))
      (node (ref "LDO_6") (pin "6") (pinfunction "NR_6") (pintype "bidirectional"))
    )
    (net (code "86") (name "Net-(LDO_7-FB{slash}SNS)") (class "Default")
      (node (ref "C81") (pin "1") (pinfunction "1_1") (pintype "passive"))
      (node (ref "LDO_7") (pin "3") (pinfunction "FB/SNS_3") (pintype "bidirectional"))
      (node (ref "R25") (pin "2") (pinfunction "2_2") (pintype "passive"))
      (node (ref "R26") (pin "1") (pinfunction "1_1") (pintype "passive"))
    )
    (net (code "87") (name "Net-(LDO_7-NR)") (class "Default")
      (node (ref "C80") (pin "1") (pinfunction "1_1") (pintype "passive"))
      (node (ref "LDO_7") (pin "6") (pinfunction "NR_6") (pintype "bidirectional"))
    )
    (net (code "88") (name "Net-(LDO_8-FB{slash}SNS)") (class "Default")
      (node (ref "C85") (pin "1") (pinfunction "1_1") (pintype "passive"))
      (node (ref "LDO_8") (pin "3") (pinfunction "FB/SNS_3") (pintype "bidirectional"))
      (node (ref "R28") (pin "2") (pinfunction "2_2") (pintype "passive"))
      (node (ref "R29") (pin "1") (pinfunction "1_1") (pintype "passive"))
    )
    (net (code "89") (name "Net-(LDO_8-NR)") (class "Default")
      (node (ref "C84") (pin "1") (pinfunction "1_1") (pintype "passive"))
      (node (ref "LDO_8") (pin "6") (pinfunction "NR_6") (pintype "bidirectional"))
    )
    (net (code "90") (name "Net-(LDO_9-FB{slash}SNS)") (class "Default")
      (node (ref "C89") (pin "1") (pinfunction "1_1") (pintype "passive"))
      (node (ref "LDO_9") (pin "3") (pinfunction "FB/SNS_3") (pintype "bidirectional"))
      (node (ref "R31") (pin "2") (pinfunction "2_2") (pintype "passive"))
      (node (ref "R32") (pin "1") (pinfunction "1_1") (pintype "passive"))
    )
    (net (code "91") (name "Net-(LDO_9-NR)") (class "Default")
      (node (ref "C88") (pin "1") (pinfunction "1_1") (pintype "passive"))
      (node (ref "LDO_9") (pin "6") (pinfunction "NR_6") (pintype "bidirectional"))
    )
    (net (code "92") (name "Net-(LDO_10-FB{slash}SNS)") (class "Default")
      (node (ref "C93") (pin "1") (pinfunction "1_1") (pintype "passive"))
      (node (ref "LDO_10") (pin "3") (pinfunction "FB/SNS_3") (pintype "bidirectional"))
      (node (ref "R34") (pin "2") (pinfunction "2_2") (pintype "passive"))
      (node (ref "R35") (pin "1") (pinfunction "1_1") (pintype "passive"))
    )
    (net (code "93") (name "Net-(LDO_10-NR)") (class "Default")
      (node (ref "C92") (pin "1") (pinfunction "1_1") (pintype "passive"))
      (node (ref "LDO_10") (pin "6") (pinfunction "NR_6") (pintype "bidirectional"))
    )
    (net (code "94") (name "Net-(LDO_11-FB{slash}SNS)") (class "Default")
      (node (ref "C97") (pin "1") (pinfunction "1_1") (pintype "passive"))
      (node (ref "LDO_11") (pin "3") (pinfunction "FB/SNS_3") (pintype "bidirectional"))
      (node (ref "R37") (pin "2") (pinfunction "2_2") (pintype "passive"))
      (node (ref "R38") (pin "1") (pinfunction "1_1") (pintype "passive"))
    )
    (net (code "95") (name "Net-(LDO_11-NR)") (class "Default")
      (node (ref "C96") (pin "1") (pinfunction "1_1") (pintype "passive"))
      (node (ref "LDO_11") (pin "6") (pinfunction "NR_6") (pintype "bidirectional"))
    )
    (net (code "96") (name "Net-(LED1-PadA)") (class "Default")
      (node (ref "LED1") (pin "A") (pinfunction "A_A") (pintype "passive"))
      (node (ref "R201") (pin "1") (pinfunction "1_1") (pintype "passive"))
    )
    (net (code "97") (name "Net-(LNA_1-RF_IN)") (class "Default")
      (node (ref "C1") (pin "2") (pinfunction "2_2") (pintype "passive"))
      (node (ref "LNA_1") (pin "3") (pinfunction "RF_IN_3") (pintype "bidirectional"))
    )
    (net (code "98") (name "Net-(LNA_1-RF_OUT)") (class "Default")
      (node (ref "C4") (pin "1") (pinfunction "1_1") (pintype "passive"))
      (node (ref "L1") (pin "1") (pinfunction "1_1") (pintype "passive"))
      (node (ref "LNA_1") (pin "1") (pinfunction "RF_OUT_1") (pintype "bidirectional"))
    )
    (net (code "99") (name "Net-(LNA_2-RF_IN)") (class "Default")
      (node (ref "C5") (pin "2") (pinfunction "2_2") (pintype "passive"))
      (node (ref "LNA_2") (pin "3") (pinfunction "RF_IN_3") (pintype "bidirectional"))
    )
    (net (code "100") (name "Net-(LNA_2-RF_OUT)") (class "Default")
      (node (ref "C8") (pin "2") (pinfunction "2_2") (pintype "passive"))
      (node (ref "L4") (pin "1") (pinfunction "1_1") (pintype "passive"))
      (node (ref "LNA_2") (pin "1") (pinfunction "RF_OUT_1") (pintype "bidirectional"))
    )
    (net (code "101") (name "Net-(LNA_3-RF_IN)") (class "Default")
      (node (ref "C9") (pin "2") (pinfunction "2_2") (pintype "passive"))
      (node (ref "LNA_3") (pin "3") (pinfunction "RF_IN_3") (pintype "bidirectional"))
    )
    (net (code "102") (name "Net-(LNA_3-RF_OUT)") (class "Default")
      (node (ref "C12") (pin "1") (pinfunction "1_1") (pintype "passive"))
      (node (ref "L7") (pin "2") (pinfunction "2_2") (pintype "passive"))
      (node (ref "LNA_3") (pin "1") (pinfunction "RF_OUT_1") (pintype "bidirectional"))
    )
    (net (code "103") (name "Net-(LNA_4-RF_IN)") (class "Default")
      (node (ref "C14") (pin "2") (pinfunction "2_2") (pintype "passive"))
      (node (ref "LNA_4") (pin "3") (pinfunction "RF_IN_3") (pintype "bidirectional"))
    )
    (net (code "104") (name "Net-(LNA_4-RF_OUT)") (class "Default")
      (node (ref "C17") (pin "1") (pinfunction "1_1") (pintype "passive"))
      (node (ref "L10") (pin "1") (pinfunction "1_1") (pintype "passive"))
      (node (ref "LNA_4") (pin "1") (pinfunction "RF_OUT_1") (pintype "bidirectional"))
    )
    (net (code "105") (name "Net-(LNA_5-RF_IN)") (class "Default")
      (node (ref "C18") (pin "2") (pinfunction "2_2") (pintype "passive"))
      (node (ref "LNA_5") (pin "3") (pinfunction "RF_IN_3") (pintype "bidirectional"))
    )
    (net (code "106") (name "Net-(LNA_5-RF_OUT)") (class "Default")
      (node (ref "C21") (pin "1") (pinfunction "1_1") (pintype "passive"))
      (node (ref "L11") (pin "1") (pinfunction "1_1") (pintype "passive"))
      (node (ref "LNA_5") (pin "1") (pinfunction "RF_OUT_1") (pintype "bidirectional"))
    )
    (net (code "107") (name "Net-(LNA_6-RF_IN)") (class "Default")
      (node (ref "C22") (pin "2") (pinfunction "2_2") (pintype "passive"))
      (node (ref "LNA_6") (pin "3") (pinfunction "RF_IN_3") (pintype "bidirectional"))
    )
    (net (code "108") (name "Net-(LNA_6-RF_OUT)") (class "Default")
      (node (ref "C25") (pin "1") (pinfunction "1_1") (pintype "passive"))
      (node (ref "L12") (pin "2") (pinfunction "2_2") (pintype "passive"))
      (node (ref "LNA_6") (pin "1") (pinfunction "RF_OUT_1") (pintype "bidirectional"))
    )
    (net (code "109") (name "Net-(LNA_7-RF_IN)") (class "Default")
      (node (ref "C26") (pin "2") (pinfunction "2_2") (pintype "passive"))
      (node (ref "LNA_7") (pin "3") (pinfunction "RF_IN_3") (pintype "bidirectional"))
    )
    (net (code "110") (name "Net-(LNA_7-RF_OUT)") (class "Default")
      (node (ref "C29") (pin "1") (pinfunction "1_1") (pintype "passive"))
      (node (ref "L13") (pin "1") (pinfunction "1_1") (pintype "passive"))
      (node (ref "LNA_7") (pin "1") (pinfunction "RF_OUT_1") (pintype "bidirectional"))
    )
    (net (code "111") (name "Net-(LNA_8-RF_IN)") (class "Default")
      (node (ref "C30") (pin "2") (pinfunction "2_2") (pintype "passive"))
      (node (ref "LNA_8") (pin "3") (pinfunction "RF_IN_3") (pintype "bidirectional"))
    )
    (net (code "112") (name "Net-(LNA_8-RF_OUT)") (class "Default")
      (node (ref "C33") (pin "1") (pinfunction "1_1") (pintype "passive"))
      (node (ref "L14") (pin "1") (pinfunction "1_1") (pintype "passive"))
      (node (ref "LNA_8") (pin "1") (pinfunction "RF_OUT_1") (pintype "bidirectional"))
    )
    (net (code "113") (name "Net-(LNA_9-RF_IN)") (class "Default")
      (node (ref "C34") (pin "2") (pinfunction "2_2") (pintype "passive"))
      (node (ref "LNA_9") (pin "3") (pinfunction "RF_IN_3") (pintype "bidirectional"))
    )
    (net (code "114") (name "Net-(LNA_9-RF_OUT)") (class "Default")
      (node (ref "C37") (pin "1") (pinfunction "1_1") (pintype "passive"))
      (node (ref "L15") (pin "1") (pinfunction "1_1") (pintype "passive"))
      (node (ref "LNA_9") (pin "1") (pinfunction "RF_OUT_1") (pintype "bidirectional"))
    )
    (net (code "115") (name "Net-(LNA_10-RF_IN)") (class "Default")
      (node (ref "C57") (pin "2") (pinfunction "2_2") (pintype "passive"))
      (node (ref "LNA_10") (pin "3") (pinfunction "RF_IN_3") (pintype "bidirectional"))
    )
    (net (code "116") (name "Net-(LNA_10-RF_OUT)") (class "Default")
      (node (ref "C42") (pin "1") (pinfunction "1_1") (pintype "passive"))
      (node (ref "L18") (pin "1") (pinfunction "1_1") (pintype "passive"))
      (node (ref "LNA_10") (pin "1") (pinfunction "RF_OUT_1") (pintype "bidirectional"))
    )
    (net (code "117") (name "Net-(LNA_11-RF_IN)") (class "Default")
      (node (ref "C109") (pin "2") (pinfunction "2_2") (pintype "passive"))
      (node (ref "LNA_11") (pin "3") (pinfunction "RF_IN_3") (pintype "bidirectional"))
    )
    (net (code "118") (name "Net-(LNA_11-RF_OUT)") (class "Default")
      (node (ref "C110") (pin "1") (pinfunction "1_1") (pintype "passive"))
      (node (ref "L21") (pin "1") (pinfunction "1_1") (pintype "passive"))
      (node (ref "LNA_11") (pin "1") (pinfunction "RF_OUT_1") (pintype "bidirectional"))
    )
    (net (code "119") (name "Net-(R5-Pad2)") (class "Default")
      (node (ref "R5") (pin "2") (pinfunction "2_2") (pintype "passive"))
      (node (ref "X25") (pin "1") (pinfunction "1_1") (pintype "passive"))
    )
    (net (code "120") (name "Net-(SAW_1-INPUT)") (class "Default")
      (node (ref "SAW_1") (pin "1") (pinfunction "INPUT_1") (pintype "bidirectional"))
      (node (ref "X1") (pin "1") (pinfunction "1_1") (pintype "passive"))
    )
    (net (code "121") (name "Net-(SAW_1-OUTPUT)") (class "Default")
      (node (ref "C1") (pin "1") (pinfunction "1_1") (pintype "passive"))
      (node (ref "SAW_1") (pin "8") (pinfunction "OUTPUT_8") (pintype "bidirectional"))
      (node (ref "X2") (pin "1") (pinfunction "1_1") (pintype "passive"))
    )
    (net (code "122") (name "Net-(SAW_2-INPUT)") (class "Default")
      (node (ref "C4") (pin "2") (pinfunction "2_2") (pintype "passive"))
      (node (ref "L2") (pin "2") (pinfunction "2_2") (pintype "passive"))
      (node (ref "SAW_2") (pin "2") (pinfunction "INPUT_2") (pintype "bidirectional"))
      (node (ref "X3") (pin "1") (pinfunction "1_1") (pintype "passive"))
    )
    (net (code "123") (name "Net-(SAW_2-OUTPUT)") (class "Default")
      (node (ref "C5") (pin "1") (pinfunction "1_1") (pintype "passive"))
      (node (ref "L3") (pin "2") (pinfunction "2_2") (pintype "passive"))
      (node (ref "SAW_2") (pin "6") (pinfunction "OUTPUT_6") (pintype "bidirectional"))
      (node (ref "X4") (pin "1") (pinfunction "1_1") (pintype "passive"))
    )
    (net (code "124") (name "Net-(SAW_3-INPUT)") (class "Default")
      (node (ref "C8") (pin "1") (pinfunction "1_1") (pintype "passive"))
      (node (ref "L5") (pin "2") (pinfunction "2_2") (pintype "passive"))
      (node (ref "SAW_3") (pin "2") (pinfunction "INPUT_2") (pintype "bidirectional"))
      (node (ref "X5") (pin "1") (pinfunction "1_1") (pintype "passive"))
    )
    (net (code "125") (name "Net-(SAW_3-OUTPUT)") (class "Default")
      (node (ref "C9") (pin "1") (pinfunction "1_1") (pintype "passive"))
      (node (ref "L6") (pin "2") (pinfunction "2_2") (pintype "passive"))
      (node (ref "SAW_3") (pin "6") (pinfunction "OUTPUT_6") (pintype "bidirectional"))
      (node (ref "X6") (pin "1") (pinfunction "1_1") (pintype "passive"))
    )
    (net (code "126") (name "Net-(SAW_4-INPUT)") (class "Default")
      (node (ref "C12") (pin "2") (pinfunction "2_2") (pintype "passive"))
      (node (ref "L8") (pin "2") (pinfunction "2_2") (pintype "passive"))
      (node (ref "SAW_4") (pin "2") (pinfunction "INPUT_2") (pintype "bidirectional"))
      (node (ref "X7") (pin "1") (pinfunction "1_1") (pintype "passive"))
    )
    (net (code "127") (name "Net-(SAW_4-OUTPUT)") (class "Default")
      (node (ref "C13") (pin "1") (pinfunction "1_1") (pintype "passive"))
      (node (ref "L9") (pin "2") (pinfunction "2_2") (pintype "passive"))
      (node (ref "SAW_4") (pin "6") (pinfunction "OUTPUT_6") (pintype "bidirectional"))
    )
    (net (code "128") (name "Net-(SAW_5-INPUT)") (class "Default")
      (node (ref "C17") (pin "2") (pinfunction "2_2") (pintype "passive"))
      (node (ref "SAW_5") (pin "2") (pinfunction "INPUT_2") (pintype "bidirectional"))
      (node (ref "X10") (pin "1") (pinfunction "1_1") (pintype "passive"))
    )
    (net (code "129") (name "Net-(SAW_5-OUTPUT)") (class "Default")
      (node (ref "C18") (pin "1") (pinfunction "1_1") (pintype "passive"))
      (node (ref "SAW_5") (pin "6") (pinfunction "OUTPUT_6") (pintype "bidirectional"))
      (node (ref "X11") (pin "1") (pinfunction "1_1") (pintype "passive"))
    )
    (net (code "130") (name "Net-(SAW_6-INPUT)") (class "Default")
      (node (ref "C21") (pin "2") (pinfunction "2_2") (pintype "passive"))
      (node (ref "SAW_6") (pin "2") (pinfunction "INPUT_2") (pintype "bidirectional"))
      (node (ref "X12") (pin "1") (pinfunction "1_1") (pintype "passive"))
    )
    (net (code "131") (name "Net-(SAW_6-OUTPUT)") (class "Default")
      (node (ref "C22") (pin "1") (pinfunction "1_1") (pintype "passive"))
      (node (ref "SAW_6") (pin "6") (pinfunction "OUTPUT_6") (pintype "bidirectional"))
      (node (ref "X13") (pin "1") (pinfunction "1_1") (pintype "passive"))
    )
    (net (code "132") (name "Net-(SAW_7-INPUT)") (class "Default")
      (node (ref "C25") (pin "2") (pinfunction "2_2") (pintype "passive"))
      (node (ref "SAW_7") (pin "2") (pinfunction "INPUT_2") (pintype "bidirectional"))
      (node (ref "X14") (pin "1") (pinfunction "1_1") (pintype "passive"))
    )
    (net (code "133") (name "Net-(SAW_7-OUTPUT)") (class "Default")
      (node (ref "SAW_7") (pin "6") (pinfunction "OUTPUT_6") (pintype "bidirectional"))
      (node (ref "SAW_8") (pin "2") (pinfunction "INPUT_2") (pintype "bidirectional"))
      (node (ref "X15") (pin "1") (pinfunction "1_1") (pintype "passive"))
    )
    (net (code "134") (name "Net-(SAW_9-INPUT)") (class "Default")
      (node (ref "C29") (pin "2") (pinfunction "2_2") (pintype "passive"))
      (node (ref "SAW_9") (pin "2") (pinfunction "INPUT_2") (pintype "bidirectional"))
      (node (ref "X18") (pin "1") (pinfunction "1_1") (pintype "passive"))
    )
    (net (code "135") (name "Net-(SAW_9-OUTPUT)") (class "Default")
      (node (ref "C30") (pin "1") (pinfunction "1_1") (pintype "passive"))
      (node (ref "SAW_9") (pin "5") (pinfunction "OUTPUT_5") (pintype "bidirectional"))
      (node (ref "X19") (pin "1") (pinfunction "1_1") (pintype "passive"))
    )
    (net (code "136") (name "Net-(SAW_10-INPUT)") (class "Default")
      (node (ref "C33") (pin "2") (pinfunction "2_2") (pintype "passive"))
      (node (ref "SAW_10") (pin "2") (pinfunction "INPUT_2") (pintype "bidirectional"))
      (node (ref "X20") (pin "1") (pinfunction "1_1") (pintype "passive"))
    )
    (net (code "137") (name "Net-(SAW_10-OUTPUT)") (class "Default")
      (node (ref "C34") (pin "1") (pinfunction "1_1") (pintype "passive"))
      (node (ref "SAW_10") (pin "5") (pinfunction "OUTPUT_5") (pintype "bidirectional"))
      (node (ref "X21") (pin "1") (pinfunction "1_1") (pintype "passive"))
    )
    (net (code "138") (name "Net-(SAW_11-INPUT)") (class "Default")
      (node (ref "C37") (pin "2") (pinfunction "2_2") (pintype "passive"))
      (node (ref "SAW_11") (pin "2") (pinfunction "INPUT_2") (pintype "bidirectional"))
      (node (ref "X22") (pin "1") (pinfunction "1_1") (pintype "passive"))
    )
    (net (code "139") (name "Net-(SAW_11-OUTPUT)") (class "Default")
      (node (ref "SAW_11") (pin "5") (pinfunction "OUTPUT_5") (pintype "bidirectional"))
      (node (ref "SAW_12") (pin "2") (pinfunction "INPUT_2") (pintype "bidirectional"))
      (node (ref "X23") (pin "1") (pinfunction "1_1") (pintype "passive"))
    )
    (net (code "140") (name "unconnected-(IC58-ILIM-Pad6)") (class "Default")
      (node (ref "IC58") (pin "6") (pinfunction "ILIM_6") (pintype "bidirectional"))
    )
    (net (code "141") (name "unconnected-(IC58-ISHARE-Pad25)") (class "Default")
      (node (ref "IC58") (pin "25") (pinfunction "ISHARE_25") (pintype "bidirectional"))
    )
    (net (code "142") (name "unconnected-(IC58-OCP_SEL-Pad4)") (class "Default")
      (node (ref "IC58") (pin "4") (pinfunction "OCP_SEL_4") (pintype "bidirectional"))
    )
    (net (code "143") (name "unconnected-(IC58-SS{slash}TR-Pad28)") (class "Default")
      (node (ref "IC58") (pin "28") (pinfunction "SS/TR_28") (pintype "bidirectional"))
    )
    (net (code "144") (name "unconnected-(IC58-SYNC_OUT-Pad7)") (class "Default")
      (node (ref "IC58") (pin "7") (pinfunction "SYNC_OUT_7") (pintype "bidirectional"))
    )
  )
)
